# UCirKitBreadboardWithEverythingTop_2Laye.net
KiCad netlist of a schematic drawn in EAGLE
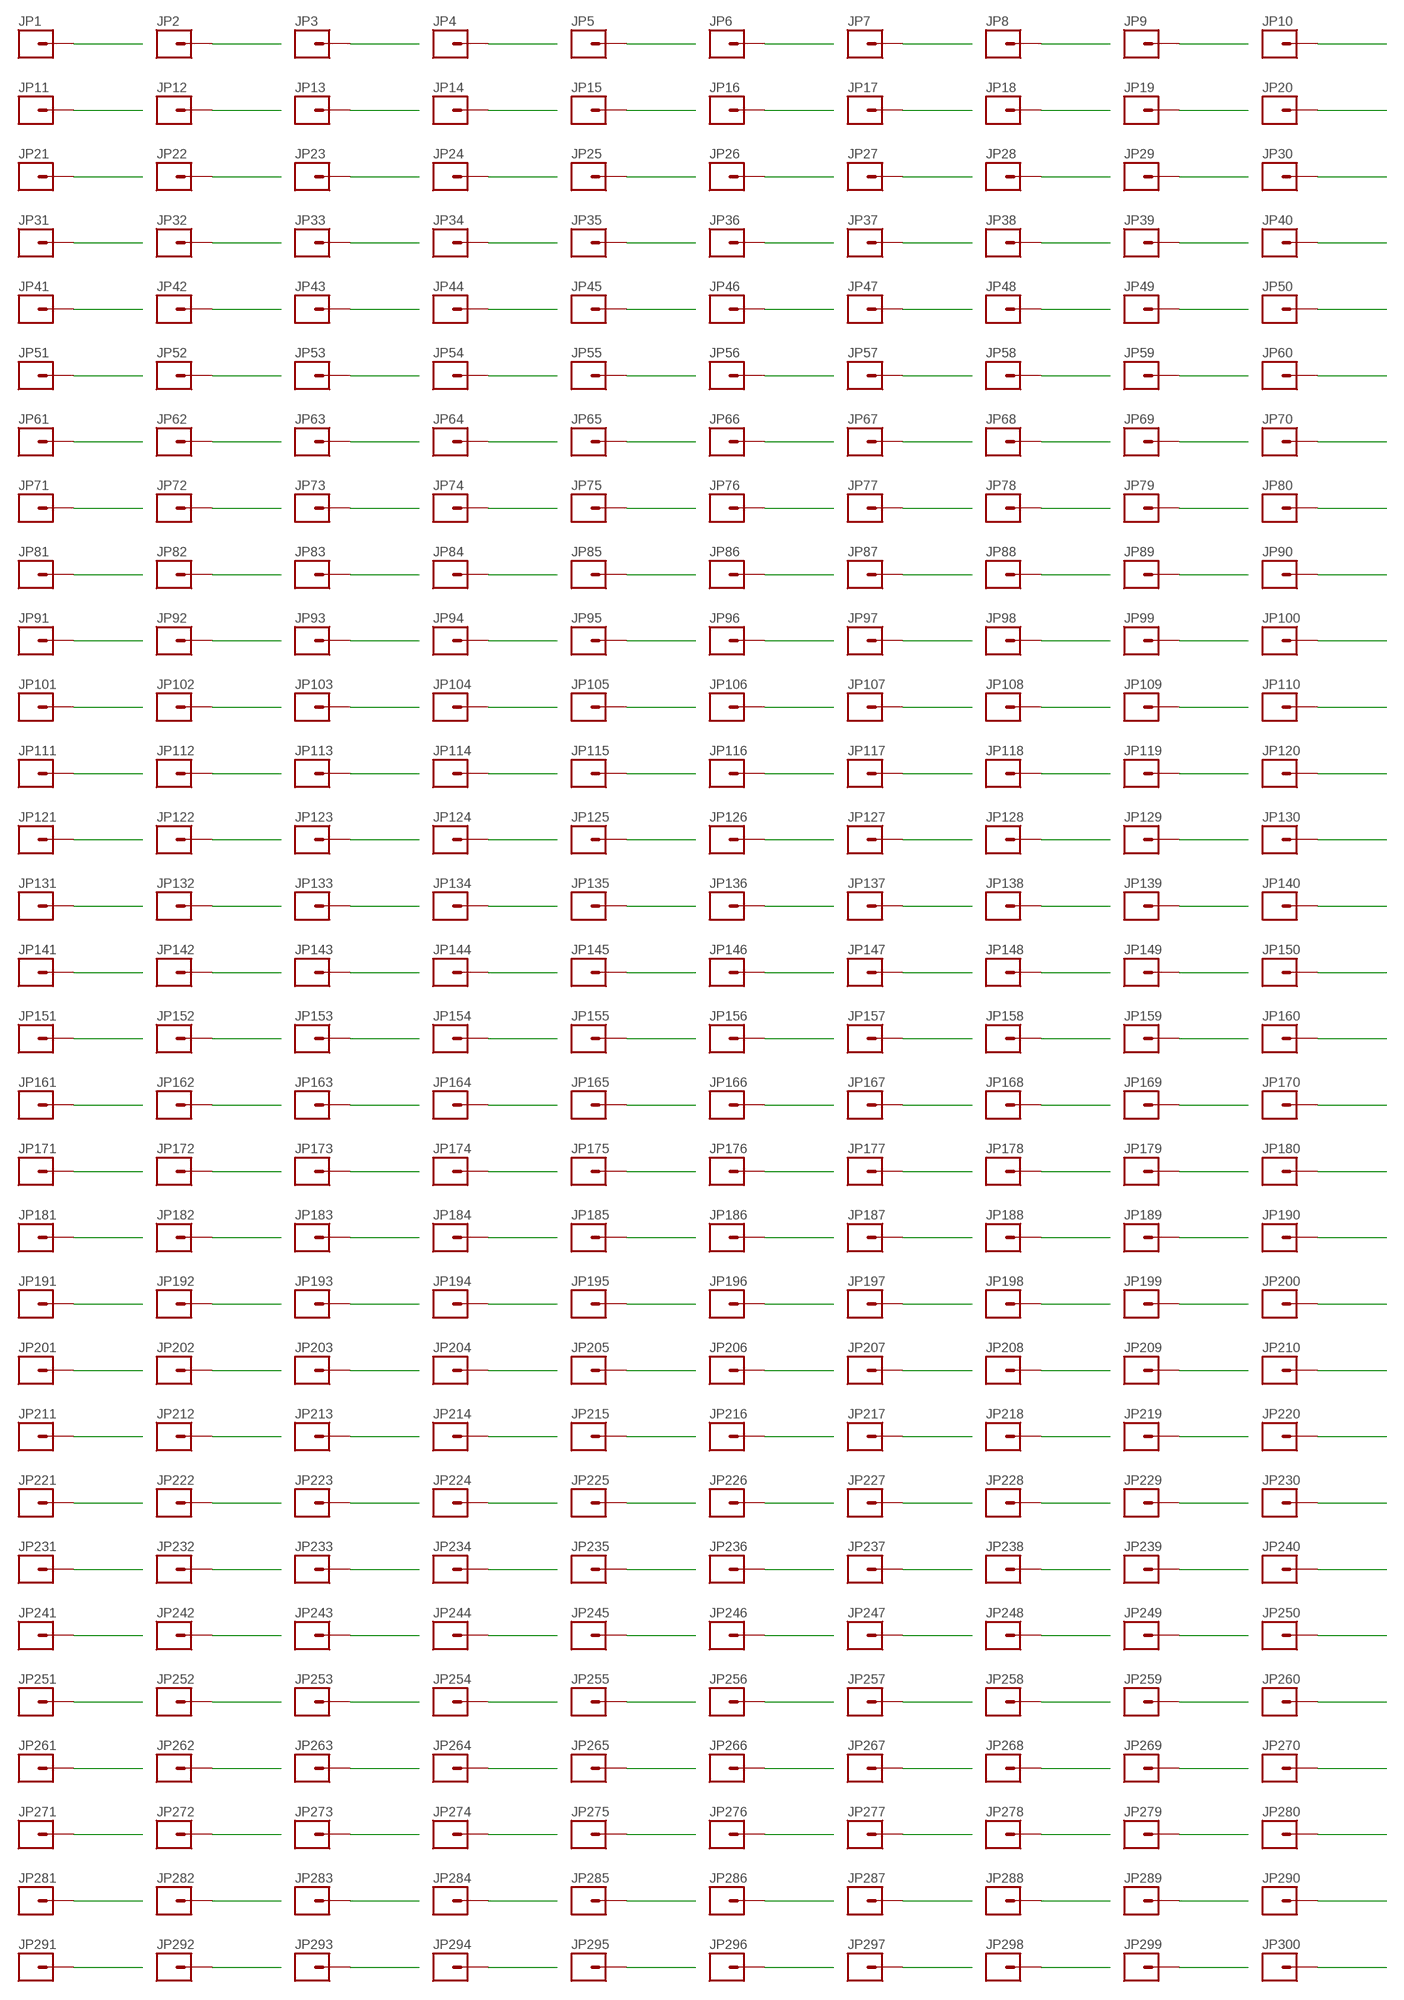
[diagram p0: schematic, sheet 1, part 1 of 2]
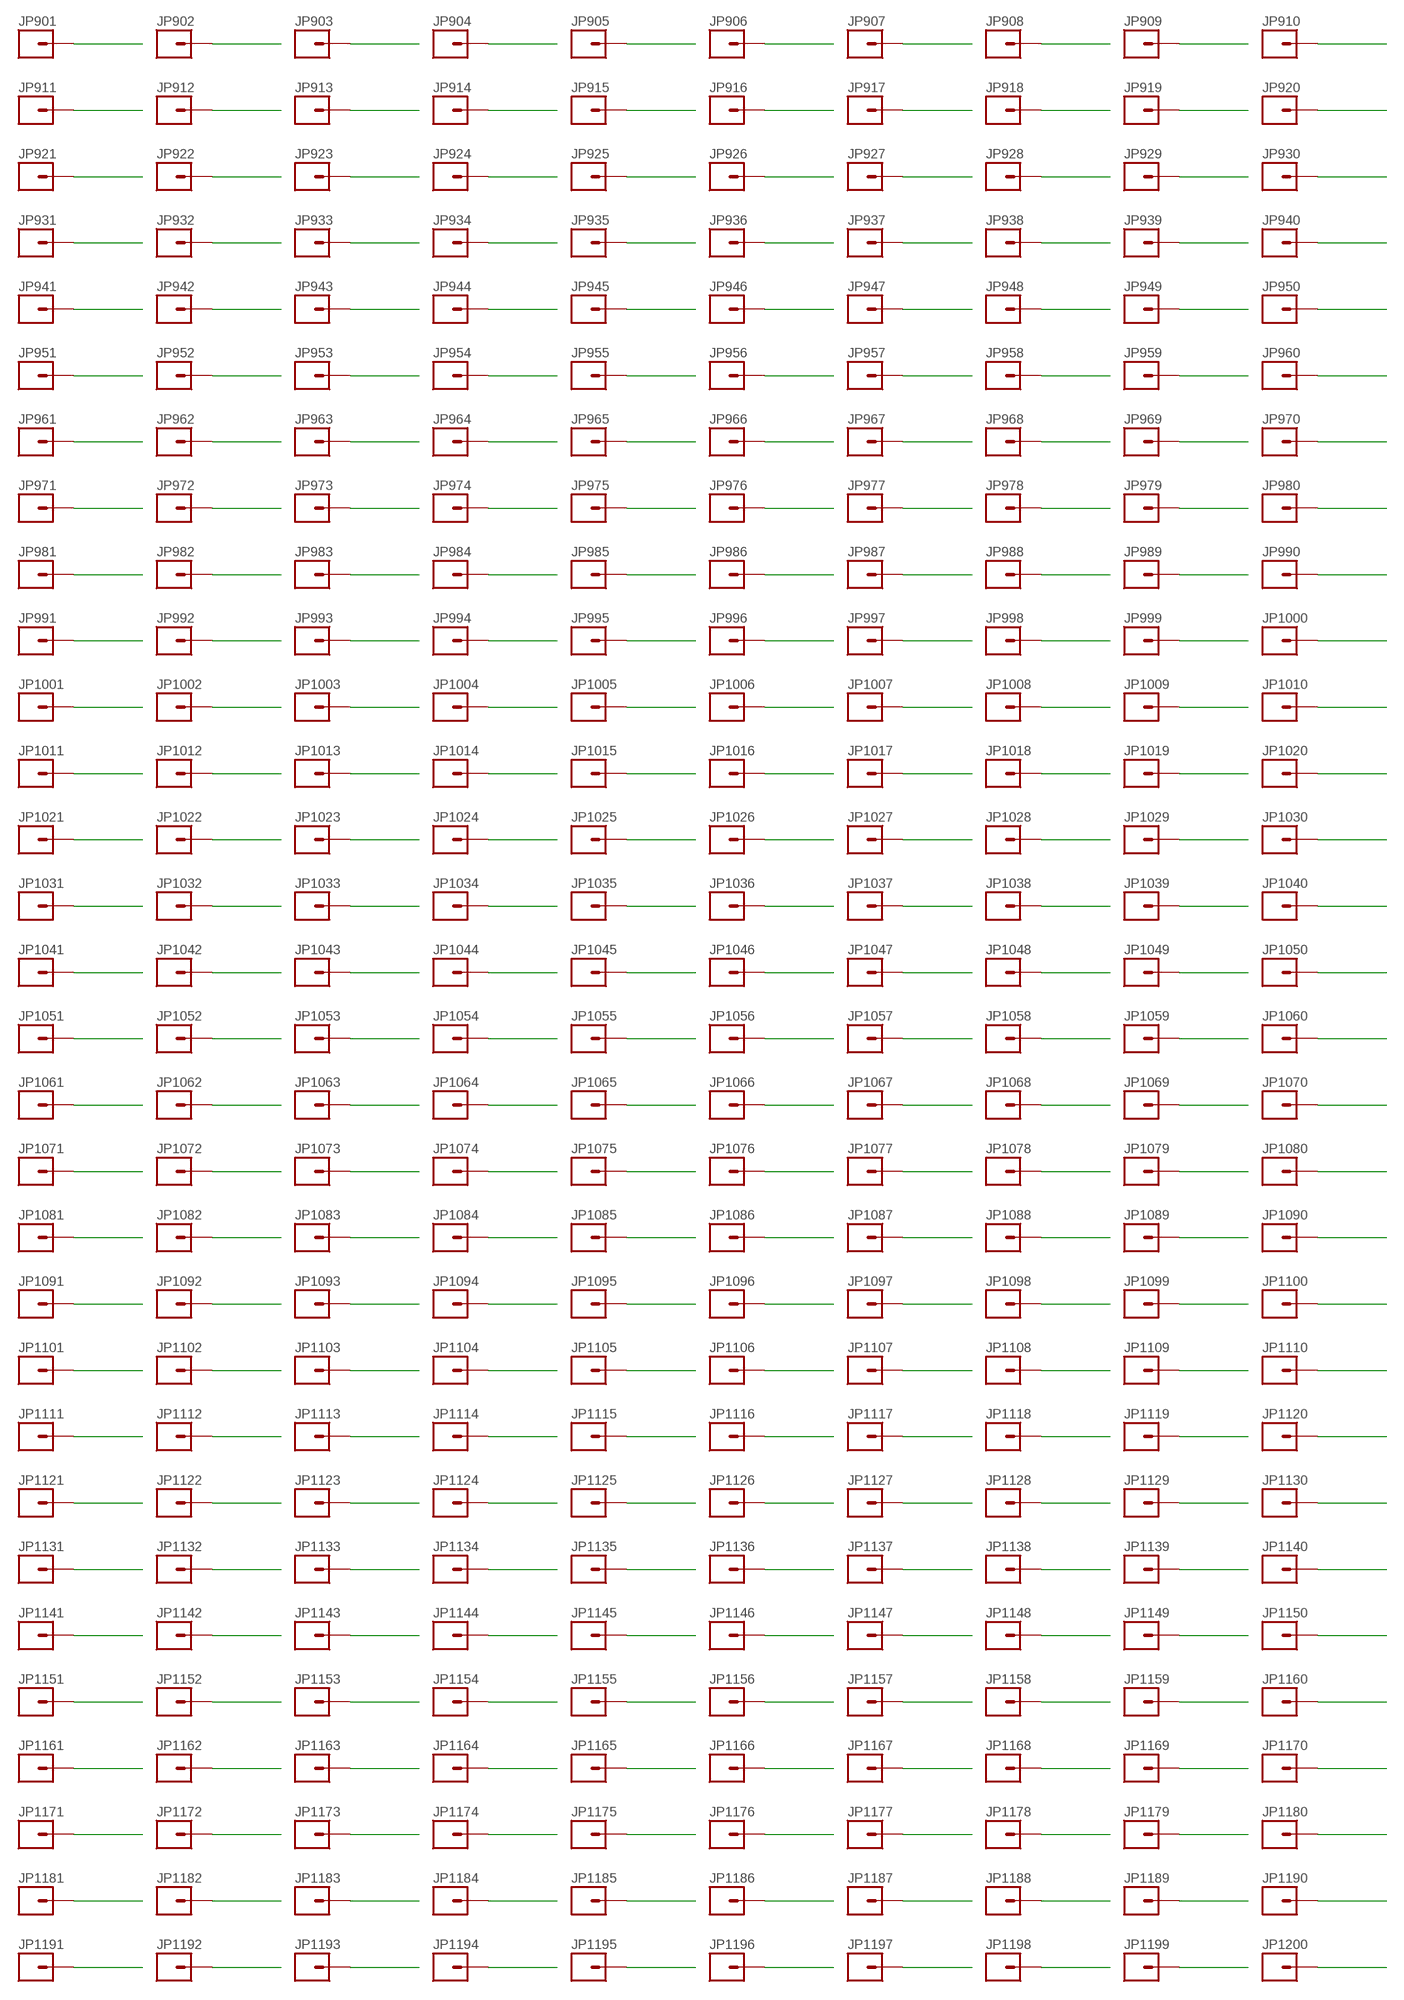
[diagram p1: schematic, sheet 1, part 2 of 2]

(export (version "E")
  (design (tool "Eeschema 10.0.6"))
  (components
    (comp (ref "JP1")
      (value "M01PTH_WITHOUT_TEXT")
      (footprint "eagle-import:1X01_WITHOUT_TEXT")
      (libsource (lib "eagle-import") (part "M01PTH_WITHOUT_TEXT"))
    )
    (comp (ref "JP2")
      (value "M01PTH_WITHOUT_TEXT")
      (footprint "eagle-import:1X01_WITHOUT_TEXT")
      (libsource (lib "eagle-import") (part "M01PTH_WITHOUT_TEXT"))
    )
    (comp (ref "JP3")
      (value "M01PTH_WITHOUT_TEXT")
      (footprint "eagle-import:1X01_WITHOUT_TEXT")
      (libsource (lib "eagle-import") (part "M01PTH_WITHOUT_TEXT"))
    )
    (comp (ref "JP4")
      (value "M01PTH_WITHOUT_TEXT")
      (footprint "eagle-import:1X01_WITHOUT_TEXT")
      (libsource (lib "eagle-import") (part "M01PTH_WITHOUT_TEXT"))
    )
    (comp (ref "JP5")
      (value "M01PTH_WITHOUT_TEXT")
      (footprint "eagle-import:1X01_WITHOUT_TEXT")
      (libsource (lib "eagle-import") (part "M01PTH_WITHOUT_TEXT"))
    )
    (comp (ref "JP6")
      (value "M01PTH_WITHOUT_TEXT")
      (footprint "eagle-import:1X01_WITHOUT_TEXT")
      (libsource (lib "eagle-import") (part "M01PTH_WITHOUT_TEXT"))
    )
    (comp (ref "JP7")
      (value "M01PTH_WITHOUT_TEXT")
      (footprint "eagle-import:1X01_WITHOUT_TEXT")
      (libsource (lib "eagle-import") (part "M01PTH_WITHOUT_TEXT"))
    )
    (comp (ref "JP8")
      (value "M01PTH_WITHOUT_TEXT")
      (footprint "eagle-import:1X01_WITHOUT_TEXT")
      (libsource (lib "eagle-import") (part "M01PTH_WITHOUT_TEXT"))
    )
    (comp (ref "JP9")
      (value "M01PTH_WITHOUT_TEXT")
      (footprint "eagle-import:1X01_WITHOUT_TEXT")
      (libsource (lib "eagle-import") (part "M01PTH_WITHOUT_TEXT"))
    )
    (comp (ref "JP10")
      (value "M01PTH_WITHOUT_TEXT")
      (footprint "eagle-import:1X01_WITHOUT_TEXT")
      (libsource (lib "eagle-import") (part "M01PTH_WITHOUT_TEXT"))
    )
    (comp (ref "JP11")
      (value "M01PTH_WITHOUT_TEXT")
      (footprint "eagle-import:1X01_WITHOUT_TEXT")
      (libsource (lib "eagle-import") (part "M01PTH_WITHOUT_TEXT"))
    )
    (comp (ref "JP12")
      (value "M01PTH_WITHOUT_TEXT")
      (footprint "eagle-import:1X01_WITHOUT_TEXT")
      (libsource (lib "eagle-import") (part "M01PTH_WITHOUT_TEXT"))
    )
    (comp (ref "JP13")
      (value "M01PTH_WITHOUT_TEXT")
      (footprint "eagle-import:1X01_WITHOUT_TEXT")
      (libsource (lib "eagle-import") (part "M01PTH_WITHOUT_TEXT"))
    )
    (comp (ref "JP14")
      (value "M01PTH_WITHOUT_TEXT")
      (footprint "eagle-import:1X01_WITHOUT_TEXT")
      (libsource (lib "eagle-import") (part "M01PTH_WITHOUT_TEXT"))
    )
    (comp (ref "JP15")
      (value "M01PTH_WITHOUT_TEXT")
      (footprint "eagle-import:1X01_WITHOUT_TEXT")
      (libsource (lib "eagle-import") (part "M01PTH_WITHOUT_TEXT"))
    )
    (comp (ref "JP16")
      (value "M01PTH_WITHOUT_TEXT")
      (footprint "eagle-import:1X01_WITHOUT_TEXT")
      (libsource (lib "eagle-import") (part "M01PTH_WITHOUT_TEXT"))
    )
    (comp (ref "JP17")
      (value "M01PTH_WITHOUT_TEXT")
      (footprint "eagle-import:1X01_WITHOUT_TEXT")
      (libsource (lib "eagle-import") (part "M01PTH_WITHOUT_TEXT"))
    )
    (comp (ref "JP18")
      (value "M01PTH_WITHOUT_TEXT")
      (footprint "eagle-import:1X01_WITHOUT_TEXT")
      (libsource (lib "eagle-import") (part "M01PTH_WITHOUT_TEXT"))
    )
    (comp (ref "JP19")
      (value "M01PTH_WITHOUT_TEXT")
      (footprint "eagle-import:1X01_WITHOUT_TEXT")
      (libsource (lib "eagle-import") (part "M01PTH_WITHOUT_TEXT"))
    )
    (comp (ref "JP20")
      (value "M01PTH_WITHOUT_TEXT")
      (footprint "eagle-import:1X01_WITHOUT_TEXT")
      (libsource (lib "eagle-import") (part "M01PTH_WITHOUT_TEXT"))
    )
    (comp (ref "JP21")
      (value "M01PTH_WITHOUT_TEXT")
      (footprint "eagle-import:1X01_WITHOUT_TEXT")
      (libsource (lib "eagle-import") (part "M01PTH_WITHOUT_TEXT"))
    )
    (comp (ref "JP22")
      (value "M01PTH_WITHOUT_TEXT")
      (footprint "eagle-import:1X01_WITHOUT_TEXT")
      (libsource (lib "eagle-import") (part "M01PTH_WITHOUT_TEXT"))
    )
    (comp (ref "JP23")
      (value "M01PTH_WITHOUT_TEXT")
      (footprint "eagle-import:1X01_WITHOUT_TEXT")
      (libsource (lib "eagle-import") (part "M01PTH_WITHOUT_TEXT"))
    )
    (comp (ref "JP24")
      (value "M01PTH_WITHOUT_TEXT")
      (footprint "eagle-import:1X01_WITHOUT_TEXT")
      (libsource (lib "eagle-import") (part "M01PTH_WITHOUT_TEXT"))
    )
    (comp (ref "JP25")
      (value "M01PTH_WITHOUT_TEXT")
      (footprint "eagle-import:1X01_WITHOUT_TEXT")
      (libsource (lib "eagle-import") (part "M01PTH_WITHOUT_TEXT"))
    )
    (comp (ref "JP26")
      (value "M01PTH_WITHOUT_TEXT")
      (footprint "eagle-import:1X01_WITHOUT_TEXT")
      (libsource (lib "eagle-import") (part "M01PTH_WITHOUT_TEXT"))
    )
    (comp (ref "JP27")
      (value "M01PTH_WITHOUT_TEXT")
      (footprint "eagle-import:1X01_WITHOUT_TEXT")
      (libsource (lib "eagle-import") (part "M01PTH_WITHOUT_TEXT"))
    )
    (comp (ref "JP28")
      (value "M01PTH_WITHOUT_TEXT")
      (footprint "eagle-import:1X01_WITHOUT_TEXT")
      (libsource (lib "eagle-import") (part "M01PTH_WITHOUT_TEXT"))
    )
    (comp (ref "JP29")
      (value "M01PTH_WITHOUT_TEXT")
      (footprint "eagle-import:1X01_WITHOUT_TEXT")
      (libsource (lib "eagle-import") (part "M01PTH_WITHOUT_TEXT"))
    )
    (comp (ref "JP30")
      (value "M01PTH_WITHOUT_TEXT")
      (footprint "eagle-import:1X01_WITHOUT_TEXT")
      (libsource (lib "eagle-import") (part "M01PTH_WITHOUT_TEXT"))
    )
    (comp (ref "JP31")
      (value "M01PTH_WITHOUT_TEXT")
      (footprint "eagle-import:1X01_WITHOUT_TEXT")
      (libsource (lib "eagle-import") (part "M01PTH_WITHOUT_TEXT"))
    )
    (comp (ref "JP32")
      (value "M01PTH_WITHOUT_TEXT")
      (footprint "eagle-import:1X01_WITHOUT_TEXT")
      (libsource (lib "eagle-import") (part "M01PTH_WITHOUT_TEXT"))
    )
    (comp (ref "JP33")
      (value "M01PTH_WITHOUT_TEXT")
      (footprint "eagle-import:1X01_WITHOUT_TEXT")
      (libsource (lib "eagle-import") (part "M01PTH_WITHOUT_TEXT"))
    )
    (comp (ref "JP34")
      (value "M01PTH_WITHOUT_TEXT")
      (footprint "eagle-import:1X01_WITHOUT_TEXT")
      (libsource (lib "eagle-import") (part "M01PTH_WITHOUT_TEXT"))
    )
    (comp (ref "JP35")
      (value "M01PTH_WITHOUT_TEXT")
      (footprint "eagle-import:1X01_WITHOUT_TEXT")
      (libsource (lib "eagle-import") (part "M01PTH_WITHOUT_TEXT"))
    )
    (comp (ref "JP36")
      (value "M01PTH_WITHOUT_TEXT")
      (footprint "eagle-import:1X01_WITHOUT_TEXT")
      (libsource (lib "eagle-import") (part "M01PTH_WITHOUT_TEXT"))
    )
    (comp (ref "JP37")
      (value "M01PTH_WITHOUT_TEXT")
      (footprint "eagle-import:1X01_WITHOUT_TEXT")
      (libsource (lib "eagle-import") (part "M01PTH_WITHOUT_TEXT"))
    )
    (comp (ref "JP38")
      (value "M01PTH_WITHOUT_TEXT")
      (footprint "eagle-import:1X01_WITHOUT_TEXT")
      (libsource (lib "eagle-import") (part "M01PTH_WITHOUT_TEXT"))
    )
    (comp (ref "JP39")
      (value "M01PTH_WITHOUT_TEXT")
      (footprint "eagle-import:1X01_WITHOUT_TEXT")
      (libsource (lib "eagle-import") (part "M01PTH_WITHOUT_TEXT"))
    )
    (comp (ref "JP40")
      (value "M01PTH_WITHOUT_TEXT")
      (footprint "eagle-import:1X01_WITHOUT_TEXT")
      (libsource (lib "eagle-import") (part "M01PTH_WITHOUT_TEXT"))
    )
    (comp (ref "JP41")
      (value "M01PTH_WITHOUT_TEXT")
      (footprint "eagle-import:1X01_WITHOUT_TEXT")
      (libsource (lib "eagle-import") (part "M01PTH_WITHOUT_TEXT"))
    )
    (comp (ref "JP42")
      (value "M01PTH_WITHOUT_TEXT")
      (footprint "eagle-import:1X01_WITHOUT_TEXT")
      (libsource (lib "eagle-import") (part "M01PTH_WITHOUT_TEXT"))
    )
    (comp (ref "JP43")
      (value "M01PTH_WITHOUT_TEXT")
      (footprint "eagle-import:1X01_WITHOUT_TEXT")
      (libsource (lib "eagle-import") (part "M01PTH_WITHOUT_TEXT"))
    )
    (comp (ref "JP44")
      (value "M01PTH_WITHOUT_TEXT")
      (footprint "eagle-import:1X01_WITHOUT_TEXT")
      (libsource (lib "eagle-import") (part "M01PTH_WITHOUT_TEXT"))
    )
    (comp (ref "JP45")
      (value "M01PTH_WITHOUT_TEXT")
      (footprint "eagle-import:1X01_WITHOUT_TEXT")
      (libsource (lib "eagle-import") (part "M01PTH_WITHOUT_TEXT"))
    )
    (comp (ref "JP46")
      (value "M01PTH_WITHOUT_TEXT")
      (footprint "eagle-import:1X01_WITHOUT_TEXT")
      (libsource (lib "eagle-import") (part "M01PTH_WITHOUT_TEXT"))
    )
    (comp (ref "JP47")
      (value "M01PTH_WITHOUT_TEXT")
      (footprint "eagle-import:1X01_WITHOUT_TEXT")
      (libsource (lib "eagle-import") (part "M01PTH_WITHOUT_TEXT"))
    )
    (comp (ref "JP48")
      (value "M01PTH_WITHOUT_TEXT")
      (footprint "eagle-import:1X01_WITHOUT_TEXT")
      (libsource (lib "eagle-import") (part "M01PTH_WITHOUT_TEXT"))
    )
    (comp (ref "JP49")
      (value "M01PTH_WITHOUT_TEXT")
      (footprint "eagle-import:1X01_WITHOUT_TEXT")
      (libsource (lib "eagle-import") (part "M01PTH_WITHOUT_TEXT"))
    )
    (comp (ref "JP50")
      (value "M01PTH_WITHOUT_TEXT")
      (footprint "eagle-import:1X01_WITHOUT_TEXT")
      (libsource (lib "eagle-import") (part "M01PTH_WITHOUT_TEXT"))
    )
    (comp (ref "JP51")
      (value "M01PTH_WITHOUT_TEXT")
      (footprint "eagle-import:1X01_WITHOUT_TEXT")
      (libsource (lib "eagle-import") (part "M01PTH_WITHOUT_TEXT"))
    )
    (comp (ref "JP52")
      (value "M01PTH_WITHOUT_TEXT")
      (footprint "eagle-import:1X01_WITHOUT_TEXT")
      (libsource (lib "eagle-import") (part "M01PTH_WITHOUT_TEXT"))
    )
    (comp (ref "JP53")
      (value "M01PTH_WITHOUT_TEXT")
      (footprint "eagle-import:1X01_WITHOUT_TEXT")
      (libsource (lib "eagle-import") (part "M01PTH_WITHOUT_TEXT"))
    )
    (comp (ref "JP54")
      (value "M01PTH_WITHOUT_TEXT")
      (footprint "eagle-import:1X01_WITHOUT_TEXT")
      (libsource (lib "eagle-import") (part "M01PTH_WITHOUT_TEXT"))
    )
    (comp (ref "JP55")
      (value "M01PTH_WITHOUT_TEXT")
      (footprint "eagle-import:1X01_WITHOUT_TEXT")
      (libsource (lib "eagle-import") (part "M01PTH_WITHOUT_TEXT"))
    )
    (comp (ref "JP56")
      (value "M01PTH_WITHOUT_TEXT")
      (footprint "eagle-import:1X01_WITHOUT_TEXT")
      (libsource (lib "eagle-import") (part "M01PTH_WITHOUT_TEXT"))
    )
    (comp (ref "JP57")
      (value "M01PTH_WITHOUT_TEXT")
      (footprint "eagle-import:1X01_WITHOUT_TEXT")
      (libsource (lib "eagle-import") (part "M01PTH_WITHOUT_TEXT"))
    )
    (comp (ref "JP58")
      (value "M01PTH_WITHOUT_TEXT")
      (footprint "eagle-import:1X01_WITHOUT_TEXT")
      (libsource (lib "eagle-import") (part "M01PTH_WITHOUT_TEXT"))
    )
    (comp (ref "JP59")
      (value "M01PTH_WITHOUT_TEXT")
      (footprint "eagle-import:1X01_WITHOUT_TEXT")
      (libsource (lib "eagle-import") (part "M01PTH_WITHOUT_TEXT"))
    )
    (comp (ref "JP60")
      (value "M01PTH_WITHOUT_TEXT")
      (footprint "eagle-import:1X01_WITHOUT_TEXT")
      (libsource (lib "eagle-import") (part "M01PTH_WITHOUT_TEXT"))
    )
    (comp (ref "JP61")
      (value "M01PTH_WITHOUT_TEXT")
      (footprint "eagle-import:1X01_WITHOUT_TEXT")
      (libsource (lib "eagle-import") (part "M01PTH_WITHOUT_TEXT"))
    )
    (comp (ref "JP62")
      (value "M01PTH_WITHOUT_TEXT")
      (footprint "eagle-import:1X01_WITHOUT_TEXT")
      (libsource (lib "eagle-import") (part "M01PTH_WITHOUT_TEXT"))
    )
    (comp (ref "JP63")
      (value "M01PTH_WITHOUT_TEXT")
      (footprint "eagle-import:1X01_WITHOUT_TEXT")
      (libsource (lib "eagle-import") (part "M01PTH_WITHOUT_TEXT"))
    )
    (comp (ref "JP64")
      (value "M01PTH_WITHOUT_TEXT")
      (footprint "eagle-import:1X01_WITHOUT_TEXT")
      (libsource (lib "eagle-import") (part "M01PTH_WITHOUT_TEXT"))
    )
    (comp (ref "JP65")
      (value "M01PTH_WITHOUT_TEXT")
      (footprint "eagle-import:1X01_WITHOUT_TEXT")
      (libsource (lib "eagle-import") (part "M01PTH_WITHOUT_TEXT"))
    )
    (comp (ref "JP66")
      (value "M01PTH_WITHOUT_TEXT")
      (footprint "eagle-import:1X01_WITHOUT_TEXT")
      (libsource (lib "eagle-import") (part "M01PTH_WITHOUT_TEXT"))
    )
    (comp (ref "JP67")
      (value "M01PTH_WITHOUT_TEXT")
      (footprint "eagle-import:1X01_WITHOUT_TEXT")
      (libsource (lib "eagle-import") (part "M01PTH_WITHOUT_TEXT"))
    )
    (comp (ref "JP68")
      (value "M01PTH_WITHOUT_TEXT")
      (footprint "eagle-import:1X01_WITHOUT_TEXT")
      (libsource (lib "eagle-import") (part "M01PTH_WITHOUT_TEXT"))
    )
    (comp (ref "JP69")
      (value "M01PTH_WITHOUT_TEXT")
      (footprint "eagle-import:1X01_WITHOUT_TEXT")
      (libsource (lib "eagle-import") (part "M01PTH_WITHOUT_TEXT"))
    )
    (comp (ref "JP70")
      (value "M01PTH_WITHOUT_TEXT")
      (footprint "eagle-import:1X01_WITHOUT_TEXT")
      (libsource (lib "eagle-import") (part "M01PTH_WITHOUT_TEXT"))
    )
    (comp (ref "JP71")
      (value "M01PTH_WITHOUT_TEXT")
      (footprint "eagle-import:1X01_WITHOUT_TEXT")
      (libsource (lib "eagle-import") (part "M01PTH_WITHOUT_TEXT"))
    )
    (comp (ref "JP72")
      (value "M01PTH_WITHOUT_TEXT")
      (footprint "eagle-import:1X01_WITHOUT_TEXT")
      (libsource (lib "eagle-import") (part "M01PTH_WITHOUT_TEXT"))
    )
    (comp (ref "JP73")
      (value "M01PTH_WITHOUT_TEXT")
      (footprint "eagle-import:1X01_WITHOUT_TEXT")
      (libsource (lib "eagle-import") (part "M01PTH_WITHOUT_TEXT"))
    )
    (comp (ref "JP74")
      (value "M01PTH_WITHOUT_TEXT")
      (footprint "eagle-import:1X01_WITHOUT_TEXT")
      (libsource (lib "eagle-import") (part "M01PTH_WITHOUT_TEXT"))
    )
    (comp (ref "JP75")
      (value "M01PTH_WITHOUT_TEXT")
      (footprint "eagle-import:1X01_WITHOUT_TEXT")
      (libsource (lib "eagle-import") (part "M01PTH_WITHOUT_TEXT"))
    )
    (comp (ref "JP76")
      (value "M01PTH_WITHOUT_TEXT")
      (footprint "eagle-import:1X01_WITHOUT_TEXT")
      (libsource (lib "eagle-import") (part "M01PTH_WITHOUT_TEXT"))
    )
    (comp (ref "JP77")
      (value "M01PTH_WITHOUT_TEXT")
      (footprint "eagle-import:1X01_WITHOUT_TEXT")
      (libsource (lib "eagle-import") (part "M01PTH_WITHOUT_TEXT"))
    )
    (comp (ref "JP78")
      (value "M01PTH_WITHOUT_TEXT")
      (footprint "eagle-import:1X01_WITHOUT_TEXT")
      (libsource (lib "eagle-import") (part "M01PTH_WITHOUT_TEXT"))
    )
    (comp (ref "JP79")
      (value "M01PTH_WITHOUT_TEXT")
      (footprint "eagle-import:1X01_WITHOUT_TEXT")
      (libsource (lib "eagle-import") (part "M01PTH_WITHOUT_TEXT"))
    )
    (comp (ref "JP80")
      (value "M01PTH_WITHOUT_TEXT")
      (footprint "eagle-import:1X01_WITHOUT_TEXT")
      (libsource (lib "eagle-import") (part "M01PTH_WITHOUT_TEXT"))
    )
    (comp (ref "JP81")
      (value "M01PTH_WITHOUT_TEXT")
      (footprint "eagle-import:1X01_WITHOUT_TEXT")
      (libsource (lib "eagle-import") (part "M01PTH_WITHOUT_TEXT"))
    )
    (comp (ref "JP82")
      (value "M01PTH_WITHOUT_TEXT")
      (footprint "eagle-import:1X01_WITHOUT_TEXT")
      (libsource (lib "eagle-import") (part "M01PTH_WITHOUT_TEXT"))
    )
    (comp (ref "JP83")
      (value "M01PTH_WITHOUT_TEXT")
      (footprint "eagle-import:1X01_WITHOUT_TEXT")
      (libsource (lib "eagle-import") (part "M01PTH_WITHOUT_TEXT"))
    )
    (comp (ref "JP84")
      (value "M01PTH_WITHOUT_TEXT")
      (footprint "eagle-import:1X01_WITHOUT_TEXT")
      (libsource (lib "eagle-import") (part "M01PTH_WITHOUT_TEXT"))
    )
    (comp (ref "JP85")
      (value "M01PTH_WITHOUT_TEXT")
      (footprint "eagle-import:1X01_WITHOUT_TEXT")
      (libsource (lib "eagle-import") (part "M01PTH_WITHOUT_TEXT"))
    )
    (comp (ref "JP86")
      (value "M01PTH_WITHOUT_TEXT")
      (footprint "eagle-import:1X01_WITHOUT_TEXT")
      (libsource (lib "eagle-import") (part "M01PTH_WITHOUT_TEXT"))
    )
    (comp (ref "JP87")
      (value "M01PTH_WITHOUT_TEXT")
      (footprint "eagle-import:1X01_WITHOUT_TEXT")
      (libsource (lib "eagle-import") (part "M01PTH_WITHOUT_TEXT"))
    )
    (comp (ref "JP88")
      (value "M01PTH_WITHOUT_TEXT")
      (footprint "eagle-import:1X01_WITHOUT_TEXT")
      (libsource (lib "eagle-import") (part "M01PTH_WITHOUT_TEXT"))
    )
    (comp (ref "JP89")
      (value "M01PTH_WITHOUT_TEXT")
      (footprint "eagle-import:1X01_WITHOUT_TEXT")
      (libsource (lib "eagle-import") (part "M01PTH_WITHOUT_TEXT"))
    )
    (comp (ref "JP90")
      (value "M01PTH_WITHOUT_TEXT")
      (footprint "eagle-import:1X01_WITHOUT_TEXT")
      (libsource (lib "eagle-import") (part "M01PTH_WITHOUT_TEXT"))
    )
    (comp (ref "JP91")
      (value "M01PTH_WITHOUT_TEXT")
      (footprint "eagle-import:1X01_WITHOUT_TEXT")
      (libsource (lib "eagle-import") (part "M01PTH_WITHOUT_TEXT"))
    )
    (comp (ref "JP92")
      (value "M01PTH_WITHOUT_TEXT")
      (footprint "eagle-import:1X01_WITHOUT_TEXT")
      (libsource (lib "eagle-import") (part "M01PTH_WITHOUT_TEXT"))
    )
    (comp (ref "JP93")
      (value "M01PTH_WITHOUT_TEXT")
      (footprint "eagle-import:1X01_WITHOUT_TEXT")
      (libsource (lib "eagle-import") (part "M01PTH_WITHOUT_TEXT"))
    )
    (comp (ref "JP94")
      (value "M01PTH_WITHOUT_TEXT")
      (footprint "eagle-import:1X01_WITHOUT_TEXT")
      (libsource (lib "eagle-import") (part "M01PTH_WITHOUT_TEXT"))
    )
    (comp (ref "JP95")
      (value "M01PTH_WITHOUT_TEXT")
      (footprint "eagle-import:1X01_WITHOUT_TEXT")
      (libsource (lib "eagle-import") (part "M01PTH_WITHOUT_TEXT"))
    )
    (comp (ref "JP96")
      (value "M01PTH_WITHOUT_TEXT")
      (footprint "eagle-import:1X01_WITHOUT_TEXT")
      (libsource (lib "eagle-import") (part "M01PTH_WITHOUT_TEXT"))
    )
    (comp (ref "JP97")
      (value "M01PTH_WITHOUT_TEXT")
      (footprint "eagle-import:1X01_WITHOUT_TEXT")
      (libsource (lib "eagle-import") (part "M01PTH_WITHOUT_TEXT"))
    )
    (comp (ref "JP98")
      (value "M01PTH_WITHOUT_TEXT")
      (footprint "eagle-import:1X01_WITHOUT_TEXT")
      (libsource (lib "eagle-import") (part "M01PTH_WITHOUT_TEXT"))
    )
    (comp (ref "JP99")
      (value "M01PTH_WITHOUT_TEXT")
      (footprint "eagle-import:1X01_WITHOUT_TEXT")
      (libsource (lib "eagle-import") (part "M01PTH_WITHOUT_TEXT"))
    )
    (comp (ref "JP100")
      (value "M01PTH_WITHOUT_TEXT")
      (footprint "eagle-import:1X01_WITHOUT_TEXT")
      (libsource (lib "eagle-import") (part "M01PTH_WITHOUT_TEXT"))
    )
    (comp (ref "JP101")
      (value "M01PTH_WITHOUT_TEXT")
      (footprint "eagle-import:1X01_WITHOUT_TEXT")
      (libsource (lib "eagle-import") (part "M01PTH_WITHOUT_TEXT"))
    )
    (comp (ref "JP102")
      (value "M01PTH_WITHOUT_TEXT")
      (footprint "eagle-import:1X01_WITHOUT_TEXT")
      (libsource (lib "eagle-import") (part "M01PTH_WITHOUT_TEXT"))
    )
    (comp (ref "JP103")
      (value "M01PTH_WITHOUT_TEXT")
      (footprint "eagle-import:1X01_WITHOUT_TEXT")
      (libsource (lib "eagle-import") (part "M01PTH_WITHOUT_TEXT"))
    )
    (comp (ref "JP104")
      (value "M01PTH_WITHOUT_TEXT")
      (footprint "eagle-import:1X01_WITHOUT_TEXT")
      (libsource (lib "eagle-import") (part "M01PTH_WITHOUT_TEXT"))
    )
    (comp (ref "JP105")
      (value "M01PTH_WITHOUT_TEXT")
      (footprint "eagle-import:1X01_WITHOUT_TEXT")
      (libsource (lib "eagle-import") (part "M01PTH_WITHOUT_TEXT"))
    )
    (comp (ref "JP106")
      (value "M01PTH_WITHOUT_TEXT")
      (footprint "eagle-import:1X01_WITHOUT_TEXT")
      (libsource (lib "eagle-import") (part "M01PTH_WITHOUT_TEXT"))
    )
    (comp (ref "JP107")
      (value "M01PTH_WITHOUT_TEXT")
      (footprint "eagle-import:1X01_WITHOUT_TEXT")
      (libsource (lib "eagle-import") (part "M01PTH_WITHOUT_TEXT"))
    )
    (comp (ref "JP108")
      (value "M01PTH_WITHOUT_TEXT")
      (footprint "eagle-import:1X01_WITHOUT_TEXT")
      (libsource (lib "eagle-import") (part "M01PTH_WITHOUT_TEXT"))
    )
    (comp (ref "JP109")
      (value "M01PTH_WITHOUT_TEXT")
      (footprint "eagle-import:1X01_WITHOUT_TEXT")
      (libsource (lib "eagle-import") (part "M01PTH_WITHOUT_TEXT"))
    )
    (comp (ref "JP110")
      (value "M01PTH_WITHOUT_TEXT")
      (footprint "eagle-import:1X01_WITHOUT_TEXT")
      (libsource (lib "eagle-import") (part "M01PTH_WITHOUT_TEXT"))
    )
    (comp (ref "JP111")
      (value "M01PTH_WITHOUT_TEXT")
      (footprint "eagle-import:1X01_WITHOUT_TEXT")
      (libsource (lib "eagle-import") (part "M01PTH_WITHOUT_TEXT"))
    )
    (comp (ref "JP112")
      (value "M01PTH_WITHOUT_TEXT")
      (footprint "eagle-import:1X01_WITHOUT_TEXT")
      (libsource (lib "eagle-import") (part "M01PTH_WITHOUT_TEXT"))
    )
    (comp (ref "JP113")
      (value "M01PTH_WITHOUT_TEXT")
      (footprint "eagle-import:1X01_WITHOUT_TEXT")
      (libsource (lib "eagle-import") (part "M01PTH_WITHOUT_TEXT"))
    )
    (comp (ref "JP114")
      (value "M01PTH_WITHOUT_TEXT")
      (footprint "eagle-import:1X01_WITHOUT_TEXT")
      (libsource (lib "eagle-import") (part "M01PTH_WITHOUT_TEXT"))
    )
    (comp (ref "JP115")
      (value "M01PTH_WITHOUT_TEXT")
      (footprint "eagle-import:1X01_WITHOUT_TEXT")
      (libsource (lib "eagle-import") (part "M01PTH_WITHOUT_TEXT"))
    )
    (comp (ref "JP116")
      (value "M01PTH_WITHOUT_TEXT")
      (footprint "eagle-import:1X01_WITHOUT_TEXT")
      (libsource (lib "eagle-import") (part "M01PTH_WITHOUT_TEXT"))
    )
    (comp (ref "JP117")
      (value "M01PTH_WITHOUT_TEXT")
      (footprint "eagle-import:1X01_WITHOUT_TEXT")
      (libsource (lib "eagle-import") (part "M01PTH_WITHOUT_TEXT"))
    )
    (comp (ref "JP118")
      (value "M01PTH_WITHOUT_TEXT")
      (footprint "eagle-import:1X01_WITHOUT_TEXT")
      (libsource (lib "eagle-import") (part "M01PTH_WITHOUT_TEXT"))
    )
    (comp (ref "JP119")
      (value "M01PTH_WITHOUT_TEXT")
      (footprint "eagle-import:1X01_WITHOUT_TEXT")
      (libsource (lib "eagle-import") (part "M01PTH_WITHOUT_TEXT"))
    )
    (comp (ref "JP120")
      (value "M01PTH_WITHOUT_TEXT")
      (footprint "eagle-import:1X01_WITHOUT_TEXT")
      (libsource (lib "eagle-import") (part "M01PTH_WITHOUT_TEXT"))
    )
    (comp (ref "JP121")
      (value "M01PTH_WITHOUT_TEXT")
      (footprint "eagle-import:1X01_WITHOUT_TEXT")
      (libsource (lib "eagle-import") (part "M01PTH_WITHOUT_TEXT"))
    )
    (comp (ref "JP122")
      (value "M01PTH_WITHOUT_TEXT")
      (footprint "eagle-import:1X01_WITHOUT_TEXT")
      (libsource (lib "eagle-import") (part "M01PTH_WITHOUT_TEXT"))
    )
    (comp (ref "JP123")
      (value "M01PTH_WITHOUT_TEXT")
      (footprint "eagle-import:1X01_WITHOUT_TEXT")
      (libsource (lib "eagle-import") (part "M01PTH_WITHOUT_TEXT"))
    )
    (comp (ref "JP124")
      (value "M01PTH_WITHOUT_TEXT")
      (footprint "eagle-import:1X01_WITHOUT_TEXT")
      (libsource (lib "eagle-import") (part "M01PTH_WITHOUT_TEXT"))
    )
    (comp (ref "JP125")
      (value "M01PTH_WITHOUT_TEXT")
      (footprint "eagle-import:1X01_WITHOUT_TEXT")
      (libsource (lib "eagle-import") (part "M01PTH_WITHOUT_TEXT"))
    )
    (comp (ref "JP126")
      (value "M01PTH_WITHOUT_TEXT")
      (footprint "eagle-import:1X01_WITHOUT_TEXT")
      (libsource (lib "eagle-import") (part "M01PTH_WITHOUT_TEXT"))
    )
    (comp (ref "JP127")
      (value "M01PTH_WITHOUT_TEXT")
      (footprint "eagle-import:1X01_WITHOUT_TEXT")
      (libsource (lib "eagle-import") (part "M01PTH_WITHOUT_TEXT"))
    )
    (comp (ref "JP128")
      (value "M01PTH_WITHOUT_TEXT")
      (footprint "eagle-import:1X01_WITHOUT_TEXT")
      (libsource (lib "eagle-import") (part "M01PTH_WITHOUT_TEXT"))
    )
    (comp (ref "JP129")
      (value "M01PTH_WITHOUT_TEXT")
      (footprint "eagle-import:1X01_WITHOUT_TEXT")
      (libsource (lib "eagle-import") (part "M01PTH_WITHOUT_TEXT"))
    )
    (comp (ref "JP130")
      (value "M01PTH_WITHOUT_TEXT")
      (footprint "eagle-import:1X01_WITHOUT_TEXT")
      (libsource (lib "eagle-import") (part "M01PTH_WITHOUT_TEXT"))
    )
    (comp (ref "JP131")
      (value "M01PTH_WITHOUT_TEXT")
      (footprint "eagle-import:1X01_WITHOUT_TEXT")
      (libsource (lib "eagle-import") (part "M01PTH_WITHOUT_TEXT"))
    )
    (comp (ref "JP132")
      (value "M01PTH_WITHOUT_TEXT")
      (footprint "eagle-import:1X01_WITHOUT_TEXT")
      (libsource (lib "eagle-import") (part "M01PTH_WITHOUT_TEXT"))
    )
    (comp (ref "JP133")
      (value "M01PTH_WITHOUT_TEXT")
      (footprint "eagle-import:1X01_WITHOUT_TEXT")
      (libsource (lib "eagle-import") (part "M01PTH_WITHOUT_TEXT"))
    )
    (comp (ref "JP134")
      (value "M01PTH_WITHOUT_TEXT")
      (footprint "eagle-import:1X01_WITHOUT_TEXT")
      (libsource (lib "eagle-import") (part "M01PTH_WITHOUT_TEXT"))
    )
    (comp (ref "JP135")
      (value "M01PTH_WITHOUT_TEXT")
      (footprint "eagle-import:1X01_WITHOUT_TEXT")
      (libsource (lib "eagle-import") (part "M01PTH_WITHOUT_TEXT"))
    )
    (comp (ref "JP136")
      (value "M01PTH_WITHOUT_TEXT")
      (footprint "eagle-import:1X01_WITHOUT_TEXT")
      (libsource (lib "eagle-import") (part "M01PTH_WITHOUT_TEXT"))
    )
    (comp (ref "JP137")
      (value "M01PTH_WITHOUT_TEXT")
      (footprint "eagle-import:1X01_WITHOUT_TEXT")
      (libsource (lib "eagle-import") (part "M01PTH_WITHOUT_TEXT"))
    )
    (comp (ref "JP138")
      (value "M01PTH_WITHOUT_TEXT")
      (footprint "eagle-import:1X01_WITHOUT_TEXT")
      (libsource (lib "eagle-import") (part "M01PTH_WITHOUT_TEXT"))
    )
    (comp (ref "JP139")
      (value "M01PTH_WITHOUT_TEXT")
      (footprint "eagle-import:1X01_WITHOUT_TEXT")
      (libsource (lib "eagle-import") (part "M01PTH_WITHOUT_TEXT"))
    )
    (comp (ref "JP140")
      (value "M01PTH_WITHOUT_TEXT")
      (footprint "eagle-import:1X01_WITHOUT_TEXT")
      (libsource (lib "eagle-import") (part "M01PTH_WITHOUT_TEXT"))
    )
    (comp (ref "JP141")
      (value "M01PTH_WITHOUT_TEXT")
      (footprint "eagle-import:1X01_WITHOUT_TEXT")
      (libsource (lib "eagle-import") (part "M01PTH_WITHOUT_TEXT"))
    )
    (comp (ref "JP142")
      (value "M01PTH_WITHOUT_TEXT")
      (footprint "eagle-import:1X01_WITHOUT_TEXT")
      (libsource (lib "eagle-import") (part "M01PTH_WITHOUT_TEXT"))
    )
    (comp (ref "JP143")
      (value "M01PTH_WITHOUT_TEXT")
      (footprint "eagle-import:1X01_WITHOUT_TEXT")
      (libsource (lib "eagle-import") (part "M01PTH_WITHOUT_TEXT"))
    )
    (comp (ref "JP144")
      (value "M01PTH_WITHOUT_TEXT")
      (footprint "eagle-import:1X01_WITHOUT_TEXT")
      (libsource (lib "eagle-import") (part "M01PTH_WITHOUT_TEXT"))
    )
    (comp (ref "JP145")
      (value "M01PTH_WITHOUT_TEXT")
      (footprint "eagle-import:1X01_WITHOUT_TEXT")
      (libsource (lib "eagle-import") (part "M01PTH_WITHOUT_TEXT"))
    )
    (comp (ref "JP146")
      (value "M01PTH_WITHOUT_TEXT")
      (footprint "eagle-import:1X01_WITHOUT_TEXT")
      (libsource (lib "eagle-import") (part "M01PTH_WITHOUT_TEXT"))
    )
    (comp (ref "JP147")
      (value "M01PTH_WITHOUT_TEXT")
      (footprint "eagle-import:1X01_WITHOUT_TEXT")
      (libsource (lib "eagle-import") (part "M01PTH_WITHOUT_TEXT"))
    )
    (comp (ref "JP148")
      (value "M01PTH_WITHOUT_TEXT")
      (footprint "eagle-import:1X01_WITHOUT_TEXT")
      (libsource (lib "eagle-import") (part "M01PTH_WITHOUT_TEXT"))
    )
    (comp (ref "JP149")
      (value "M01PTH_WITHOUT_TEXT")
      (footprint "eagle-import:1X01_WITHOUT_TEXT")
      (libsource (lib "eagle-import") (part "M01PTH_WITHOUT_TEXT"))
    )
    (comp (ref "JP150")
      (value "M01PTH_WITHOUT_TEXT")
      (footprint "eagle-import:1X01_WITHOUT_TEXT")
      (libsource (lib "eagle-import") (part "M01PTH_WITHOUT_TEXT"))
    )
    (comp (ref "JP151")
      (value "M01PTH_WITHOUT_TEXT")
      (footprint "eagle-import:1X01_WITHOUT_TEXT")
      (libsource (lib "eagle-import") (part "M01PTH_WITHOUT_TEXT"))
    )
    (comp (ref "JP152")
      (value "M01PTH_WITHOUT_TEXT")
      (footprint "eagle-import:1X01_WITHOUT_TEXT")
      (libsource (lib "eagle-import") (part "M01PTH_WITHOUT_TEXT"))
    )
    (comp (ref "JP153")
      (value "M01PTH_WITHOUT_TEXT")
      (footprint "eagle-import:1X01_WITHOUT_TEXT")
      (libsource (lib "eagle-import") (part "M01PTH_WITHOUT_TEXT"))
    )
    (comp (ref "JP154")
      (value "M01PTH_WITHOUT_TEXT")
      (footprint "eagle-import:1X01_WITHOUT_TEXT")
      (libsource (lib "eagle-import") (part "M01PTH_WITHOUT_TEXT"))
    )
    (comp (ref "JP155")
      (value "M01PTH_WITHOUT_TEXT")
      (footprint "eagle-import:1X01_WITHOUT_TEXT")
      (libsource (lib "eagle-import") (part "M01PTH_WITHOUT_TEXT"))
    )
    (comp (ref "JP156")
      (value "M01PTH_WITHOUT_TEXT")
      (footprint "eagle-import:1X01_WITHOUT_TEXT")
      (libsource (lib "eagle-import") (part "M01PTH_WITHOUT_TEXT"))
    )
    (comp (ref "JP157")
      (value "M01PTH_WITHOUT_TEXT")
      (footprint "eagle-import:1X01_WITHOUT_TEXT")
      (libsource (lib "eagle-import") (part "M01PTH_WITHOUT_TEXT"))
    )
    (comp (ref "JP158")
      (value "M01PTH_WITHOUT_TEXT")
      (footprint "eagle-import:1X01_WITHOUT_TEXT")
      (libsource (lib "eagle-import") (part "M01PTH_WITHOUT_TEXT"))
    )
    (comp (ref "JP159")
      (value "M01PTH_WITHOUT_TEXT")
      (footprint "eagle-import:1X01_WITHOUT_TEXT")
      (libsource (lib "eagle-import") (part "M01PTH_WITHOUT_TEXT"))
    )
    (comp (ref "JP160")
      (value "M01PTH_WITHOUT_TEXT")
      (footprint "eagle-import:1X01_WITHOUT_TEXT")
      (libsource (lib "eagle-import") (part "M01PTH_WITHOUT_TEXT"))
    )
    (comp (ref "JP161")
      (value "M01PTH_WITHOUT_TEXT")
      (footprint "eagle-import:1X01_WITHOUT_TEXT")
      (libsource (lib "eagle-import") (part "M01PTH_WITHOUT_TEXT"))
    )
    (comp (ref "JP162")
      (value "M01PTH_WITHOUT_TEXT")
      (footprint "eagle-import:1X01_WITHOUT_TEXT")
      (libsource (lib "eagle-import") (part "M01PTH_WITHOUT_TEXT"))
    )
    (comp (ref "JP163")
      (value "M01PTH_WITHOUT_TEXT")
      (footprint "eagle-import:1X01_WITHOUT_TEXT")
      (libsource (lib "eagle-import") (part "M01PTH_WITHOUT_TEXT"))
    )
    (comp (ref "JP164")
      (value "M01PTH_WITHOUT_TEXT")
      (footprint "eagle-import:1X01_WITHOUT_TEXT")
      (libsource (lib "eagle-import") (part "M01PTH_WITHOUT_TEXT"))
    )
    (comp (ref "JP165")
      (value "M01PTH_WITHOUT_TEXT")
      (footprint "eagle-import:1X01_WITHOUT_TEXT")
      (libsource (lib "eagle-import") (part "M01PTH_WITHOUT_TEXT"))
    )
    (comp (ref "JP166")
      (value "M01PTH_WITHOUT_TEXT")
      (footprint "eagle-import:1X01_WITHOUT_TEXT")
      (libsource (lib "eagle-import") (part "M01PTH_WITHOUT_TEXT"))
    )
    (comp (ref "JP167")
      (value "M01PTH_WITHOUT_TEXT")
      (footprint "eagle-import:1X01_WITHOUT_TEXT")
      (libsource (lib "eagle-import") (part "M01PTH_WITHOUT_TEXT"))
    )
    (comp (ref "JP168")
      (value "M01PTH_WITHOUT_TEXT")
      (footprint "eagle-import:1X01_WITHOUT_TEXT")
      (libsource (lib "eagle-import") (part "M01PTH_WITHOUT_TEXT"))
    )
    (comp (ref "JP169")
      (value "M01PTH_WITHOUT_TEXT")
      (footprint "eagle-import:1X01_WITHOUT_TEXT")
      (libsource (lib "eagle-import") (part "M01PTH_WITHOUT_TEXT"))
    )
    (comp (ref "JP170")
      (value "M01PTH_WITHOUT_TEXT")
      (footprint "eagle-import:1X01_WITHOUT_TEXT")
      (libsource (lib "eagle-import") (part "M01PTH_WITHOUT_TEXT"))
    )
    (comp (ref "JP171")
      (value "M01PTH_WITHOUT_TEXT")
      (footprint "eagle-import:1X01_WITHOUT_TEXT")
      (libsource (lib "eagle-import") (part "M01PTH_WITHOUT_TEXT"))
    )
    (comp (ref "JP172")
      (value "M01PTH_WITHOUT_TEXT")
      (footprint "eagle-import:1X01_WITHOUT_TEXT")
      (libsource (lib "eagle-import") (part "M01PTH_WITHOUT_TEXT"))
    )
    (comp (ref "JP173")
      (value "M01PTH_WITHOUT_TEXT")
      (footprint "eagle-import:1X01_WITHOUT_TEXT")
      (libsource (lib "eagle-import") (part "M01PTH_WITHOUT_TEXT"))
    )
    (comp (ref "JP174")
      (value "M01PTH_WITHOUT_TEXT")
      (footprint "eagle-import:1X01_WITHOUT_TEXT")
      (libsource (lib "eagle-import") (part "M01PTH_WITHOUT_TEXT"))
    )
    (comp (ref "JP175")
      (value "M01PTH_WITHOUT_TEXT")
      (footprint "eagle-import:1X01_WITHOUT_TEXT")
      (libsource (lib "eagle-import") (part "M01PTH_WITHOUT_TEXT"))
    )
    (comp (ref "JP176")
      (value "M01PTH_WITHOUT_TEXT")
      (footprint "eagle-import:1X01_WITHOUT_TEXT")
      (libsource (lib "eagle-import") (part "M01PTH_WITHOUT_TEXT"))
    )
    (comp (ref "JP177")
      (value "M01PTH_WITHOUT_TEXT")
      (footprint "eagle-import:1X01_WITHOUT_TEXT")
      (libsource (lib "eagle-import") (part "M01PTH_WITHOUT_TEXT"))
    )
    (comp (ref "JP178")
      (value "M01PTH_WITHOUT_TEXT")
      (footprint "eagle-import:1X01_WITHOUT_TEXT")
      (libsource (lib "eagle-import") (part "M01PTH_WITHOUT_TEXT"))
    )
    (comp (ref "JP179")
      (value "M01PTH_WITHOUT_TEXT")
      (footprint "eagle-import:1X01_WITHOUT_TEXT")
      (libsource (lib "eagle-import") (part "M01PTH_WITHOUT_TEXT"))
    )
    (comp (ref "JP180")
      (value "M01PTH_WITHOUT_TEXT")
      (footprint "eagle-import:1X01_WITHOUT_TEXT")
      (libsource (lib "eagle-import") (part "M01PTH_WITHOUT_TEXT"))
    )
    (comp (ref "JP181")
      (value "M01PTH_WITHOUT_TEXT")
      (footprint "eagle-import:1X01_WITHOUT_TEXT")
      (libsource (lib "eagle-import") (part "M01PTH_WITHOUT_TEXT"))
    )
    (comp (ref "JP182")
      (value "M01PTH_WITHOUT_TEXT")
      (footprint "eagle-import:1X01_WITHOUT_TEXT")
      (libsource (lib "eagle-import") (part "M01PTH_WITHOUT_TEXT"))
    )
    (comp (ref "JP183")
      (value "M01PTH_WITHOUT_TEXT")
      (footprint "eagle-import:1X01_WITHOUT_TEXT")
      (libsource (lib "eagle-import") (part "M01PTH_WITHOUT_TEXT"))
    )
    (comp (ref "JP184")
      (value "M01PTH_WITHOUT_TEXT")
      (footprint "eagle-import:1X01_WITHOUT_TEXT")
      (libsource (lib "eagle-import") (part "M01PTH_WITHOUT_TEXT"))
    )
    (comp (ref "JP185")
      (value "M01PTH_WITHOUT_TEXT")
      (footprint "eagle-import:1X01_WITHOUT_TEXT")
      (libsource (lib "eagle-import") (part "M01PTH_WITHOUT_TEXT"))
    )
    (comp (ref "JP186")
      (value "M01PTH_WITHOUT_TEXT")
      (footprint "eagle-import:1X01_WITHOUT_TEXT")
      (libsource (lib "eagle-import") (part "M01PTH_WITHOUT_TEXT"))
    )
    (comp (ref "JP187")
      (value "M01PTH_WITHOUT_TEXT")
      (footprint "eagle-import:1X01_WITHOUT_TEXT")
      (libsource (lib "eagle-import") (part "M01PTH_WITHOUT_TEXT"))
    )
    (comp (ref "JP188")
      (value "M01PTH_WITHOUT_TEXT")
      (footprint "eagle-import:1X01_WITHOUT_TEXT")
      (libsource (lib "eagle-import") (part "M01PTH_WITHOUT_TEXT"))
    )
    (comp (ref "JP189")
      (value "M01PTH_WITHOUT_TEXT")
      (footprint "eagle-import:1X01_WITHOUT_TEXT")
      (libsource (lib "eagle-import") (part "M01PTH_WITHOUT_TEXT"))
    )
    (comp (ref "JP190")
      (value "M01PTH_WITHOUT_TEXT")
      (footprint "eagle-import:1X01_WITHOUT_TEXT")
      (libsource (lib "eagle-import") (part "M01PTH_WITHOUT_TEXT"))
    )
    (comp (ref "JP191")
      (value "M01PTH_WITHOUT_TEXT")
      (footprint "eagle-import:1X01_WITHOUT_TEXT")
      (libsource (lib "eagle-import") (part "M01PTH_WITHOUT_TEXT"))
    )
    (comp (ref "JP192")
      (value "M01PTH_WITHOUT_TEXT")
      (footprint "eagle-import:1X01_WITHOUT_TEXT")
      (libsource (lib "eagle-import") (part "M01PTH_WITHOUT_TEXT"))
    )
    (comp (ref "JP193")
      (value "M01PTH_WITHOUT_TEXT")
      (footprint "eagle-import:1X01_WITHOUT_TEXT")
      (libsource (lib "eagle-import") (part "M01PTH_WITHOUT_TEXT"))
    )
    (comp (ref "JP194")
      (value "M01PTH_WITHOUT_TEXT")
      (footprint "eagle-import:1X01_WITHOUT_TEXT")
      (libsource (lib "eagle-import") (part "M01PTH_WITHOUT_TEXT"))
    )
    (comp (ref "JP195")
      (value "M01PTH_WITHOUT_TEXT")
      (footprint "eagle-import:1X01_WITHOUT_TEXT")
      (libsource (lib "eagle-import") (part "M01PTH_WITHOUT_TEXT"))
    )
    (comp (ref "JP196")
      (value "M01PTH_WITHOUT_TEXT")
      (footprint "eagle-import:1X01_WITHOUT_TEXT")
      (libsource (lib "eagle-import") (part "M01PTH_WITHOUT_TEXT"))
    )
    (comp (ref "JP197")
      (value "M01PTH_WITHOUT_TEXT")
      (footprint "eagle-import:1X01_WITHOUT_TEXT")
      (libsource (lib "eagle-import") (part "M01PTH_WITHOUT_TEXT"))
    )
    (comp (ref "JP198")
      (value "M01PTH_WITHOUT_TEXT")
      (footprint "eagle-import:1X01_WITHOUT_TEXT")
      (libsource (lib "eagle-import") (part "M01PTH_WITHOUT_TEXT"))
    )
    (comp (ref "JP199")
      (value "M01PTH_WITHOUT_TEXT")
      (footprint "eagle-import:1X01_WITHOUT_TEXT")
      (libsource (lib "eagle-import") (part "M01PTH_WITHOUT_TEXT"))
    )
    (comp (ref "JP200")
      (value "M01PTH_WITHOUT_TEXT")
      (footprint "eagle-import:1X01_WITHOUT_TEXT")
      (libsource (lib "eagle-import") (part "M01PTH_WITHOUT_TEXT"))
    )
    (comp (ref "JP201")
      (value "M01PTH_WITHOUT_TEXT")
      (footprint "eagle-import:1X01_WITHOUT_TEXT")
      (libsource (lib "eagle-import") (part "M01PTH_WITHOUT_TEXT"))
    )
    (comp (ref "JP202")
      (value "M01PTH_WITHOUT_TEXT")
      (footprint "eagle-import:1X01_WITHOUT_TEXT")
      (libsource (lib "eagle-import") (part "M01PTH_WITHOUT_TEXT"))
    )
    (comp (ref "JP203")
      (value "M01PTH_WITHOUT_TEXT")
      (footprint "eagle-import:1X01_WITHOUT_TEXT")
      (libsource (lib "eagle-import") (part "M01PTH_WITHOUT_TEXT"))
    )
    (comp (ref "JP204")
      (value "M01PTH_WITHOUT_TEXT")
      (footprint "eagle-import:1X01_WITHOUT_TEXT")
      (libsource (lib "eagle-import") (part "M01PTH_WITHOUT_TEXT"))
    )
    (comp (ref "JP205")
      (value "M01PTH_WITHOUT_TEXT")
      (footprint "eagle-import:1X01_WITHOUT_TEXT")
      (libsource (lib "eagle-import") (part "M01PTH_WITHOUT_TEXT"))
    )
    (comp (ref "JP206")
      (value "M01PTH_WITHOUT_TEXT")
      (footprint "eagle-import:1X01_WITHOUT_TEXT")
      (libsource (lib "eagle-import") (part "M01PTH_WITHOUT_TEXT"))
    )
    (comp (ref "JP207")
      (value "M01PTH_WITHOUT_TEXT")
      (footprint "eagle-import:1X01_WITHOUT_TEXT")
      (libsource (lib "eagle-import") (part "M01PTH_WITHOUT_TEXT"))
    )
    (comp (ref "JP208")
      (value "M01PTH_WITHOUT_TEXT")
      (footprint "eagle-import:1X01_WITHOUT_TEXT")
      (libsource (lib "eagle-import") (part "M01PTH_WITHOUT_TEXT"))
    )
    (comp (ref "JP209")
      (value "M01PTH_WITHOUT_TEXT")
      (footprint "eagle-import:1X01_WITHOUT_TEXT")
      (libsource (lib "eagle-import") (part "M01PTH_WITHOUT_TEXT"))
    )
    (comp (ref "JP210")
      (value "M01PTH_WITHOUT_TEXT")
      (footprint "eagle-import:1X01_WITHOUT_TEXT")
      (libsource (lib "eagle-import") (part "M01PTH_WITHOUT_TEXT"))
    )
    (comp (ref "JP211")
      (value "M01PTH_WITHOUT_TEXT")
      (footprint "eagle-import:1X01_WITHOUT_TEXT")
      (libsource (lib "eagle-import") (part "M01PTH_WITHOUT_TEXT"))
    )
    (comp (ref "JP212")
      (value "M01PTH_WITHOUT_TEXT")
      (footprint "eagle-import:1X01_WITHOUT_TEXT")
      (libsource (lib "eagle-import") (part "M01PTH_WITHOUT_TEXT"))
    )
    (comp (ref "JP213")
      (value "M01PTH_WITHOUT_TEXT")
      (footprint "eagle-import:1X01_WITHOUT_TEXT")
      (libsource (lib "eagle-import") (part "M01PTH_WITHOUT_TEXT"))
    )
    (comp (ref "JP214")
      (value "M01PTH_WITHOUT_TEXT")
      (footprint "eagle-import:1X01_WITHOUT_TEXT")
      (libsource (lib "eagle-import") (part "M01PTH_WITHOUT_TEXT"))
    )
    (comp (ref "JP215")
      (value "M01PTH_WITHOUT_TEXT")
      (footprint "eagle-import:1X01_WITHOUT_TEXT")
      (libsource (lib "eagle-import") (part "M01PTH_WITHOUT_TEXT"))
    )
    (comp (ref "JP216")
      (value "M01PTH_WITHOUT_TEXT")
      (footprint "eagle-import:1X01_WITHOUT_TEXT")
      (libsource (lib "eagle-import") (part "M01PTH_WITHOUT_TEXT"))
    )
    (comp (ref "JP217")
      (value "M01PTH_WITHOUT_TEXT")
      (footprint "eagle-import:1X01_WITHOUT_TEXT")
      (libsource (lib "eagle-import") (part "M01PTH_WITHOUT_TEXT"))
    )
    (comp (ref "JP218")
      (value "M01PTH_WITHOUT_TEXT")
      (footprint "eagle-import:1X01_WITHOUT_TEXT")
      (libsource (lib "eagle-import") (part "M01PTH_WITHOUT_TEXT"))
    )
    (comp (ref "JP219")
      (value "M01PTH_WITHOUT_TEXT")
      (footprint "eagle-import:1X01_WITHOUT_TEXT")
      (libsource (lib "eagle-import") (part "M01PTH_WITHOUT_TEXT"))
    )
    (comp (ref "JP220")
      (value "M01PTH_WITHOUT_TEXT")
      (footprint "eagle-import:1X01_WITHOUT_TEXT")
      (libsource (lib "eagle-import") (part "M01PTH_WITHOUT_TEXT"))
    )
    (comp (ref "JP221")
      (value "M01PTH_WITHOUT_TEXT")
      (footprint "eagle-import:1X01_WITHOUT_TEXT")
      (libsource (lib "eagle-import") (part "M01PTH_WITHOUT_TEXT"))
    )
    (comp (ref "JP222")
      (value "M01PTH_WITHOUT_TEXT")
      (footprint "eagle-import:1X01_WITHOUT_TEXT")
      (libsource (lib "eagle-import") (part "M01PTH_WITHOUT_TEXT"))
    )
    (comp (ref "JP223")
      (value "M01PTH_WITHOUT_TEXT")
      (footprint "eagle-import:1X01_WITHOUT_TEXT")
      (libsource (lib "eagle-import") (part "M01PTH_WITHOUT_TEXT"))
    )
    (comp (ref "JP224")
      (value "M01PTH_WITHOUT_TEXT")
      (footprint "eagle-import:1X01_WITHOUT_TEXT")
      (libsource (lib "eagle-import") (part "M01PTH_WITHOUT_TEXT"))
    )
    (comp (ref "JP225")
      (value "M01PTH_WITHOUT_TEXT")
      (footprint "eagle-import:1X01_WITHOUT_TEXT")
      (libsource (lib "eagle-import") (part "M01PTH_WITHOUT_TEXT"))
    )
    (comp (ref "JP226")
      (value "M01PTH_WITHOUT_TEXT")
      (footprint "eagle-import:1X01_WITHOUT_TEXT")
      (libsource (lib "eagle-import") (part "M01PTH_WITHOUT_TEXT"))
    )
    (comp (ref "JP227")
      (value "M01PTH_WITHOUT_TEXT")
      (footprint "eagle-import:1X01_WITHOUT_TEXT")
      (libsource (lib "eagle-import") (part "M01PTH_WITHOUT_TEXT"))
    )
    (comp (ref "JP228")
      (value "M01PTH_WITHOUT_TEXT")
      (footprint "eagle-import:1X01_WITHOUT_TEXT")
      (libsource (lib "eagle-import") (part "M01PTH_WITHOUT_TEXT"))
    )
    (comp (ref "JP229")
      (value "M01PTH_WITHOUT_TEXT")
      (footprint "eagle-import:1X01_WITHOUT_TEXT")
      (libsource (lib "eagle-import") (part "M01PTH_WITHOUT_TEXT"))
    )
    (comp (ref "JP230")
      (value "M01PTH_WITHOUT_TEXT")
      (footprint "eagle-import:1X01_WITHOUT_TEXT")
      (libsource (lib "eagle-import") (part "M01PTH_WITHOUT_TEXT"))
    )
    (comp (ref "JP231")
      (value "M01PTH_WITHOUT_TEXT")
      (footprint "eagle-import:1X01_WITHOUT_TEXT")
      (libsource (lib "eagle-import") (part "M01PTH_WITHOUT_TEXT"))
    )
    (comp (ref "JP232")
      (value "M01PTH_WITHOUT_TEXT")
      (footprint "eagle-import:1X01_WITHOUT_TEXT")
      (libsource (lib "eagle-import") (part "M01PTH_WITHOUT_TEXT"))
    )
    (comp (ref "JP233")
      (value "M01PTH_WITHOUT_TEXT")
      (footprint "eagle-import:1X01_WITHOUT_TEXT")
      (libsource (lib "eagle-import") (part "M01PTH_WITHOUT_TEXT"))
    )
    (comp (ref "JP234")
      (value "M01PTH_WITHOUT_TEXT")
      (footprint "eagle-import:1X01_WITHOUT_TEXT")
      (libsource (lib "eagle-import") (part "M01PTH_WITHOUT_TEXT"))
    )
    (comp (ref "JP235")
      (value "M01PTH_WITHOUT_TEXT")
      (footprint "eagle-import:1X01_WITHOUT_TEXT")
      (libsource (lib "eagle-import") (part "M01PTH_WITHOUT_TEXT"))
    )
    (comp (ref "JP236")
      (value "M01PTH_WITHOUT_TEXT")
      (footprint "eagle-import:1X01_WITHOUT_TEXT")
      (libsource (lib "eagle-import") (part "M01PTH_WITHOUT_TEXT"))
    )
    (comp (ref "JP237")
      (value "M01PTH_WITHOUT_TEXT")
      (footprint "eagle-import:1X01_WITHOUT_TEXT")
      (libsource (lib "eagle-import") (part "M01PTH_WITHOUT_TEXT"))
    )
    (comp (ref "JP238")
      (value "M01PTH_WITHOUT_TEXT")
      (footprint "eagle-import:1X01_WITHOUT_TEXT")
      (libsource (lib "eagle-import") (part "M01PTH_WITHOUT_TEXT"))
    )
    (comp (ref "JP239")
      (value "M01PTH_WITHOUT_TEXT")
      (footprint "eagle-import:1X01_WITHOUT_TEXT")
      (libsource (lib "eagle-import") (part "M01PTH_WITHOUT_TEXT"))
    )
    (comp (ref "JP240")
      (value "M01PTH_WITHOUT_TEXT")
      (footprint "eagle-import:1X01_WITHOUT_TEXT")
      (libsource (lib "eagle-import") (part "M01PTH_WITHOUT_TEXT"))
    )
    (comp (ref "JP241")
      (value "M01PTH_WITHOUT_TEXT")
      (footprint "eagle-import:1X01_WITHOUT_TEXT")
      (libsource (lib "eagle-import") (part "M01PTH_WITHOUT_TEXT"))
    )
    (comp (ref "JP242")
      (value "M01PTH_WITHOUT_TEXT")
      (footprint "eagle-import:1X01_WITHOUT_TEXT")
      (libsource (lib "eagle-import") (part "M01PTH_WITHOUT_TEXT"))
    )
    (comp (ref "JP243")
      (value "M01PTH_WITHOUT_TEXT")
      (footprint "eagle-import:1X01_WITHOUT_TEXT")
      (libsource (lib "eagle-import") (part "M01PTH_WITHOUT_TEXT"))
    )
    (comp (ref "JP244")
      (value "M01PTH_WITHOUT_TEXT")
      (footprint "eagle-import:1X01_WITHOUT_TEXT")
      (libsource (lib "eagle-import") (part "M01PTH_WITHOUT_TEXT"))
    )
    (comp (ref "JP245")
      (value "M01PTH_WITHOUT_TEXT")
      (footprint "eagle-import:1X01_WITHOUT_TEXT")
      (libsource (lib "eagle-import") (part "M01PTH_WITHOUT_TEXT"))
    )
    (comp (ref "JP246")
      (value "M01PTH_WITHOUT_TEXT")
      (footprint "eagle-import:1X01_WITHOUT_TEXT")
      (libsource (lib "eagle-import") (part "M01PTH_WITHOUT_TEXT"))
    )
    (comp (ref "JP247")
      (value "M01PTH_WITHOUT_TEXT")
      (footprint "eagle-import:1X01_WITHOUT_TEXT")
      (libsource (lib "eagle-import") (part "M01PTH_WITHOUT_TEXT"))
    )
    (comp (ref "JP248")
      (value "M01PTH_WITHOUT_TEXT")
      (footprint "eagle-import:1X01_WITHOUT_TEXT")
      (libsource (lib "eagle-import") (part "M01PTH_WITHOUT_TEXT"))
    )
    (comp (ref "JP249")
      (value "M01PTH_WITHOUT_TEXT")
      (footprint "eagle-import:1X01_WITHOUT_TEXT")
      (libsource (lib "eagle-import") (part "M01PTH_WITHOUT_TEXT"))
    )
    (comp (ref "JP250")
      (value "M01PTH_WITHOUT_TEXT")
      (footprint "eagle-import:1X01_WITHOUT_TEXT")
      (libsource (lib "eagle-import") (part "M01PTH_WITHOUT_TEXT"))
    )
    (comp (ref "JP251")
      (value "M01PTH_WITHOUT_TEXT")
      (footprint "eagle-import:1X01_WITHOUT_TEXT")
      (libsource (lib "eagle-import") (part "M01PTH_WITHOUT_TEXT"))
    )
    (comp (ref "JP252")
      (value "M01PTH_WITHOUT_TEXT")
      (footprint "eagle-import:1X01_WITHOUT_TEXT")
      (libsource (lib "eagle-import") (part "M01PTH_WITHOUT_TEXT"))
    )
    (comp (ref "JP253")
      (value "M01PTH_WITHOUT_TEXT")
      (footprint "eagle-import:1X01_WITHOUT_TEXT")
      (libsource (lib "eagle-import") (part "M01PTH_WITHOUT_TEXT"))
    )
    (comp (ref "JP254")
      (value "M01PTH_WITHOUT_TEXT")
      (footprint "eagle-import:1X01_WITHOUT_TEXT")
      (libsource (lib "eagle-import") (part "M01PTH_WITHOUT_TEXT"))
    )
    (comp (ref "JP255")
      (value "M01PTH_WITHOUT_TEXT")
      (footprint "eagle-import:1X01_WITHOUT_TEXT")
      (libsource (lib "eagle-import") (part "M01PTH_WITHOUT_TEXT"))
    )
    (comp (ref "JP256")
      (value "M01PTH_WITHOUT_TEXT")
      (footprint "eagle-import:1X01_WITHOUT_TEXT")
      (libsource (lib "eagle-import") (part "M01PTH_WITHOUT_TEXT"))
    )
    (comp (ref "JP257")
      (value "M01PTH_WITHOUT_TEXT")
      (footprint "eagle-import:1X01_WITHOUT_TEXT")
      (libsource (lib "eagle-import") (part "M01PTH_WITHOUT_TEXT"))
    )
    (comp (ref "JP258")
      (value "M01PTH_WITHOUT_TEXT")
      (footprint "eagle-import:1X01_WITHOUT_TEXT")
      (libsource (lib "eagle-import") (part "M01PTH_WITHOUT_TEXT"))
    )
    (comp (ref "JP259")
      (value "M01PTH_WITHOUT_TEXT")
      (footprint "eagle-import:1X01_WITHOUT_TEXT")
      (libsource (lib "eagle-import") (part "M01PTH_WITHOUT_TEXT"))
    )
    (comp (ref "JP260")
      (value "M01PTH_WITHOUT_TEXT")
      (footprint "eagle-import:1X01_WITHOUT_TEXT")
      (libsource (lib "eagle-import") (part "M01PTH_WITHOUT_TEXT"))
    )
    (comp (ref "JP261")
      (value "M01PTH_WITHOUT_TEXT")
      (footprint "eagle-import:1X01_WITHOUT_TEXT")
      (libsource (lib "eagle-import") (part "M01PTH_WITHOUT_TEXT"))
    )
    (comp (ref "JP262")
      (value "M01PTH_WITHOUT_TEXT")
      (footprint "eagle-import:1X01_WITHOUT_TEXT")
      (libsource (lib "eagle-import") (part "M01PTH_WITHOUT_TEXT"))
    )
    (comp (ref "JP263")
      (value "M01PTH_WITHOUT_TEXT")
      (footprint "eagle-import:1X01_WITHOUT_TEXT")
      (libsource (lib "eagle-import") (part "M01PTH_WITHOUT_TEXT"))
    )
    (comp (ref "JP264")
      (value "M01PTH_WITHOUT_TEXT")
      (footprint "eagle-import:1X01_WITHOUT_TEXT")
      (libsource (lib "eagle-import") (part "M01PTH_WITHOUT_TEXT"))
    )
    (comp (ref "JP265")
      (value "M01PTH_WITHOUT_TEXT")
      (footprint "eagle-import:1X01_WITHOUT_TEXT")
      (libsource (lib "eagle-import") (part "M01PTH_WITHOUT_TEXT"))
    )
    (comp (ref "JP266")
      (value "M01PTH_WITHOUT_TEXT")
      (footprint "eagle-import:1X01_WITHOUT_TEXT")
      (libsource (lib "eagle-import") (part "M01PTH_WITHOUT_TEXT"))
    )
    (comp (ref "JP267")
      (value "M01PTH_WITHOUT_TEXT")
      (footprint "eagle-import:1X01_WITHOUT_TEXT")
      (libsource (lib "eagle-import") (part "M01PTH_WITHOUT_TEXT"))
    )
    (comp (ref "JP268")
      (value "M01PTH_WITHOUT_TEXT")
      (footprint "eagle-import:1X01_WITHOUT_TEXT")
      (libsource (lib "eagle-import") (part "M01PTH_WITHOUT_TEXT"))
    )
    (comp (ref "JP269")
      (value "M01PTH_WITHOUT_TEXT")
      (footprint "eagle-import:1X01_WITHOUT_TEXT")
      (libsource (lib "eagle-import") (part "M01PTH_WITHOUT_TEXT"))
    )
    (comp (ref "JP270")
      (value "M01PTH_WITHOUT_TEXT")
      (footprint "eagle-import:1X01_WITHOUT_TEXT")
      (libsource (lib "eagle-import") (part "M01PTH_WITHOUT_TEXT"))
    )
    (comp (ref "JP271")
      (value "M01PTH_WITHOUT_TEXT")
      (footprint "eagle-import:1X01_WITHOUT_TEXT")
      (libsource (lib "eagle-import") (part "M01PTH_WITHOUT_TEXT"))
    )
    (comp (ref "JP272")
      (value "M01PTH_WITHOUT_TEXT")
      (footprint "eagle-import:1X01_WITHOUT_TEXT")
      (libsource (lib "eagle-import") (part "M01PTH_WITHOUT_TEXT"))
    )
    (comp (ref "JP273")
      (value "M01PTH_WITHOUT_TEXT")
      (footprint "eagle-import:1X01_WITHOUT_TEXT")
      (libsource (lib "eagle-import") (part "M01PTH_WITHOUT_TEXT"))
    )
    (comp (ref "JP274")
      (value "M01PTH_WITHOUT_TEXT")
      (footprint "eagle-import:1X01_WITHOUT_TEXT")
      (libsource (lib "eagle-import") (part "M01PTH_WITHOUT_TEXT"))
    )
    (comp (ref "JP275")
      (value "M01PTH_WITHOUT_TEXT")
      (footprint "eagle-import:1X01_WITHOUT_TEXT")
      (libsource (lib "eagle-import") (part "M01PTH_WITHOUT_TEXT"))
    )
    (comp (ref "JP276")
      (value "M01PTH_WITHOUT_TEXT")
      (footprint "eagle-import:1X01_WITHOUT_TEXT")
      (libsource (lib "eagle-import") (part "M01PTH_WITHOUT_TEXT"))
    )
    (comp (ref "JP277")
      (value "M01PTH_WITHOUT_TEXT")
      (footprint "eagle-import:1X01_WITHOUT_TEXT")
      (libsource (lib "eagle-import") (part "M01PTH_WITHOUT_TEXT"))
    )
    (comp (ref "JP278")
      (value "M01PTH_WITHOUT_TEXT")
      (footprint "eagle-import:1X01_WITHOUT_TEXT")
      (libsource (lib "eagle-import") (part "M01PTH_WITHOUT_TEXT"))
    )
    (comp (ref "JP279")
      (value "M01PTH_WITHOUT_TEXT")
      (footprint "eagle-import:1X01_WITHOUT_TEXT")
      (libsource (lib "eagle-import") (part "M01PTH_WITHOUT_TEXT"))
    )
    (comp (ref "JP280")
      (value "M01PTH_WITHOUT_TEXT")
      (footprint "eagle-import:1X01_WITHOUT_TEXT")
      (libsource (lib "eagle-import") (part "M01PTH_WITHOUT_TEXT"))
    )
    (comp (ref "JP281")
      (value "M01PTH_WITHOUT_TEXT")
      (footprint "eagle-import:1X01_WITHOUT_TEXT")
      (libsource (lib "eagle-import") (part "M01PTH_WITHOUT_TEXT"))
    )
    (comp (ref "JP282")
      (value "M01PTH_WITHOUT_TEXT")
      (footprint "eagle-import:1X01_WITHOUT_TEXT")
      (libsource (lib "eagle-import") (part "M01PTH_WITHOUT_TEXT"))
    )
    (comp (ref "JP283")
      (value "M01PTH_WITHOUT_TEXT")
      (footprint "eagle-import:1X01_WITHOUT_TEXT")
      (libsource (lib "eagle-import") (part "M01PTH_WITHOUT_TEXT"))
    )
    (comp (ref "JP284")
      (value "M01PTH_WITHOUT_TEXT")
      (footprint "eagle-import:1X01_WITHOUT_TEXT")
      (libsource (lib "eagle-import") (part "M01PTH_WITHOUT_TEXT"))
    )
    (comp (ref "JP285")
      (value "M01PTH_WITHOUT_TEXT")
      (footprint "eagle-import:1X01_WITHOUT_TEXT")
      (libsource (lib "eagle-import") (part "M01PTH_WITHOUT_TEXT"))
    )
    (comp (ref "JP286")
      (value "M01PTH_WITHOUT_TEXT")
      (footprint "eagle-import:1X01_WITHOUT_TEXT")
      (libsource (lib "eagle-import") (part "M01PTH_WITHOUT_TEXT"))
    )
    (comp (ref "JP287")
      (value "M01PTH_WITHOUT_TEXT")
      (footprint "eagle-import:1X01_WITHOUT_TEXT")
      (libsource (lib "eagle-import") (part "M01PTH_WITHOUT_TEXT"))
    )
    (comp (ref "JP288")
      (value "M01PTH_WITHOUT_TEXT")
      (footprint "eagle-import:1X01_WITHOUT_TEXT")
      (libsource (lib "eagle-import") (part "M01PTH_WITHOUT_TEXT"))
    )
    (comp (ref "JP289")
      (value "M01PTH_WITHOUT_TEXT")
      (footprint "eagle-import:1X01_WITHOUT_TEXT")
      (libsource (lib "eagle-import") (part "M01PTH_WITHOUT_TEXT"))
    )
    (comp (ref "JP290")
      (value "M01PTH_WITHOUT_TEXT")
      (footprint "eagle-import:1X01_WITHOUT_TEXT")
      (libsource (lib "eagle-import") (part "M01PTH_WITHOUT_TEXT"))
    )
    (comp (ref "JP291")
      (value "M01PTH_WITHOUT_TEXT")
      (footprint "eagle-import:1X01_WITHOUT_TEXT")
      (libsource (lib "eagle-import") (part "M01PTH_WITHOUT_TEXT"))
    )
    (comp (ref "JP292")
      (value "M01PTH_WITHOUT_TEXT")
      (footprint "eagle-import:1X01_WITHOUT_TEXT")
      (libsource (lib "eagle-import") (part "M01PTH_WITHOUT_TEXT"))
    )
    (comp (ref "JP293")
      (value "M01PTH_WITHOUT_TEXT")
      (footprint "eagle-import:1X01_WITHOUT_TEXT")
      (libsource (lib "eagle-import") (part "M01PTH_WITHOUT_TEXT"))
    )
    (comp (ref "JP294")
      (value "M01PTH_WITHOUT_TEXT")
      (footprint "eagle-import:1X01_WITHOUT_TEXT")
      (libsource (lib "eagle-import") (part "M01PTH_WITHOUT_TEXT"))
    )
    (comp (ref "JP295")
      (value "M01PTH_WITHOUT_TEXT")
      (footprint "eagle-import:1X01_WITHOUT_TEXT")
      (libsource (lib "eagle-import") (part "M01PTH_WITHOUT_TEXT"))
    )
    (comp (ref "JP296")
      (value "M01PTH_WITHOUT_TEXT")
      (footprint "eagle-import:1X01_WITHOUT_TEXT")
      (libsource (lib "eagle-import") (part "M01PTH_WITHOUT_TEXT"))
    )
    (comp (ref "JP297")
      (value "M01PTH_WITHOUT_TEXT")
      (footprint "eagle-import:1X01_WITHOUT_TEXT")
      (libsource (lib "eagle-import") (part "M01PTH_WITHOUT_TEXT"))
    )
    (comp (ref "JP298")
      (value "M01PTH_WITHOUT_TEXT")
      (footprint "eagle-import:1X01_WITHOUT_TEXT")
      (libsource (lib "eagle-import") (part "M01PTH_WITHOUT_TEXT"))
    )
    (comp (ref "JP299")
      (value "M01PTH_WITHOUT_TEXT")
      (footprint "eagle-import:1X01_WITHOUT_TEXT")
      (libsource (lib "eagle-import") (part "M01PTH_WITHOUT_TEXT"))
    )
    (comp (ref "JP300")
      (value "M01PTH_WITHOUT_TEXT")
      (footprint "eagle-import:1X01_WITHOUT_TEXT")
      (libsource (lib "eagle-import") (part "M01PTH_WITHOUT_TEXT"))
    )
    (comp (ref "JP901")
      (value "M01PTH_SMD_3.25X0.85MM_NO_SILK")
      (footprint "eagle-import:1X01_SMD_3.25X0.85MM_NO_SILK")
      (libsource (lib "eagle-import") (part "M01PTH_SMD_3.25X0.85MM_NO_SILK"))
    )
    (comp (ref "JP902")
      (value "M01PTH_SMD_3.25X0.85MM_NO_SILK")
      (footprint "eagle-import:1X01_SMD_3.25X0.85MM_NO_SILK")
      (libsource (lib "eagle-import") (part "M01PTH_SMD_3.25X0.85MM_NO_SILK"))
    )
    (comp (ref "JP903")
      (value "M01PTH_SMD_3.25X0.85MM_NO_SILK")
      (footprint "eagle-import:1X01_SMD_3.25X0.85MM_NO_SILK")
      (libsource (lib "eagle-import") (part "M01PTH_SMD_3.25X0.85MM_NO_SILK"))
    )
    (comp (ref "JP904")
      (value "M01PTH_SMD_3.25X0.85MM_NO_SILK")
      (footprint "eagle-import:1X01_SMD_3.25X0.85MM_NO_SILK")
      (libsource (lib "eagle-import") (part "M01PTH_SMD_3.25X0.85MM_NO_SILK"))
    )
    (comp (ref "JP905")
      (value "M01PTH_SMD_3.25X0.85MM_NO_SILK")
      (footprint "eagle-import:1X01_SMD_3.25X0.85MM_NO_SILK")
      (libsource (lib "eagle-import") (part "M01PTH_SMD_3.25X0.85MM_NO_SILK"))
    )
    (comp (ref "JP906")
      (value "M01PTH_SMD_3.25X0.85MM_NO_SILK")
      (footprint "eagle-import:1X01_SMD_3.25X0.85MM_NO_SILK")
      (libsource (lib "eagle-import") (part "M01PTH_SMD_3.25X0.85MM_NO_SILK"))
    )
    (comp (ref "JP907")
      (value "M01PTH_SMD_3.25X0.85MM_NO_SILK")
      (footprint "eagle-import:1X01_SMD_3.25X0.85MM_NO_SILK")
      (libsource (lib "eagle-import") (part "M01PTH_SMD_3.25X0.85MM_NO_SILK"))
    )
    (comp (ref "JP908")
      (value "M01PTH_SMD_3.25X0.85MM_NO_SILK")
      (footprint "eagle-import:1X01_SMD_3.25X0.85MM_NO_SILK")
      (libsource (lib "eagle-import") (part "M01PTH_SMD_3.25X0.85MM_NO_SILK"))
    )
    (comp (ref "JP909")
      (value "M01PTH_SMD_3.25X0.85MM_NO_SILK")
      (footprint "eagle-import:1X01_SMD_3.25X0.85MM_NO_SILK")
      (libsource (lib "eagle-import") (part "M01PTH_SMD_3.25X0.85MM_NO_SILK"))
    )
    (comp (ref "JP910")
      (value "M01PTH_SMD_3.25X0.85MM_NO_SILK")
      (footprint "eagle-import:1X01_SMD_3.25X0.85MM_NO_SILK")
      (libsource (lib "eagle-import") (part "M01PTH_SMD_3.25X0.85MM_NO_SILK"))
    )
    (comp (ref "JP911")
      (value "M01PTH_SMD_3.25X0.85MM_NO_SILK")
      (footprint "eagle-import:1X01_SMD_3.25X0.85MM_NO_SILK")
      (libsource (lib "eagle-import") (part "M01PTH_SMD_3.25X0.85MM_NO_SILK"))
    )
    (comp (ref "JP912")
      (value "M01PTH_SMD_3.25X0.85MM_NO_SILK")
      (footprint "eagle-import:1X01_SMD_3.25X0.85MM_NO_SILK")
      (libsource (lib "eagle-import") (part "M01PTH_SMD_3.25X0.85MM_NO_SILK"))
    )
    (comp (ref "JP913")
      (value "M01PTH_SMD_3.25X0.85MM_NO_SILK")
      (footprint "eagle-import:1X01_SMD_3.25X0.85MM_NO_SILK")
      (libsource (lib "eagle-import") (part "M01PTH_SMD_3.25X0.85MM_NO_SILK"))
    )
    (comp (ref "JP914")
      (value "M01PTH_SMD_3.25X0.85MM_NO_SILK")
      (footprint "eagle-import:1X01_SMD_3.25X0.85MM_NO_SILK")
      (libsource (lib "eagle-import") (part "M01PTH_SMD_3.25X0.85MM_NO_SILK"))
    )
    (comp (ref "JP915")
      (value "M01PTH_SMD_3.25X0.85MM_NO_SILK")
      (footprint "eagle-import:1X01_SMD_3.25X0.85MM_NO_SILK")
      (libsource (lib "eagle-import") (part "M01PTH_SMD_3.25X0.85MM_NO_SILK"))
    )
    (comp (ref "JP916")
      (value "M01PTH_SMD_3.25X0.85MM_NO_SILK")
      (footprint "eagle-import:1X01_SMD_3.25X0.85MM_NO_SILK")
      (libsource (lib "eagle-import") (part "M01PTH_SMD_3.25X0.85MM_NO_SILK"))
    )
    (comp (ref "JP917")
      (value "M01PTH_SMD_3.25X0.85MM_NO_SILK")
      (footprint "eagle-import:1X01_SMD_3.25X0.85MM_NO_SILK")
      (libsource (lib "eagle-import") (part "M01PTH_SMD_3.25X0.85MM_NO_SILK"))
    )
    (comp (ref "JP918")
      (value "M01PTH_SMD_3.25X0.85MM_NO_SILK")
      (footprint "eagle-import:1X01_SMD_3.25X0.85MM_NO_SILK")
      (libsource (lib "eagle-import") (part "M01PTH_SMD_3.25X0.85MM_NO_SILK"))
    )
    (comp (ref "JP919")
      (value "M01PTH_SMD_3.25X0.85MM_NO_SILK")
      (footprint "eagle-import:1X01_SMD_3.25X0.85MM_NO_SILK")
      (libsource (lib "eagle-import") (part "M01PTH_SMD_3.25X0.85MM_NO_SILK"))
    )
    (comp (ref "JP920")
      (value "M01PTH_SMD_3.25X0.85MM_NO_SILK")
      (footprint "eagle-import:1X01_SMD_3.25X0.85MM_NO_SILK")
      (libsource (lib "eagle-import") (part "M01PTH_SMD_3.25X0.85MM_NO_SILK"))
    )
    (comp (ref "JP921")
      (value "M01PTH_SMD_3.25X0.85MM_NO_SILK")
      (footprint "eagle-import:1X01_SMD_3.25X0.85MM_NO_SILK")
      (libsource (lib "eagle-import") (part "M01PTH_SMD_3.25X0.85MM_NO_SILK"))
    )
    (comp (ref "JP922")
      (value "M01PTH_SMD_3.25X0.85MM_NO_SILK")
      (footprint "eagle-import:1X01_SMD_3.25X0.85MM_NO_SILK")
      (libsource (lib "eagle-import") (part "M01PTH_SMD_3.25X0.85MM_NO_SILK"))
    )
    (comp (ref "JP923")
      (value "M01PTH_SMD_3.25X0.85MM_NO_SILK")
      (footprint "eagle-import:1X01_SMD_3.25X0.85MM_NO_SILK")
      (libsource (lib "eagle-import") (part "M01PTH_SMD_3.25X0.85MM_NO_SILK"))
    )
    (comp (ref "JP924")
      (value "M01PTH_SMD_3.25X0.85MM_NO_SILK")
      (footprint "eagle-import:1X01_SMD_3.25X0.85MM_NO_SILK")
      (libsource (lib "eagle-import") (part "M01PTH_SMD_3.25X0.85MM_NO_SILK"))
    )
    (comp (ref "JP925")
      (value "M01PTH_SMD_3.25X0.85MM_NO_SILK")
      (footprint "eagle-import:1X01_SMD_3.25X0.85MM_NO_SILK")
      (libsource (lib "eagle-import") (part "M01PTH_SMD_3.25X0.85MM_NO_SILK"))
    )
    (comp (ref "JP926")
      (value "M01PTH_SMD_3.25X0.85MM_NO_SILK")
      (footprint "eagle-import:1X01_SMD_3.25X0.85MM_NO_SILK")
      (libsource (lib "eagle-import") (part "M01PTH_SMD_3.25X0.85MM_NO_SILK"))
    )
    (comp (ref "JP927")
      (value "M01PTH_SMD_3.25X0.85MM_NO_SILK")
      (footprint "eagle-import:1X01_SMD_3.25X0.85MM_NO_SILK")
      (libsource (lib "eagle-import") (part "M01PTH_SMD_3.25X0.85MM_NO_SILK"))
    )
    (comp (ref "JP928")
      (value "M01PTH_SMD_3.25X0.85MM_NO_SILK")
      (footprint "eagle-import:1X01_SMD_3.25X0.85MM_NO_SILK")
      (libsource (lib "eagle-import") (part "M01PTH_SMD_3.25X0.85MM_NO_SILK"))
    )
    (comp (ref "JP929")
      (value "M01PTH_SMD_3.25X0.85MM_NO_SILK")
      (footprint "eagle-import:1X01_SMD_3.25X0.85MM_NO_SILK")
      (libsource (lib "eagle-import") (part "M01PTH_SMD_3.25X0.85MM_NO_SILK"))
    )
    (comp (ref "JP930")
      (value "M01PTH_SMD_3.25X0.85MM_NO_SILK")
      (footprint "eagle-import:1X01_SMD_3.25X0.85MM_NO_SILK")
      (libsource (lib "eagle-import") (part "M01PTH_SMD_3.25X0.85MM_NO_SILK"))
    )
    (comp (ref "JP931")
      (value "M01PTH_SMD_3.25X0.85MM_NO_SILK")
      (footprint "eagle-import:1X01_SMD_3.25X0.85MM_NO_SILK")
      (libsource (lib "eagle-import") (part "M01PTH_SMD_3.25X0.85MM_NO_SILK"))
    )
    (comp (ref "JP932")
      (value "M01PTH_SMD_3.25X0.85MM_NO_SILK")
      (footprint "eagle-import:1X01_SMD_3.25X0.85MM_NO_SILK")
      (libsource (lib "eagle-import") (part "M01PTH_SMD_3.25X0.85MM_NO_SILK"))
    )
    (comp (ref "JP933")
      (value "M01PTH_SMD_3.25X0.85MM_NO_SILK")
      (footprint "eagle-import:1X01_SMD_3.25X0.85MM_NO_SILK")
      (libsource (lib "eagle-import") (part "M01PTH_SMD_3.25X0.85MM_NO_SILK"))
    )
    (comp (ref "JP934")
      (value "M01PTH_SMD_3.25X0.85MM_NO_SILK")
      (footprint "eagle-import:1X01_SMD_3.25X0.85MM_NO_SILK")
      (libsource (lib "eagle-import") (part "M01PTH_SMD_3.25X0.85MM_NO_SILK"))
    )
    (comp (ref "JP935")
      (value "M01PTH_SMD_3.25X0.85MM_NO_SILK")
      (footprint "eagle-import:1X01_SMD_3.25X0.85MM_NO_SILK")
      (libsource (lib "eagle-import") (part "M01PTH_SMD_3.25X0.85MM_NO_SILK"))
    )
    (comp (ref "JP936")
      (value "M01PTH_SMD_3.25X0.85MM_NO_SILK")
      (footprint "eagle-import:1X01_SMD_3.25X0.85MM_NO_SILK")
      (libsource (lib "eagle-import") (part "M01PTH_SMD_3.25X0.85MM_NO_SILK"))
    )
    (comp (ref "JP937")
      (value "M01PTH_SMD_3.25X0.85MM_NO_SILK")
      (footprint "eagle-import:1X01_SMD_3.25X0.85MM_NO_SILK")
      (libsource (lib "eagle-import") (part "M01PTH_SMD_3.25X0.85MM_NO_SILK"))
    )
    (comp (ref "JP938")
      (value "M01PTH_SMD_3.25X0.85MM_NO_SILK")
      (footprint "eagle-import:1X01_SMD_3.25X0.85MM_NO_SILK")
      (libsource (lib "eagle-import") (part "M01PTH_SMD_3.25X0.85MM_NO_SILK"))
    )
    (comp (ref "JP939")
      (value "M01PTH_SMD_3.25X0.85MM_NO_SILK")
      (footprint "eagle-import:1X01_SMD_3.25X0.85MM_NO_SILK")
      (libsource (lib "eagle-import") (part "M01PTH_SMD_3.25X0.85MM_NO_SILK"))
    )
    (comp (ref "JP940")
      (value "M01PTH_SMD_3.25X0.85MM_NO_SILK")
      (footprint "eagle-import:1X01_SMD_3.25X0.85MM_NO_SILK")
      (libsource (lib "eagle-import") (part "M01PTH_SMD_3.25X0.85MM_NO_SILK"))
    )
    (comp (ref "JP941")
      (value "M01PTH_SMD_3.25X0.85MM_NO_SILK")
      (footprint "eagle-import:1X01_SMD_3.25X0.85MM_NO_SILK")
      (libsource (lib "eagle-import") (part "M01PTH_SMD_3.25X0.85MM_NO_SILK"))
    )
    (comp (ref "JP942")
      (value "M01PTH_SMD_3.25X0.85MM_NO_SILK")
      (footprint "eagle-import:1X01_SMD_3.25X0.85MM_NO_SILK")
      (libsource (lib "eagle-import") (part "M01PTH_SMD_3.25X0.85MM_NO_SILK"))
    )
    (comp (ref "JP943")
      (value "M01PTH_SMD_3.25X0.85MM_NO_SILK")
      (footprint "eagle-import:1X01_SMD_3.25X0.85MM_NO_SILK")
      (libsource (lib "eagle-import") (part "M01PTH_SMD_3.25X0.85MM_NO_SILK"))
    )
    (comp (ref "JP944")
      (value "M01PTH_SMD_3.25X0.85MM_NO_SILK")
      (footprint "eagle-import:1X01_SMD_3.25X0.85MM_NO_SILK")
      (libsource (lib "eagle-import") (part "M01PTH_SMD_3.25X0.85MM_NO_SILK"))
    )
    (comp (ref "JP945")
      (value "M01PTH_SMD_3.25X0.85MM_NO_SILK")
      (footprint "eagle-import:1X01_SMD_3.25X0.85MM_NO_SILK")
      (libsource (lib "eagle-import") (part "M01PTH_SMD_3.25X0.85MM_NO_SILK"))
    )
    (comp (ref "JP946")
      (value "M01PTH_SMD_3.25X0.85MM_NO_SILK")
      (footprint "eagle-import:1X01_SMD_3.25X0.85MM_NO_SILK")
      (libsource (lib "eagle-import") (part "M01PTH_SMD_3.25X0.85MM_NO_SILK"))
    )
    (comp (ref "JP947")
      (value "M01PTH_SMD_3.25X0.85MM_NO_SILK")
      (footprint "eagle-import:1X01_SMD_3.25X0.85MM_NO_SILK")
      (libsource (lib "eagle-import") (part "M01PTH_SMD_3.25X0.85MM_NO_SILK"))
    )
    (comp (ref "JP948")
      (value "M01PTH_SMD_3.25X0.85MM_NO_SILK")
      (footprint "eagle-import:1X01_SMD_3.25X0.85MM_NO_SILK")
      (libsource (lib "eagle-import") (part "M01PTH_SMD_3.25X0.85MM_NO_SILK"))
    )
    (comp (ref "JP949")
      (value "M01PTH_SMD_3.25X0.85MM_NO_SILK")
      (footprint "eagle-import:1X01_SMD_3.25X0.85MM_NO_SILK")
      (libsource (lib "eagle-import") (part "M01PTH_SMD_3.25X0.85MM_NO_SILK"))
    )
    (comp (ref "JP950")
      (value "M01PTH_SMD_3.25X0.85MM_NO_SILK")
      (footprint "eagle-import:1X01_SMD_3.25X0.85MM_NO_SILK")
      (libsource (lib "eagle-import") (part "M01PTH_SMD_3.25X0.85MM_NO_SILK"))
    )
    (comp (ref "JP951")
      (value "M01PTH_SMD_3.25X0.85MM_NO_SILK")
      (footprint "eagle-import:1X01_SMD_3.25X0.85MM_NO_SILK")
      (libsource (lib "eagle-import") (part "M01PTH_SMD_3.25X0.85MM_NO_SILK"))
    )
    (comp (ref "JP952")
      (value "M01PTH_SMD_3.25X0.85MM_NO_SILK")
      (footprint "eagle-import:1X01_SMD_3.25X0.85MM_NO_SILK")
      (libsource (lib "eagle-import") (part "M01PTH_SMD_3.25X0.85MM_NO_SILK"))
    )
    (comp (ref "JP953")
      (value "M01PTH_SMD_3.25X0.85MM_NO_SILK")
      (footprint "eagle-import:1X01_SMD_3.25X0.85MM_NO_SILK")
      (libsource (lib "eagle-import") (part "M01PTH_SMD_3.25X0.85MM_NO_SILK"))
    )
    (comp (ref "JP954")
      (value "M01PTH_SMD_3.25X0.85MM_NO_SILK")
      (footprint "eagle-import:1X01_SMD_3.25X0.85MM_NO_SILK")
      (libsource (lib "eagle-import") (part "M01PTH_SMD_3.25X0.85MM_NO_SILK"))
    )
    (comp (ref "JP955")
      (value "M01PTH_SMD_3.25X0.85MM_NO_SILK")
      (footprint "eagle-import:1X01_SMD_3.25X0.85MM_NO_SILK")
      (libsource (lib "eagle-import") (part "M01PTH_SMD_3.25X0.85MM_NO_SILK"))
    )
    (comp (ref "JP956")
      (value "M01PTH_SMD_3.25X0.85MM_NO_SILK")
      (footprint "eagle-import:1X01_SMD_3.25X0.85MM_NO_SILK")
      (libsource (lib "eagle-import") (part "M01PTH_SMD_3.25X0.85MM_NO_SILK"))
    )
    (comp (ref "JP957")
      (value "M01PTH_SMD_3.25X0.85MM_NO_SILK")
      (footprint "eagle-import:1X01_SMD_3.25X0.85MM_NO_SILK")
      (libsource (lib "eagle-import") (part "M01PTH_SMD_3.25X0.85MM_NO_SILK"))
    )
    (comp (ref "JP958")
      (value "M01PTH_SMD_3.25X0.85MM_NO_SILK")
      (footprint "eagle-import:1X01_SMD_3.25X0.85MM_NO_SILK")
      (libsource (lib "eagle-import") (part "M01PTH_SMD_3.25X0.85MM_NO_SILK"))
    )
    (comp (ref "JP959")
      (value "M01PTH_SMD_3.25X0.85MM_NO_SILK")
      (footprint "eagle-import:1X01_SMD_3.25X0.85MM_NO_SILK")
      (libsource (lib "eagle-import") (part "M01PTH_SMD_3.25X0.85MM_NO_SILK"))
    )
    (comp (ref "JP960")
      (value "M01PTH_SMD_3.25X0.85MM_NO_SILK")
      (footprint "eagle-import:1X01_SMD_3.25X0.85MM_NO_SILK")
      (libsource (lib "eagle-import") (part "M01PTH_SMD_3.25X0.85MM_NO_SILK"))
    )
    (comp (ref "JP961")
      (value "M01PTH_SMD_3.25X0.85MM_NO_SILK")
      (footprint "eagle-import:1X01_SMD_3.25X0.85MM_NO_SILK")
      (libsource (lib "eagle-import") (part "M01PTH_SMD_3.25X0.85MM_NO_SILK"))
    )
    (comp (ref "JP962")
      (value "M01PTH_SMD_3.25X0.85MM_NO_SILK")
      (footprint "eagle-import:1X01_SMD_3.25X0.85MM_NO_SILK")
      (libsource (lib "eagle-import") (part "M01PTH_SMD_3.25X0.85MM_NO_SILK"))
    )
    (comp (ref "JP963")
      (value "M01PTH_SMD_3.25X0.85MM_NO_SILK")
      (footprint "eagle-import:1X01_SMD_3.25X0.85MM_NO_SILK")
      (libsource (lib "eagle-import") (part "M01PTH_SMD_3.25X0.85MM_NO_SILK"))
    )
    (comp (ref "JP964")
      (value "M01PTH_SMD_3.25X0.85MM_NO_SILK")
      (footprint "eagle-import:1X01_SMD_3.25X0.85MM_NO_SILK")
      (libsource (lib "eagle-import") (part "M01PTH_SMD_3.25X0.85MM_NO_SILK"))
    )
    (comp (ref "JP965")
      (value "M01PTH_SMD_3.25X0.85MM_NO_SILK")
      (footprint "eagle-import:1X01_SMD_3.25X0.85MM_NO_SILK")
      (libsource (lib "eagle-import") (part "M01PTH_SMD_3.25X0.85MM_NO_SILK"))
    )
    (comp (ref "JP966")
      (value "M01PTH_SMD_3.25X0.85MM_NO_SILK")
      (footprint "eagle-import:1X01_SMD_3.25X0.85MM_NO_SILK")
      (libsource (lib "eagle-import") (part "M01PTH_SMD_3.25X0.85MM_NO_SILK"))
    )
    (comp (ref "JP967")
      (value "M01PTH_SMD_3.25X0.85MM_NO_SILK")
      (footprint "eagle-import:1X01_SMD_3.25X0.85MM_NO_SILK")
      (libsource (lib "eagle-import") (part "M01PTH_SMD_3.25X0.85MM_NO_SILK"))
    )
    (comp (ref "JP968")
      (value "M01PTH_SMD_3.25X0.85MM_NO_SILK")
      (footprint "eagle-import:1X01_SMD_3.25X0.85MM_NO_SILK")
      (libsource (lib "eagle-import") (part "M01PTH_SMD_3.25X0.85MM_NO_SILK"))
    )
    (comp (ref "JP969")
      (value "M01PTH_SMD_3.25X0.85MM_NO_SILK")
      (footprint "eagle-import:1X01_SMD_3.25X0.85MM_NO_SILK")
      (libsource (lib "eagle-import") (part "M01PTH_SMD_3.25X0.85MM_NO_SILK"))
    )
    (comp (ref "JP970")
      (value "M01PTH_SMD_3.25X0.85MM_NO_SILK")
      (footprint "eagle-import:1X01_SMD_3.25X0.85MM_NO_SILK")
      (libsource (lib "eagle-import") (part "M01PTH_SMD_3.25X0.85MM_NO_SILK"))
    )
    (comp (ref "JP971")
      (value "M01PTH_SMD_3.25X0.85MM_NO_SILK")
      (footprint "eagle-import:1X01_SMD_3.25X0.85MM_NO_SILK")
      (libsource (lib "eagle-import") (part "M01PTH_SMD_3.25X0.85MM_NO_SILK"))
    )
    (comp (ref "JP972")
      (value "M01PTH_SMD_3.25X0.85MM_NO_SILK")
      (footprint "eagle-import:1X01_SMD_3.25X0.85MM_NO_SILK")
      (libsource (lib "eagle-import") (part "M01PTH_SMD_3.25X0.85MM_NO_SILK"))
    )
    (comp (ref "JP973")
      (value "M01PTH_SMD_3.25X0.85MM_NO_SILK")
      (footprint "eagle-import:1X01_SMD_3.25X0.85MM_NO_SILK")
      (libsource (lib "eagle-import") (part "M01PTH_SMD_3.25X0.85MM_NO_SILK"))
    )
    (comp (ref "JP974")
      (value "M01PTH_SMD_3.25X0.85MM_NO_SILK")
      (footprint "eagle-import:1X01_SMD_3.25X0.85MM_NO_SILK")
      (libsource (lib "eagle-import") (part "M01PTH_SMD_3.25X0.85MM_NO_SILK"))
    )
    (comp (ref "JP975")
      (value "M01PTH_SMD_3.25X0.85MM_NO_SILK")
      (footprint "eagle-import:1X01_SMD_3.25X0.85MM_NO_SILK")
      (libsource (lib "eagle-import") (part "M01PTH_SMD_3.25X0.85MM_NO_SILK"))
    )
    (comp (ref "JP976")
      (value "M01PTH_SMD_3.25X0.85MM_NO_SILK")
      (footprint "eagle-import:1X01_SMD_3.25X0.85MM_NO_SILK")
      (libsource (lib "eagle-import") (part "M01PTH_SMD_3.25X0.85MM_NO_SILK"))
    )
    (comp (ref "JP977")
      (value "M01PTH_SMD_3.25X0.85MM_NO_SILK")
      (footprint "eagle-import:1X01_SMD_3.25X0.85MM_NO_SILK")
      (libsource (lib "eagle-import") (part "M01PTH_SMD_3.25X0.85MM_NO_SILK"))
    )
    (comp (ref "JP978")
      (value "M01PTH_SMD_3.25X0.85MM_NO_SILK")
      (footprint "eagle-import:1X01_SMD_3.25X0.85MM_NO_SILK")
      (libsource (lib "eagle-import") (part "M01PTH_SMD_3.25X0.85MM_NO_SILK"))
    )
    (comp (ref "JP979")
      (value "M01PTH_SMD_3.25X0.85MM_NO_SILK")
      (footprint "eagle-import:1X01_SMD_3.25X0.85MM_NO_SILK")
      (libsource (lib "eagle-import") (part "M01PTH_SMD_3.25X0.85MM_NO_SILK"))
    )
    (comp (ref "JP980")
      (value "M01PTH_SMD_3.25X0.85MM_NO_SILK")
      (footprint "eagle-import:1X01_SMD_3.25X0.85MM_NO_SILK")
      (libsource (lib "eagle-import") (part "M01PTH_SMD_3.25X0.85MM_NO_SILK"))
    )
    (comp (ref "JP981")
      (value "M01PTH_SMD_3.25X0.85MM_NO_SILK")
      (footprint "eagle-import:1X01_SMD_3.25X0.85MM_NO_SILK")
      (libsource (lib "eagle-import") (part "M01PTH_SMD_3.25X0.85MM_NO_SILK"))
    )
    (comp (ref "JP982")
      (value "M01PTH_SMD_3.25X0.85MM_NO_SILK")
      (footprint "eagle-import:1X01_SMD_3.25X0.85MM_NO_SILK")
      (libsource (lib "eagle-import") (part "M01PTH_SMD_3.25X0.85MM_NO_SILK"))
    )
    (comp (ref "JP983")
      (value "M01PTH_SMD_3.25X0.85MM_NO_SILK")
      (footprint "eagle-import:1X01_SMD_3.25X0.85MM_NO_SILK")
      (libsource (lib "eagle-import") (part "M01PTH_SMD_3.25X0.85MM_NO_SILK"))
    )
    (comp (ref "JP984")
      (value "M01PTH_SMD_3.25X0.85MM_NO_SILK")
      (footprint "eagle-import:1X01_SMD_3.25X0.85MM_NO_SILK")
      (libsource (lib "eagle-import") (part "M01PTH_SMD_3.25X0.85MM_NO_SILK"))
    )
    (comp (ref "JP985")
      (value "M01PTH_SMD_3.25X0.85MM_NO_SILK")
      (footprint "eagle-import:1X01_SMD_3.25X0.85MM_NO_SILK")
      (libsource (lib "eagle-import") (part "M01PTH_SMD_3.25X0.85MM_NO_SILK"))
    )
    (comp (ref "JP986")
      (value "M01PTH_SMD_3.25X0.85MM_NO_SILK")
      (footprint "eagle-import:1X01_SMD_3.25X0.85MM_NO_SILK")
      (libsource (lib "eagle-import") (part "M01PTH_SMD_3.25X0.85MM_NO_SILK"))
    )
    (comp (ref "JP987")
      (value "M01PTH_SMD_3.25X0.85MM_NO_SILK")
      (footprint "eagle-import:1X01_SMD_3.25X0.85MM_NO_SILK")
      (libsource (lib "eagle-import") (part "M01PTH_SMD_3.25X0.85MM_NO_SILK"))
    )
    (comp (ref "JP988")
      (value "M01PTH_SMD_3.25X0.85MM_NO_SILK")
      (footprint "eagle-import:1X01_SMD_3.25X0.85MM_NO_SILK")
      (libsource (lib "eagle-import") (part "M01PTH_SMD_3.25X0.85MM_NO_SILK"))
    )
    (comp (ref "JP989")
      (value "M01PTH_SMD_3.25X0.85MM_NO_SILK")
      (footprint "eagle-import:1X01_SMD_3.25X0.85MM_NO_SILK")
      (libsource (lib "eagle-import") (part "M01PTH_SMD_3.25X0.85MM_NO_SILK"))
    )
    (comp (ref "JP990")
      (value "M01PTH_SMD_3.25X0.85MM_NO_SILK")
      (footprint "eagle-import:1X01_SMD_3.25X0.85MM_NO_SILK")
      (libsource (lib "eagle-import") (part "M01PTH_SMD_3.25X0.85MM_NO_SILK"))
    )
    (comp (ref "JP991")
      (value "M01PTH_SMD_3.25X0.85MM_NO_SILK")
      (footprint "eagle-import:1X01_SMD_3.25X0.85MM_NO_SILK")
      (libsource (lib "eagle-import") (part "M01PTH_SMD_3.25X0.85MM_NO_SILK"))
    )
    (comp (ref "JP992")
      (value "M01PTH_SMD_3.25X0.85MM_NO_SILK")
      (footprint "eagle-import:1X01_SMD_3.25X0.85MM_NO_SILK")
      (libsource (lib "eagle-import") (part "M01PTH_SMD_3.25X0.85MM_NO_SILK"))
    )
    (comp (ref "JP993")
      (value "M01PTH_SMD_3.25X0.85MM_NO_SILK")
      (footprint "eagle-import:1X01_SMD_3.25X0.85MM_NO_SILK")
      (libsource (lib "eagle-import") (part "M01PTH_SMD_3.25X0.85MM_NO_SILK"))
    )
    (comp (ref "JP994")
      (value "M01PTH_SMD_3.25X0.85MM_NO_SILK")
      (footprint "eagle-import:1X01_SMD_3.25X0.85MM_NO_SILK")
      (libsource (lib "eagle-import") (part "M01PTH_SMD_3.25X0.85MM_NO_SILK"))
    )
    (comp (ref "JP995")
      (value "M01PTH_SMD_3.25X0.85MM_NO_SILK")
      (footprint "eagle-import:1X01_SMD_3.25X0.85MM_NO_SILK")
      (libsource (lib "eagle-import") (part "M01PTH_SMD_3.25X0.85MM_NO_SILK"))
    )
    (comp (ref "JP996")
      (value "M01PTH_SMD_3.25X0.85MM_NO_SILK")
      (footprint "eagle-import:1X01_SMD_3.25X0.85MM_NO_SILK")
      (libsource (lib "eagle-import") (part "M01PTH_SMD_3.25X0.85MM_NO_SILK"))
    )
    (comp (ref "JP997")
      (value "M01PTH_SMD_3.25X0.85MM_NO_SILK")
      (footprint "eagle-import:1X01_SMD_3.25X0.85MM_NO_SILK")
      (libsource (lib "eagle-import") (part "M01PTH_SMD_3.25X0.85MM_NO_SILK"))
    )
    (comp (ref "JP998")
      (value "M01PTH_SMD_3.25X0.85MM_NO_SILK")
      (footprint "eagle-import:1X01_SMD_3.25X0.85MM_NO_SILK")
      (libsource (lib "eagle-import") (part "M01PTH_SMD_3.25X0.85MM_NO_SILK"))
    )
    (comp (ref "JP999")
      (value "M01PTH_SMD_3.25X0.85MM_NO_SILK")
      (footprint "eagle-import:1X01_SMD_3.25X0.85MM_NO_SILK")
      (libsource (lib "eagle-import") (part "M01PTH_SMD_3.25X0.85MM_NO_SILK"))
    )
    (comp (ref "JP1000")
      (value "M01PTH_SMD_3.25X0.85MM_NO_SILK")
      (footprint "eagle-import:1X01_SMD_3.25X0.85MM_NO_SILK")
      (libsource (lib "eagle-import") (part "M01PTH_SMD_3.25X0.85MM_NO_SILK"))
    )
    (comp (ref "JP1001")
      (value "M01PTH_SMD_3.25X0.85MM_NO_SILK")
      (footprint "eagle-import:1X01_SMD_3.25X0.85MM_NO_SILK")
      (libsource (lib "eagle-import") (part "M01PTH_SMD_3.25X0.85MM_NO_SILK"))
    )
    (comp (ref "JP1002")
      (value "M01PTH_SMD_3.25X0.85MM_NO_SILK")
      (footprint "eagle-import:1X01_SMD_3.25X0.85MM_NO_SILK")
      (libsource (lib "eagle-import") (part "M01PTH_SMD_3.25X0.85MM_NO_SILK"))
    )
    (comp (ref "JP1003")
      (value "M01PTH_SMD_3.25X0.85MM_NO_SILK")
      (footprint "eagle-import:1X01_SMD_3.25X0.85MM_NO_SILK")
      (libsource (lib "eagle-import") (part "M01PTH_SMD_3.25X0.85MM_NO_SILK"))
    )
    (comp (ref "JP1004")
      (value "M01PTH_SMD_3.25X0.85MM_NO_SILK")
      (footprint "eagle-import:1X01_SMD_3.25X0.85MM_NO_SILK")
      (libsource (lib "eagle-import") (part "M01PTH_SMD_3.25X0.85MM_NO_SILK"))
    )
    (comp (ref "JP1005")
      (value "M01PTH_SMD_3.25X0.85MM_NO_SILK")
      (footprint "eagle-import:1X01_SMD_3.25X0.85MM_NO_SILK")
      (libsource (lib "eagle-import") (part "M01PTH_SMD_3.25X0.85MM_NO_SILK"))
    )
    (comp (ref "JP1006")
      (value "M01PTH_SMD_3.25X0.85MM_NO_SILK")
      (footprint "eagle-import:1X01_SMD_3.25X0.85MM_NO_SILK")
      (libsource (lib "eagle-import") (part "M01PTH_SMD_3.25X0.85MM_NO_SILK"))
    )
    (comp (ref "JP1007")
      (value "M01PTH_SMD_3.25X0.85MM_NO_SILK")
      (footprint "eagle-import:1X01_SMD_3.25X0.85MM_NO_SILK")
      (libsource (lib "eagle-import") (part "M01PTH_SMD_3.25X0.85MM_NO_SILK"))
    )
    (comp (ref "JP1008")
      (value "M01PTH_SMD_3.25X0.85MM_NO_SILK")
      (footprint "eagle-import:1X01_SMD_3.25X0.85MM_NO_SILK")
      (libsource (lib "eagle-import") (part "M01PTH_SMD_3.25X0.85MM_NO_SILK"))
    )
    (comp (ref "JP1009")
      (value "M01PTH_SMD_3.25X0.85MM_NO_SILK")
      (footprint "eagle-import:1X01_SMD_3.25X0.85MM_NO_SILK")
      (libsource (lib "eagle-import") (part "M01PTH_SMD_3.25X0.85MM_NO_SILK"))
    )
    (comp (ref "JP1010")
      (value "M01PTH_SMD_3.25X0.85MM_NO_SILK")
      (footprint "eagle-import:1X01_SMD_3.25X0.85MM_NO_SILK")
      (libsource (lib "eagle-import") (part "M01PTH_SMD_3.25X0.85MM_NO_SILK"))
    )
    (comp (ref "JP1011")
      (value "M01PTH_SMD_3.25X0.85MM_NO_SILK")
      (footprint "eagle-import:1X01_SMD_3.25X0.85MM_NO_SILK")
      (libsource (lib "eagle-import") (part "M01PTH_SMD_3.25X0.85MM_NO_SILK"))
    )
    (comp (ref "JP1012")
      (value "M01PTH_SMD_3.25X0.85MM_NO_SILK")
      (footprint "eagle-import:1X01_SMD_3.25X0.85MM_NO_SILK")
      (libsource (lib "eagle-import") (part "M01PTH_SMD_3.25X0.85MM_NO_SILK"))
    )
    (comp (ref "JP1013")
      (value "M01PTH_SMD_3.25X0.85MM_NO_SILK")
      (footprint "eagle-import:1X01_SMD_3.25X0.85MM_NO_SILK")
      (libsource (lib "eagle-import") (part "M01PTH_SMD_3.25X0.85MM_NO_SILK"))
    )
    (comp (ref "JP1014")
      (value "M01PTH_SMD_3.25X0.85MM_NO_SILK")
      (footprint "eagle-import:1X01_SMD_3.25X0.85MM_NO_SILK")
      (libsource (lib "eagle-import") (part "M01PTH_SMD_3.25X0.85MM_NO_SILK"))
    )
    (comp (ref "JP1015")
      (value "M01PTH_SMD_3.25X0.85MM_NO_SILK")
      (footprint "eagle-import:1X01_SMD_3.25X0.85MM_NO_SILK")
      (libsource (lib "eagle-import") (part "M01PTH_SMD_3.25X0.85MM_NO_SILK"))
    )
    (comp (ref "JP1016")
      (value "M01PTH_SMD_3.25X0.85MM_NO_SILK")
      (footprint "eagle-import:1X01_SMD_3.25X0.85MM_NO_SILK")
      (libsource (lib "eagle-import") (part "M01PTH_SMD_3.25X0.85MM_NO_SILK"))
    )
    (comp (ref "JP1017")
      (value "M01PTH_SMD_3.25X0.85MM_NO_SILK")
      (footprint "eagle-import:1X01_SMD_3.25X0.85MM_NO_SILK")
      (libsource (lib "eagle-import") (part "M01PTH_SMD_3.25X0.85MM_NO_SILK"))
    )
    (comp (ref "JP1018")
      (value "M01PTH_SMD_3.25X0.85MM_NO_SILK")
      (footprint "eagle-import:1X01_SMD_3.25X0.85MM_NO_SILK")
      (libsource (lib "eagle-import") (part "M01PTH_SMD_3.25X0.85MM_NO_SILK"))
    )
    (comp (ref "JP1019")
      (value "M01PTH_SMD_3.25X0.85MM_NO_SILK")
      (footprint "eagle-import:1X01_SMD_3.25X0.85MM_NO_SILK")
      (libsource (lib "eagle-import") (part "M01PTH_SMD_3.25X0.85MM_NO_SILK"))
    )
    (comp (ref "JP1020")
      (value "M01PTH_SMD_3.25X0.85MM_NO_SILK")
      (footprint "eagle-import:1X01_SMD_3.25X0.85MM_NO_SILK")
      (libsource (lib "eagle-import") (part "M01PTH_SMD_3.25X0.85MM_NO_SILK"))
    )
    (comp (ref "JP1021")
      (value "M01PTH_SMD_3.25X0.85MM_NO_SILK")
      (footprint "eagle-import:1X01_SMD_3.25X0.85MM_NO_SILK")
      (libsource (lib "eagle-import") (part "M01PTH_SMD_3.25X0.85MM_NO_SILK"))
    )
    (comp (ref "JP1022")
      (value "M01PTH_SMD_3.25X0.85MM_NO_SILK")
      (footprint "eagle-import:1X01_SMD_3.25X0.85MM_NO_SILK")
      (libsource (lib "eagle-import") (part "M01PTH_SMD_3.25X0.85MM_NO_SILK"))
    )
    (comp (ref "JP1023")
      (value "M01PTH_SMD_3.25X0.85MM_NO_SILK")
      (footprint "eagle-import:1X01_SMD_3.25X0.85MM_NO_SILK")
      (libsource (lib "eagle-import") (part "M01PTH_SMD_3.25X0.85MM_NO_SILK"))
    )
    (comp (ref "JP1024")
      (value "M01PTH_SMD_3.25X0.85MM_NO_SILK")
      (footprint "eagle-import:1X01_SMD_3.25X0.85MM_NO_SILK")
      (libsource (lib "eagle-import") (part "M01PTH_SMD_3.25X0.85MM_NO_SILK"))
    )
    (comp (ref "JP1025")
      (value "M01PTH_SMD_3.25X0.85MM_NO_SILK")
      (footprint "eagle-import:1X01_SMD_3.25X0.85MM_NO_SILK")
      (libsource (lib "eagle-import") (part "M01PTH_SMD_3.25X0.85MM_NO_SILK"))
    )
    (comp (ref "JP1026")
      (value "M01PTH_SMD_3.25X0.85MM_NO_SILK")
      (footprint "eagle-import:1X01_SMD_3.25X0.85MM_NO_SILK")
      (libsource (lib "eagle-import") (part "M01PTH_SMD_3.25X0.85MM_NO_SILK"))
    )
    (comp (ref "JP1027")
      (value "M01PTH_SMD_3.25X0.85MM_NO_SILK")
      (footprint "eagle-import:1X01_SMD_3.25X0.85MM_NO_SILK")
      (libsource (lib "eagle-import") (part "M01PTH_SMD_3.25X0.85MM_NO_SILK"))
    )
    (comp (ref "JP1028")
      (value "M01PTH_SMD_3.25X0.85MM_NO_SILK")
      (footprint "eagle-import:1X01_SMD_3.25X0.85MM_NO_SILK")
      (libsource (lib "eagle-import") (part "M01PTH_SMD_3.25X0.85MM_NO_SILK"))
    )
    (comp (ref "JP1029")
      (value "M01PTH_SMD_3.25X0.85MM_NO_SILK")
      (footprint "eagle-import:1X01_SMD_3.25X0.85MM_NO_SILK")
      (libsource (lib "eagle-import") (part "M01PTH_SMD_3.25X0.85MM_NO_SILK"))
    )
    (comp (ref "JP1030")
      (value "M01PTH_SMD_3.25X0.85MM_NO_SILK")
      (footprint "eagle-import:1X01_SMD_3.25X0.85MM_NO_SILK")
      (libsource (lib "eagle-import") (part "M01PTH_SMD_3.25X0.85MM_NO_SILK"))
    )
    (comp (ref "JP1031")
      (value "M01PTH_SMD_3.25X0.85MM_NO_SILK")
      (footprint "eagle-import:1X01_SMD_3.25X0.85MM_NO_SILK")
      (libsource (lib "eagle-import") (part "M01PTH_SMD_3.25X0.85MM_NO_SILK"))
    )
    (comp (ref "JP1032")
      (value "M01PTH_SMD_3.25X0.85MM_NO_SILK")
      (footprint "eagle-import:1X01_SMD_3.25X0.85MM_NO_SILK")
      (libsource (lib "eagle-import") (part "M01PTH_SMD_3.25X0.85MM_NO_SILK"))
    )
    (comp (ref "JP1033")
      (value "M01PTH_SMD_3.25X0.85MM_NO_SILK")
      (footprint "eagle-import:1X01_SMD_3.25X0.85MM_NO_SILK")
      (libsource (lib "eagle-import") (part "M01PTH_SMD_3.25X0.85MM_NO_SILK"))
    )
    (comp (ref "JP1034")
      (value "M01PTH_SMD_3.25X0.85MM_NO_SILK")
      (footprint "eagle-import:1X01_SMD_3.25X0.85MM_NO_SILK")
      (libsource (lib "eagle-import") (part "M01PTH_SMD_3.25X0.85MM_NO_SILK"))
    )
    (comp (ref "JP1035")
      (value "M01PTH_SMD_3.25X0.85MM_NO_SILK")
      (footprint "eagle-import:1X01_SMD_3.25X0.85MM_NO_SILK")
      (libsource (lib "eagle-import") (part "M01PTH_SMD_3.25X0.85MM_NO_SILK"))
    )
    (comp (ref "JP1036")
      (value "M01PTH_SMD_3.25X0.85MM_NO_SILK")
      (footprint "eagle-import:1X01_SMD_3.25X0.85MM_NO_SILK")
      (libsource (lib "eagle-import") (part "M01PTH_SMD_3.25X0.85MM_NO_SILK"))
    )
    (comp (ref "JP1037")
      (value "M01PTH_SMD_3.25X0.85MM_NO_SILK")
      (footprint "eagle-import:1X01_SMD_3.25X0.85MM_NO_SILK")
      (libsource (lib "eagle-import") (part "M01PTH_SMD_3.25X0.85MM_NO_SILK"))
    )
    (comp (ref "JP1038")
      (value "M01PTH_SMD_3.25X0.85MM_NO_SILK")
      (footprint "eagle-import:1X01_SMD_3.25X0.85MM_NO_SILK")
      (libsource (lib "eagle-import") (part "M01PTH_SMD_3.25X0.85MM_NO_SILK"))
    )
    (comp (ref "JP1039")
      (value "M01PTH_SMD_3.25X0.85MM_NO_SILK")
      (footprint "eagle-import:1X01_SMD_3.25X0.85MM_NO_SILK")
      (libsource (lib "eagle-import") (part "M01PTH_SMD_3.25X0.85MM_NO_SILK"))
    )
    (comp (ref "JP1040")
      (value "M01PTH_SMD_3.25X0.85MM_NO_SILK")
      (footprint "eagle-import:1X01_SMD_3.25X0.85MM_NO_SILK")
      (libsource (lib "eagle-import") (part "M01PTH_SMD_3.25X0.85MM_NO_SILK"))
    )
    (comp (ref "JP1041")
      (value "M01PTH_SMD_3.25X0.85MM_NO_SILK")
      (footprint "eagle-import:1X01_SMD_3.25X0.85MM_NO_SILK")
      (libsource (lib "eagle-import") (part "M01PTH_SMD_3.25X0.85MM_NO_SILK"))
    )
    (comp (ref "JP1042")
      (value "M01PTH_SMD_3.25X0.85MM_NO_SILK")
      (footprint "eagle-import:1X01_SMD_3.25X0.85MM_NO_SILK")
      (libsource (lib "eagle-import") (part "M01PTH_SMD_3.25X0.85MM_NO_SILK"))
    )
    (comp (ref "JP1043")
      (value "M01PTH_SMD_3.25X0.85MM_NO_SILK")
      (footprint "eagle-import:1X01_SMD_3.25X0.85MM_NO_SILK")
      (libsource (lib "eagle-import") (part "M01PTH_SMD_3.25X0.85MM_NO_SILK"))
    )
    (comp (ref "JP1044")
      (value "M01PTH_SMD_3.25X0.85MM_NO_SILK")
      (footprint "eagle-import:1X01_SMD_3.25X0.85MM_NO_SILK")
      (libsource (lib "eagle-import") (part "M01PTH_SMD_3.25X0.85MM_NO_SILK"))
    )
    (comp (ref "JP1045")
      (value "M01PTH_SMD_3.25X0.85MM_NO_SILK")
      (footprint "eagle-import:1X01_SMD_3.25X0.85MM_NO_SILK")
      (libsource (lib "eagle-import") (part "M01PTH_SMD_3.25X0.85MM_NO_SILK"))
    )
    (comp (ref "JP1046")
      (value "M01PTH_SMD_3.25X0.85MM_NO_SILK")
      (footprint "eagle-import:1X01_SMD_3.25X0.85MM_NO_SILK")
      (libsource (lib "eagle-import") (part "M01PTH_SMD_3.25X0.85MM_NO_SILK"))
    )
    (comp (ref "JP1047")
      (value "M01PTH_SMD_3.25X0.85MM_NO_SILK")
      (footprint "eagle-import:1X01_SMD_3.25X0.85MM_NO_SILK")
      (libsource (lib "eagle-import") (part "M01PTH_SMD_3.25X0.85MM_NO_SILK"))
    )
    (comp (ref "JP1048")
      (value "M01PTH_SMD_3.25X0.85MM_NO_SILK")
      (footprint "eagle-import:1X01_SMD_3.25X0.85MM_NO_SILK")
      (libsource (lib "eagle-import") (part "M01PTH_SMD_3.25X0.85MM_NO_SILK"))
    )
    (comp (ref "JP1049")
      (value "M01PTH_SMD_3.25X0.85MM_NO_SILK")
      (footprint "eagle-import:1X01_SMD_3.25X0.85MM_NO_SILK")
      (libsource (lib "eagle-import") (part "M01PTH_SMD_3.25X0.85MM_NO_SILK"))
    )
    (comp (ref "JP1050")
      (value "M01PTH_SMD_3.25X0.85MM_NO_SILK")
      (footprint "eagle-import:1X01_SMD_3.25X0.85MM_NO_SILK")
      (libsource (lib "eagle-import") (part "M01PTH_SMD_3.25X0.85MM_NO_SILK"))
    )
    (comp (ref "JP1051")
      (value "M01PTH_SMD_3.25X0.85MM_NO_SILK")
      (footprint "eagle-import:1X01_SMD_3.25X0.85MM_NO_SILK")
      (libsource (lib "eagle-import") (part "M01PTH_SMD_3.25X0.85MM_NO_SILK"))
    )
    (comp (ref "JP1052")
      (value "M01PTH_SMD_3.25X0.85MM_NO_SILK")
      (footprint "eagle-import:1X01_SMD_3.25X0.85MM_NO_SILK")
      (libsource (lib "eagle-import") (part "M01PTH_SMD_3.25X0.85MM_NO_SILK"))
    )
    (comp (ref "JP1053")
      (value "M01PTH_SMD_3.25X0.85MM_NO_SILK")
      (footprint "eagle-import:1X01_SMD_3.25X0.85MM_NO_SILK")
      (libsource (lib "eagle-import") (part "M01PTH_SMD_3.25X0.85MM_NO_SILK"))
    )
    (comp (ref "JP1054")
      (value "M01PTH_SMD_3.25X0.85MM_NO_SILK")
      (footprint "eagle-import:1X01_SMD_3.25X0.85MM_NO_SILK")
      (libsource (lib "eagle-import") (part "M01PTH_SMD_3.25X0.85MM_NO_SILK"))
    )
    (comp (ref "JP1055")
      (value "M01PTH_SMD_3.25X0.85MM_NO_SILK")
      (footprint "eagle-import:1X01_SMD_3.25X0.85MM_NO_SILK")
      (libsource (lib "eagle-import") (part "M01PTH_SMD_3.25X0.85MM_NO_SILK"))
    )
    (comp (ref "JP1056")
      (value "M01PTH_SMD_3.25X0.85MM_NO_SILK")
      (footprint "eagle-import:1X01_SMD_3.25X0.85MM_NO_SILK")
      (libsource (lib "eagle-import") (part "M01PTH_SMD_3.25X0.85MM_NO_SILK"))
    )
    (comp (ref "JP1057")
      (value "M01PTH_SMD_3.25X0.85MM_NO_SILK")
      (footprint "eagle-import:1X01_SMD_3.25X0.85MM_NO_SILK")
      (libsource (lib "eagle-import") (part "M01PTH_SMD_3.25X0.85MM_NO_SILK"))
    )
    (comp (ref "JP1058")
      (value "M01PTH_SMD_3.25X0.85MM_NO_SILK")
      (footprint "eagle-import:1X01_SMD_3.25X0.85MM_NO_SILK")
      (libsource (lib "eagle-import") (part "M01PTH_SMD_3.25X0.85MM_NO_SILK"))
    )
    (comp (ref "JP1059")
      (value "M01PTH_SMD_3.25X0.85MM_NO_SILK")
      (footprint "eagle-import:1X01_SMD_3.25X0.85MM_NO_SILK")
      (libsource (lib "eagle-import") (part "M01PTH_SMD_3.25X0.85MM_NO_SILK"))
    )
    (comp (ref "JP1060")
      (value "M01PTH_SMD_3.25X0.85MM_NO_SILK")
      (footprint "eagle-import:1X01_SMD_3.25X0.85MM_NO_SILK")
      (libsource (lib "eagle-import") (part "M01PTH_SMD_3.25X0.85MM_NO_SILK"))
    )
    (comp (ref "JP1061")
      (value "M01PTH_SMD_3.25X0.85MM_NO_SILK")
      (footprint "eagle-import:1X01_SMD_3.25X0.85MM_NO_SILK")
      (libsource (lib "eagle-import") (part "M01PTH_SMD_3.25X0.85MM_NO_SILK"))
    )
    (comp (ref "JP1062")
      (value "M01PTH_SMD_3.25X0.85MM_NO_SILK")
      (footprint "eagle-import:1X01_SMD_3.25X0.85MM_NO_SILK")
      (libsource (lib "eagle-import") (part "M01PTH_SMD_3.25X0.85MM_NO_SILK"))
    )
    (comp (ref "JP1063")
      (value "M01PTH_SMD_3.25X0.85MM_NO_SILK")
      (footprint "eagle-import:1X01_SMD_3.25X0.85MM_NO_SILK")
      (libsource (lib "eagle-import") (part "M01PTH_SMD_3.25X0.85MM_NO_SILK"))
    )
    (comp (ref "JP1064")
      (value "M01PTH_SMD_3.25X0.85MM_NO_SILK")
      (footprint "eagle-import:1X01_SMD_3.25X0.85MM_NO_SILK")
      (libsource (lib "eagle-import") (part "M01PTH_SMD_3.25X0.85MM_NO_SILK"))
    )
    (comp (ref "JP1065")
      (value "M01PTH_SMD_3.25X0.85MM_NO_SILK")
      (footprint "eagle-import:1X01_SMD_3.25X0.85MM_NO_SILK")
      (libsource (lib "eagle-import") (part "M01PTH_SMD_3.25X0.85MM_NO_SILK"))
    )
    (comp (ref "JP1066")
      (value "M01PTH_SMD_3.25X0.85MM_NO_SILK")
      (footprint "eagle-import:1X01_SMD_3.25X0.85MM_NO_SILK")
      (libsource (lib "eagle-import") (part "M01PTH_SMD_3.25X0.85MM_NO_SILK"))
    )
    (comp (ref "JP1067")
      (value "M01PTH_SMD_3.25X0.85MM_NO_SILK")
      (footprint "eagle-import:1X01_SMD_3.25X0.85MM_NO_SILK")
      (libsource (lib "eagle-import") (part "M01PTH_SMD_3.25X0.85MM_NO_SILK"))
    )
    (comp (ref "JP1068")
      (value "M01PTH_SMD_3.25X0.85MM_NO_SILK")
      (footprint "eagle-import:1X01_SMD_3.25X0.85MM_NO_SILK")
      (libsource (lib "eagle-import") (part "M01PTH_SMD_3.25X0.85MM_NO_SILK"))
    )
    (comp (ref "JP1069")
      (value "M01PTH_SMD_3.25X0.85MM_NO_SILK")
      (footprint "eagle-import:1X01_SMD_3.25X0.85MM_NO_SILK")
      (libsource (lib "eagle-import") (part "M01PTH_SMD_3.25X0.85MM_NO_SILK"))
    )
    (comp (ref "JP1070")
      (value "M01PTH_SMD_3.25X0.85MM_NO_SILK")
      (footprint "eagle-import:1X01_SMD_3.25X0.85MM_NO_SILK")
      (libsource (lib "eagle-import") (part "M01PTH_SMD_3.25X0.85MM_NO_SILK"))
    )
    (comp (ref "JP1071")
      (value "M01PTH_SMD_3.25X0.85MM_NO_SILK")
      (footprint "eagle-import:1X01_SMD_3.25X0.85MM_NO_SILK")
      (libsource (lib "eagle-import") (part "M01PTH_SMD_3.25X0.85MM_NO_SILK"))
    )
    (comp (ref "JP1072")
      (value "M01PTH_SMD_3.25X0.85MM_NO_SILK")
      (footprint "eagle-import:1X01_SMD_3.25X0.85MM_NO_SILK")
      (libsource (lib "eagle-import") (part "M01PTH_SMD_3.25X0.85MM_NO_SILK"))
    )
    (comp (ref "JP1073")
      (value "M01PTH_SMD_3.25X0.85MM_NO_SILK")
      (footprint "eagle-import:1X01_SMD_3.25X0.85MM_NO_SILK")
      (libsource (lib "eagle-import") (part "M01PTH_SMD_3.25X0.85MM_NO_SILK"))
    )
    (comp (ref "JP1074")
      (value "M01PTH_SMD_3.25X0.85MM_NO_SILK")
      (footprint "eagle-import:1X01_SMD_3.25X0.85MM_NO_SILK")
      (libsource (lib "eagle-import") (part "M01PTH_SMD_3.25X0.85MM_NO_SILK"))
    )
    (comp (ref "JP1075")
      (value "M01PTH_SMD_3.25X0.85MM_NO_SILK")
      (footprint "eagle-import:1X01_SMD_3.25X0.85MM_NO_SILK")
      (libsource (lib "eagle-import") (part "M01PTH_SMD_3.25X0.85MM_NO_SILK"))
    )
    (comp (ref "JP1076")
      (value "M01PTH_SMD_3.25X0.85MM_NO_SILK")
      (footprint "eagle-import:1X01_SMD_3.25X0.85MM_NO_SILK")
      (libsource (lib "eagle-import") (part "M01PTH_SMD_3.25X0.85MM_NO_SILK"))
    )
    (comp (ref "JP1077")
      (value "M01PTH_SMD_3.25X0.85MM_NO_SILK")
      (footprint "eagle-import:1X01_SMD_3.25X0.85MM_NO_SILK")
      (libsource (lib "eagle-import") (part "M01PTH_SMD_3.25X0.85MM_NO_SILK"))
    )
    (comp (ref "JP1078")
      (value "M01PTH_SMD_3.25X0.85MM_NO_SILK")
      (footprint "eagle-import:1X01_SMD_3.25X0.85MM_NO_SILK")
      (libsource (lib "eagle-import") (part "M01PTH_SMD_3.25X0.85MM_NO_SILK"))
    )
    (comp (ref "JP1079")
      (value "M01PTH_SMD_3.25X0.85MM_NO_SILK")
      (footprint "eagle-import:1X01_SMD_3.25X0.85MM_NO_SILK")
      (libsource (lib "eagle-import") (part "M01PTH_SMD_3.25X0.85MM_NO_SILK"))
    )
    (comp (ref "JP1080")
      (value "M01PTH_SMD_3.25X0.85MM_NO_SILK")
      (footprint "eagle-import:1X01_SMD_3.25X0.85MM_NO_SILK")
      (libsource (lib "eagle-import") (part "M01PTH_SMD_3.25X0.85MM_NO_SILK"))
    )
    (comp (ref "JP1081")
      (value "M01PTH_SMD_3.25X0.85MM_NO_SILK")
      (footprint "eagle-import:1X01_SMD_3.25X0.85MM_NO_SILK")
      (libsource (lib "eagle-import") (part "M01PTH_SMD_3.25X0.85MM_NO_SILK"))
    )
    (comp (ref "JP1082")
      (value "M01PTH_SMD_3.25X0.85MM_NO_SILK")
      (footprint "eagle-import:1X01_SMD_3.25X0.85MM_NO_SILK")
      (libsource (lib "eagle-import") (part "M01PTH_SMD_3.25X0.85MM_NO_SILK"))
    )
    (comp (ref "JP1083")
      (value "M01PTH_SMD_3.25X0.85MM_NO_SILK")
      (footprint "eagle-import:1X01_SMD_3.25X0.85MM_NO_SILK")
      (libsource (lib "eagle-import") (part "M01PTH_SMD_3.25X0.85MM_NO_SILK"))
    )
    (comp (ref "JP1084")
      (value "M01PTH_SMD_3.25X0.85MM_NO_SILK")
      (footprint "eagle-import:1X01_SMD_3.25X0.85MM_NO_SILK")
      (libsource (lib "eagle-import") (part "M01PTH_SMD_3.25X0.85MM_NO_SILK"))
    )
    (comp (ref "JP1085")
      (value "M01PTH_SMD_3.25X0.85MM_NO_SILK")
      (footprint "eagle-import:1X01_SMD_3.25X0.85MM_NO_SILK")
      (libsource (lib "eagle-import") (part "M01PTH_SMD_3.25X0.85MM_NO_SILK"))
    )
    (comp (ref "JP1086")
      (value "M01PTH_SMD_3.25X0.85MM_NO_SILK")
      (footprint "eagle-import:1X01_SMD_3.25X0.85MM_NO_SILK")
      (libsource (lib "eagle-import") (part "M01PTH_SMD_3.25X0.85MM_NO_SILK"))
    )
    (comp (ref "JP1087")
      (value "M01PTH_SMD_3.25X0.85MM_NO_SILK")
      (footprint "eagle-import:1X01_SMD_3.25X0.85MM_NO_SILK")
      (libsource (lib "eagle-import") (part "M01PTH_SMD_3.25X0.85MM_NO_SILK"))
    )
    (comp (ref "JP1088")
      (value "M01PTH_SMD_3.25X0.85MM_NO_SILK")
      (footprint "eagle-import:1X01_SMD_3.25X0.85MM_NO_SILK")
      (libsource (lib "eagle-import") (part "M01PTH_SMD_3.25X0.85MM_NO_SILK"))
    )
    (comp (ref "JP1089")
      (value "M01PTH_SMD_3.25X0.85MM_NO_SILK")
      (footprint "eagle-import:1X01_SMD_3.25X0.85MM_NO_SILK")
      (libsource (lib "eagle-import") (part "M01PTH_SMD_3.25X0.85MM_NO_SILK"))
    )
    (comp (ref "JP1090")
      (value "M01PTH_SMD_3.25X0.85MM_NO_SILK")
      (footprint "eagle-import:1X01_SMD_3.25X0.85MM_NO_SILK")
      (libsource (lib "eagle-import") (part "M01PTH_SMD_3.25X0.85MM_NO_SILK"))
    )
    (comp (ref "JP1091")
      (value "M01PTH_SMD_3.25X0.85MM_NO_SILK")
      (footprint "eagle-import:1X01_SMD_3.25X0.85MM_NO_SILK")
      (libsource (lib "eagle-import") (part "M01PTH_SMD_3.25X0.85MM_NO_SILK"))
    )
    (comp (ref "JP1092")
      (value "M01PTH_SMD_3.25X0.85MM_NO_SILK")
      (footprint "eagle-import:1X01_SMD_3.25X0.85MM_NO_SILK")
      (libsource (lib "eagle-import") (part "M01PTH_SMD_3.25X0.85MM_NO_SILK"))
    )
    (comp (ref "JP1093")
      (value "M01PTH_SMD_3.25X0.85MM_NO_SILK")
      (footprint "eagle-import:1X01_SMD_3.25X0.85MM_NO_SILK")
      (libsource (lib "eagle-import") (part "M01PTH_SMD_3.25X0.85MM_NO_SILK"))
    )
    (comp (ref "JP1094")
      (value "M01PTH_SMD_3.25X0.85MM_NO_SILK")
      (footprint "eagle-import:1X01_SMD_3.25X0.85MM_NO_SILK")
      (libsource (lib "eagle-import") (part "M01PTH_SMD_3.25X0.85MM_NO_SILK"))
    )
    (comp (ref "JP1095")
      (value "M01PTH_SMD_3.25X0.85MM_NO_SILK")
      (footprint "eagle-import:1X01_SMD_3.25X0.85MM_NO_SILK")
      (libsource (lib "eagle-import") (part "M01PTH_SMD_3.25X0.85MM_NO_SILK"))
    )
    (comp (ref "JP1096")
      (value "M01PTH_SMD_3.25X0.85MM_NO_SILK")
      (footprint "eagle-import:1X01_SMD_3.25X0.85MM_NO_SILK")
      (libsource (lib "eagle-import") (part "M01PTH_SMD_3.25X0.85MM_NO_SILK"))
    )
    (comp (ref "JP1097")
      (value "M01PTH_SMD_3.25X0.85MM_NO_SILK")
      (footprint "eagle-import:1X01_SMD_3.25X0.85MM_NO_SILK")
      (libsource (lib "eagle-import") (part "M01PTH_SMD_3.25X0.85MM_NO_SILK"))
    )
    (comp (ref "JP1098")
      (value "M01PTH_SMD_3.25X0.85MM_NO_SILK")
      (footprint "eagle-import:1X01_SMD_3.25X0.85MM_NO_SILK")
      (libsource (lib "eagle-import") (part "M01PTH_SMD_3.25X0.85MM_NO_SILK"))
    )
    (comp (ref "JP1099")
      (value "M01PTH_SMD_3.25X0.85MM_NO_SILK")
      (footprint "eagle-import:1X01_SMD_3.25X0.85MM_NO_SILK")
      (libsource (lib "eagle-import") (part "M01PTH_SMD_3.25X0.85MM_NO_SILK"))
    )
    (comp (ref "JP1100")
      (value "M01PTH_SMD_3.25X0.85MM_NO_SILK")
      (footprint "eagle-import:1X01_SMD_3.25X0.85MM_NO_SILK")
      (libsource (lib "eagle-import") (part "M01PTH_SMD_3.25X0.85MM_NO_SILK"))
    )
    (comp (ref "JP1101")
      (value "M01PTH_SMD_3.25X0.85MM_NO_SILK")
      (footprint "eagle-import:1X01_SMD_3.25X0.85MM_NO_SILK")
      (libsource (lib "eagle-import") (part "M01PTH_SMD_3.25X0.85MM_NO_SILK"))
    )
    (comp (ref "JP1102")
      (value "M01PTH_SMD_3.25X0.85MM_NO_SILK")
      (footprint "eagle-import:1X01_SMD_3.25X0.85MM_NO_SILK")
      (libsource (lib "eagle-import") (part "M01PTH_SMD_3.25X0.85MM_NO_SILK"))
    )
    (comp (ref "JP1103")
      (value "M01PTH_SMD_3.25X0.85MM_NO_SILK")
      (footprint "eagle-import:1X01_SMD_3.25X0.85MM_NO_SILK")
      (libsource (lib "eagle-import") (part "M01PTH_SMD_3.25X0.85MM_NO_SILK"))
    )
    (comp (ref "JP1104")
      (value "M01PTH_SMD_3.25X0.85MM_NO_SILK")
      (footprint "eagle-import:1X01_SMD_3.25X0.85MM_NO_SILK")
      (libsource (lib "eagle-import") (part "M01PTH_SMD_3.25X0.85MM_NO_SILK"))
    )
    (comp (ref "JP1105")
      (value "M01PTH_SMD_3.25X0.85MM_NO_SILK")
      (footprint "eagle-import:1X01_SMD_3.25X0.85MM_NO_SILK")
      (libsource (lib "eagle-import") (part "M01PTH_SMD_3.25X0.85MM_NO_SILK"))
    )
    (comp (ref "JP1106")
      (value "M01PTH_SMD_3.25X0.85MM_NO_SILK")
      (footprint "eagle-import:1X01_SMD_3.25X0.85MM_NO_SILK")
      (libsource (lib "eagle-import") (part "M01PTH_SMD_3.25X0.85MM_NO_SILK"))
    )
    (comp (ref "JP1107")
      (value "M01PTH_SMD_3.25X0.85MM_NO_SILK")
      (footprint "eagle-import:1X01_SMD_3.25X0.85MM_NO_SILK")
      (libsource (lib "eagle-import") (part "M01PTH_SMD_3.25X0.85MM_NO_SILK"))
    )
    (comp (ref "JP1108")
      (value "M01PTH_SMD_3.25X0.85MM_NO_SILK")
      (footprint "eagle-import:1X01_SMD_3.25X0.85MM_NO_SILK")
      (libsource (lib "eagle-import") (part "M01PTH_SMD_3.25X0.85MM_NO_SILK"))
    )
    (comp (ref "JP1109")
      (value "M01PTH_SMD_3.25X0.85MM_NO_SILK")
      (footprint "eagle-import:1X01_SMD_3.25X0.85MM_NO_SILK")
      (libsource (lib "eagle-import") (part "M01PTH_SMD_3.25X0.85MM_NO_SILK"))
    )
    (comp (ref "JP1110")
      (value "M01PTH_SMD_3.25X0.85MM_NO_SILK")
      (footprint "eagle-import:1X01_SMD_3.25X0.85MM_NO_SILK")
      (libsource (lib "eagle-import") (part "M01PTH_SMD_3.25X0.85MM_NO_SILK"))
    )
    (comp (ref "JP1111")
      (value "M01PTH_SMD_3.25X0.85MM_NO_SILK")
      (footprint "eagle-import:1X01_SMD_3.25X0.85MM_NO_SILK")
      (libsource (lib "eagle-import") (part "M01PTH_SMD_3.25X0.85MM_NO_SILK"))
    )
    (comp (ref "JP1112")
      (value "M01PTH_SMD_3.25X0.85MM_NO_SILK")
      (footprint "eagle-import:1X01_SMD_3.25X0.85MM_NO_SILK")
      (libsource (lib "eagle-import") (part "M01PTH_SMD_3.25X0.85MM_NO_SILK"))
    )
    (comp (ref "JP1113")
      (value "M01PTH_SMD_3.25X0.85MM_NO_SILK")
      (footprint "eagle-import:1X01_SMD_3.25X0.85MM_NO_SILK")
      (libsource (lib "eagle-import") (part "M01PTH_SMD_3.25X0.85MM_NO_SILK"))
    )
    (comp (ref "JP1114")
      (value "M01PTH_SMD_3.25X0.85MM_NO_SILK")
      (footprint "eagle-import:1X01_SMD_3.25X0.85MM_NO_SILK")
      (libsource (lib "eagle-import") (part "M01PTH_SMD_3.25X0.85MM_NO_SILK"))
    )
    (comp (ref "JP1115")
      (value "M01PTH_SMD_3.25X0.85MM_NO_SILK")
      (footprint "eagle-import:1X01_SMD_3.25X0.85MM_NO_SILK")
      (libsource (lib "eagle-import") (part "M01PTH_SMD_3.25X0.85MM_NO_SILK"))
    )
    (comp (ref "JP1116")
      (value "M01PTH_SMD_3.25X0.85MM_NO_SILK")
      (footprint "eagle-import:1X01_SMD_3.25X0.85MM_NO_SILK")
      (libsource (lib "eagle-import") (part "M01PTH_SMD_3.25X0.85MM_NO_SILK"))
    )
    (comp (ref "JP1117")
      (value "M01PTH_SMD_3.25X0.85MM_NO_SILK")
      (footprint "eagle-import:1X01_SMD_3.25X0.85MM_NO_SILK")
      (libsource (lib "eagle-import") (part "M01PTH_SMD_3.25X0.85MM_NO_SILK"))
    )
    (comp (ref "JP1118")
      (value "M01PTH_SMD_3.25X0.85MM_NO_SILK")
      (footprint "eagle-import:1X01_SMD_3.25X0.85MM_NO_SILK")
      (libsource (lib "eagle-import") (part "M01PTH_SMD_3.25X0.85MM_NO_SILK"))
    )
    (comp (ref "JP1119")
      (value "M01PTH_SMD_3.25X0.85MM_NO_SILK")
      (footprint "eagle-import:1X01_SMD_3.25X0.85MM_NO_SILK")
      (libsource (lib "eagle-import") (part "M01PTH_SMD_3.25X0.85MM_NO_SILK"))
    )
    (comp (ref "JP1120")
      (value "M01PTH_SMD_3.25X0.85MM_NO_SILK")
      (footprint "eagle-import:1X01_SMD_3.25X0.85MM_NO_SILK")
      (libsource (lib "eagle-import") (part "M01PTH_SMD_3.25X0.85MM_NO_SILK"))
    )
    (comp (ref "JP1121")
      (value "M01PTH_SMD_3.25X0.85MM_NO_SILK")
      (footprint "eagle-import:1X01_SMD_3.25X0.85MM_NO_SILK")
      (libsource (lib "eagle-import") (part "M01PTH_SMD_3.25X0.85MM_NO_SILK"))
    )
    (comp (ref "JP1122")
      (value "M01PTH_SMD_3.25X0.85MM_NO_SILK")
      (footprint "eagle-import:1X01_SMD_3.25X0.85MM_NO_SILK")
      (libsource (lib "eagle-import") (part "M01PTH_SMD_3.25X0.85MM_NO_SILK"))
    )
    (comp (ref "JP1123")
      (value "M01PTH_SMD_3.25X0.85MM_NO_SILK")
      (footprint "eagle-import:1X01_SMD_3.25X0.85MM_NO_SILK")
      (libsource (lib "eagle-import") (part "M01PTH_SMD_3.25X0.85MM_NO_SILK"))
    )
    (comp (ref "JP1124")
      (value "M01PTH_SMD_3.25X0.85MM_NO_SILK")
      (footprint "eagle-import:1X01_SMD_3.25X0.85MM_NO_SILK")
      (libsource (lib "eagle-import") (part "M01PTH_SMD_3.25X0.85MM_NO_SILK"))
    )
    (comp (ref "JP1125")
      (value "M01PTH_SMD_3.25X0.85MM_NO_SILK")
      (footprint "eagle-import:1X01_SMD_3.25X0.85MM_NO_SILK")
      (libsource (lib "eagle-import") (part "M01PTH_SMD_3.25X0.85MM_NO_SILK"))
    )
    (comp (ref "JP1126")
      (value "M01PTH_SMD_3.25X0.85MM_NO_SILK")
      (footprint "eagle-import:1X01_SMD_3.25X0.85MM_NO_SILK")
      (libsource (lib "eagle-import") (part "M01PTH_SMD_3.25X0.85MM_NO_SILK"))
    )
    (comp (ref "JP1127")
      (value "M01PTH_SMD_3.25X0.85MM_NO_SILK")
      (footprint "eagle-import:1X01_SMD_3.25X0.85MM_NO_SILK")
      (libsource (lib "eagle-import") (part "M01PTH_SMD_3.25X0.85MM_NO_SILK"))
    )
    (comp (ref "JP1128")
      (value "M01PTH_SMD_3.25X0.85MM_NO_SILK")
      (footprint "eagle-import:1X01_SMD_3.25X0.85MM_NO_SILK")
      (libsource (lib "eagle-import") (part "M01PTH_SMD_3.25X0.85MM_NO_SILK"))
    )
    (comp (ref "JP1129")
      (value "M01PTH_SMD_3.25X0.85MM_NO_SILK")
      (footprint "eagle-import:1X01_SMD_3.25X0.85MM_NO_SILK")
      (libsource (lib "eagle-import") (part "M01PTH_SMD_3.25X0.85MM_NO_SILK"))
    )
    (comp (ref "JP1130")
      (value "M01PTH_SMD_3.25X0.85MM_NO_SILK")
      (footprint "eagle-import:1X01_SMD_3.25X0.85MM_NO_SILK")
      (libsource (lib "eagle-import") (part "M01PTH_SMD_3.25X0.85MM_NO_SILK"))
    )
    (comp (ref "JP1131")
      (value "M01PTH_SMD_3.25X0.85MM_NO_SILK")
      (footprint "eagle-import:1X01_SMD_3.25X0.85MM_NO_SILK")
      (libsource (lib "eagle-import") (part "M01PTH_SMD_3.25X0.85MM_NO_SILK"))
    )
    (comp (ref "JP1132")
      (value "M01PTH_SMD_3.25X0.85MM_NO_SILK")
      (footprint "eagle-import:1X01_SMD_3.25X0.85MM_NO_SILK")
      (libsource (lib "eagle-import") (part "M01PTH_SMD_3.25X0.85MM_NO_SILK"))
    )
    (comp (ref "JP1133")
      (value "M01PTH_SMD_3.25X0.85MM_NO_SILK")
      (footprint "eagle-import:1X01_SMD_3.25X0.85MM_NO_SILK")
      (libsource (lib "eagle-import") (part "M01PTH_SMD_3.25X0.85MM_NO_SILK"))
    )
    (comp (ref "JP1134")
      (value "M01PTH_SMD_3.25X0.85MM_NO_SILK")
      (footprint "eagle-import:1X01_SMD_3.25X0.85MM_NO_SILK")
      (libsource (lib "eagle-import") (part "M01PTH_SMD_3.25X0.85MM_NO_SILK"))
    )
    (comp (ref "JP1135")
      (value "M01PTH_SMD_3.25X0.85MM_NO_SILK")
      (footprint "eagle-import:1X01_SMD_3.25X0.85MM_NO_SILK")
      (libsource (lib "eagle-import") (part "M01PTH_SMD_3.25X0.85MM_NO_SILK"))
    )
    (comp (ref "JP1136")
      (value "M01PTH_SMD_3.25X0.85MM_NO_SILK")
      (footprint "eagle-import:1X01_SMD_3.25X0.85MM_NO_SILK")
      (libsource (lib "eagle-import") (part "M01PTH_SMD_3.25X0.85MM_NO_SILK"))
    )
    (comp (ref "JP1137")
      (value "M01PTH_SMD_3.25X0.85MM_NO_SILK")
      (footprint "eagle-import:1X01_SMD_3.25X0.85MM_NO_SILK")
      (libsource (lib "eagle-import") (part "M01PTH_SMD_3.25X0.85MM_NO_SILK"))
    )
    (comp (ref "JP1138")
      (value "M01PTH_SMD_3.25X0.85MM_NO_SILK")
      (footprint "eagle-import:1X01_SMD_3.25X0.85MM_NO_SILK")
      (libsource (lib "eagle-import") (part "M01PTH_SMD_3.25X0.85MM_NO_SILK"))
    )
    (comp (ref "JP1139")
      (value "M01PTH_SMD_3.25X0.85MM_NO_SILK")
      (footprint "eagle-import:1X01_SMD_3.25X0.85MM_NO_SILK")
      (libsource (lib "eagle-import") (part "M01PTH_SMD_3.25X0.85MM_NO_SILK"))
    )
    (comp (ref "JP1140")
      (value "M01PTH_SMD_3.25X0.85MM_NO_SILK")
      (footprint "eagle-import:1X01_SMD_3.25X0.85MM_NO_SILK")
      (libsource (lib "eagle-import") (part "M01PTH_SMD_3.25X0.85MM_NO_SILK"))
    )
    (comp (ref "JP1141")
      (value "M01PTH_SMD_3.25X0.85MM_NO_SILK")
      (footprint "eagle-import:1X01_SMD_3.25X0.85MM_NO_SILK")
      (libsource (lib "eagle-import") (part "M01PTH_SMD_3.25X0.85MM_NO_SILK"))
    )
    (comp (ref "JP1142")
      (value "M01PTH_SMD_3.25X0.85MM_NO_SILK")
      (footprint "eagle-import:1X01_SMD_3.25X0.85MM_NO_SILK")
      (libsource (lib "eagle-import") (part "M01PTH_SMD_3.25X0.85MM_NO_SILK"))
    )
    (comp (ref "JP1143")
      (value "M01PTH_SMD_3.25X0.85MM_NO_SILK")
      (footprint "eagle-import:1X01_SMD_3.25X0.85MM_NO_SILK")
      (libsource (lib "eagle-import") (part "M01PTH_SMD_3.25X0.85MM_NO_SILK"))
    )
    (comp (ref "JP1144")
      (value "M01PTH_SMD_3.25X0.85MM_NO_SILK")
      (footprint "eagle-import:1X01_SMD_3.25X0.85MM_NO_SILK")
      (libsource (lib "eagle-import") (part "M01PTH_SMD_3.25X0.85MM_NO_SILK"))
    )
    (comp (ref "JP1145")
      (value "M01PTH_SMD_3.25X0.85MM_NO_SILK")
      (footprint "eagle-import:1X01_SMD_3.25X0.85MM_NO_SILK")
      (libsource (lib "eagle-import") (part "M01PTH_SMD_3.25X0.85MM_NO_SILK"))
    )
    (comp (ref "JP1146")
      (value "M01PTH_SMD_3.25X0.85MM_NO_SILK")
      (footprint "eagle-import:1X01_SMD_3.25X0.85MM_NO_SILK")
      (libsource (lib "eagle-import") (part "M01PTH_SMD_3.25X0.85MM_NO_SILK"))
    )
    (comp (ref "JP1147")
      (value "M01PTH_SMD_3.25X0.85MM_NO_SILK")
      (footprint "eagle-import:1X01_SMD_3.25X0.85MM_NO_SILK")
      (libsource (lib "eagle-import") (part "M01PTH_SMD_3.25X0.85MM_NO_SILK"))
    )
    (comp (ref "JP1148")
      (value "M01PTH_SMD_3.25X0.85MM_NO_SILK")
      (footprint "eagle-import:1X01_SMD_3.25X0.85MM_NO_SILK")
      (libsource (lib "eagle-import") (part "M01PTH_SMD_3.25X0.85MM_NO_SILK"))
    )
    (comp (ref "JP1149")
      (value "M01PTH_SMD_3.25X0.85MM_NO_SILK")
      (footprint "eagle-import:1X01_SMD_3.25X0.85MM_NO_SILK")
      (libsource (lib "eagle-import") (part "M01PTH_SMD_3.25X0.85MM_NO_SILK"))
    )
    (comp (ref "JP1150")
      (value "M01PTH_SMD_3.25X0.85MM_NO_SILK")
      (footprint "eagle-import:1X01_SMD_3.25X0.85MM_NO_SILK")
      (libsource (lib "eagle-import") (part "M01PTH_SMD_3.25X0.85MM_NO_SILK"))
    )
    (comp (ref "JP1151")
      (value "M01PTH_SMD_3.25X0.85MM_NO_SILK")
      (footprint "eagle-import:1X01_SMD_3.25X0.85MM_NO_SILK")
      (libsource (lib "eagle-import") (part "M01PTH_SMD_3.25X0.85MM_NO_SILK"))
    )
    (comp (ref "JP1152")
      (value "M01PTH_SMD_3.25X0.85MM_NO_SILK")
      (footprint "eagle-import:1X01_SMD_3.25X0.85MM_NO_SILK")
      (libsource (lib "eagle-import") (part "M01PTH_SMD_3.25X0.85MM_NO_SILK"))
    )
    (comp (ref "JP1153")
      (value "M01PTH_SMD_3.25X0.85MM_NO_SILK")
      (footprint "eagle-import:1X01_SMD_3.25X0.85MM_NO_SILK")
      (libsource (lib "eagle-import") (part "M01PTH_SMD_3.25X0.85MM_NO_SILK"))
    )
    (comp (ref "JP1154")
      (value "M01PTH_SMD_3.25X0.85MM_NO_SILK")
      (footprint "eagle-import:1X01_SMD_3.25X0.85MM_NO_SILK")
      (libsource (lib "eagle-import") (part "M01PTH_SMD_3.25X0.85MM_NO_SILK"))
    )
    (comp (ref "JP1155")
      (value "M01PTH_SMD_3.25X0.85MM_NO_SILK")
      (footprint "eagle-import:1X01_SMD_3.25X0.85MM_NO_SILK")
      (libsource (lib "eagle-import") (part "M01PTH_SMD_3.25X0.85MM_NO_SILK"))
    )
    (comp (ref "JP1156")
      (value "M01PTH_SMD_3.25X0.85MM_NO_SILK")
      (footprint "eagle-import:1X01_SMD_3.25X0.85MM_NO_SILK")
      (libsource (lib "eagle-import") (part "M01PTH_SMD_3.25X0.85MM_NO_SILK"))
    )
    (comp (ref "JP1157")
      (value "M01PTH_SMD_3.25X0.85MM_NO_SILK")
      (footprint "eagle-import:1X01_SMD_3.25X0.85MM_NO_SILK")
      (libsource (lib "eagle-import") (part "M01PTH_SMD_3.25X0.85MM_NO_SILK"))
    )
    (comp (ref "JP1158")
      (value "M01PTH_SMD_3.25X0.85MM_NO_SILK")
      (footprint "eagle-import:1X01_SMD_3.25X0.85MM_NO_SILK")
      (libsource (lib "eagle-import") (part "M01PTH_SMD_3.25X0.85MM_NO_SILK"))
    )
    (comp (ref "JP1159")
      (value "M01PTH_SMD_3.25X0.85MM_NO_SILK")
      (footprint "eagle-import:1X01_SMD_3.25X0.85MM_NO_SILK")
      (libsource (lib "eagle-import") (part "M01PTH_SMD_3.25X0.85MM_NO_SILK"))
    )
    (comp (ref "JP1160")
      (value "M01PTH_SMD_3.25X0.85MM_NO_SILK")
      (footprint "eagle-import:1X01_SMD_3.25X0.85MM_NO_SILK")
      (libsource (lib "eagle-import") (part "M01PTH_SMD_3.25X0.85MM_NO_SILK"))
    )
    (comp (ref "JP1161")
      (value "M01PTH_SMD_3.25X0.85MM_NO_SILK")
      (footprint "eagle-import:1X01_SMD_3.25X0.85MM_NO_SILK")
      (libsource (lib "eagle-import") (part "M01PTH_SMD_3.25X0.85MM_NO_SILK"))
    )
    (comp (ref "JP1162")
      (value "M01PTH_SMD_3.25X0.85MM_NO_SILK")
      (footprint "eagle-import:1X01_SMD_3.25X0.85MM_NO_SILK")
      (libsource (lib "eagle-import") (part "M01PTH_SMD_3.25X0.85MM_NO_SILK"))
    )
    (comp (ref "JP1163")
      (value "M01PTH_SMD_3.25X0.85MM_NO_SILK")
      (footprint "eagle-import:1X01_SMD_3.25X0.85MM_NO_SILK")
      (libsource (lib "eagle-import") (part "M01PTH_SMD_3.25X0.85MM_NO_SILK"))
    )
    (comp (ref "JP1164")
      (value "M01PTH_SMD_3.25X0.85MM_NO_SILK")
      (footprint "eagle-import:1X01_SMD_3.25X0.85MM_NO_SILK")
      (libsource (lib "eagle-import") (part "M01PTH_SMD_3.25X0.85MM_NO_SILK"))
    )
    (comp (ref "JP1165")
      (value "M01PTH_SMD_3.25X0.85MM_NO_SILK")
      (footprint "eagle-import:1X01_SMD_3.25X0.85MM_NO_SILK")
      (libsource (lib "eagle-import") (part "M01PTH_SMD_3.25X0.85MM_NO_SILK"))
    )
    (comp (ref "JP1166")
      (value "M01PTH_SMD_3.25X0.85MM_NO_SILK")
      (footprint "eagle-import:1X01_SMD_3.25X0.85MM_NO_SILK")
      (libsource (lib "eagle-import") (part "M01PTH_SMD_3.25X0.85MM_NO_SILK"))
    )
    (comp (ref "JP1167")
      (value "M01PTH_SMD_3.25X0.85MM_NO_SILK")
      (footprint "eagle-import:1X01_SMD_3.25X0.85MM_NO_SILK")
      (libsource (lib "eagle-import") (part "M01PTH_SMD_3.25X0.85MM_NO_SILK"))
    )
    (comp (ref "JP1168")
      (value "M01PTH_SMD_3.25X0.85MM_NO_SILK")
      (footprint "eagle-import:1X01_SMD_3.25X0.85MM_NO_SILK")
      (libsource (lib "eagle-import") (part "M01PTH_SMD_3.25X0.85MM_NO_SILK"))
    )
    (comp (ref "JP1169")
      (value "M01PTH_SMD_3.25X0.85MM_NO_SILK")
      (footprint "eagle-import:1X01_SMD_3.25X0.85MM_NO_SILK")
      (libsource (lib "eagle-import") (part "M01PTH_SMD_3.25X0.85MM_NO_SILK"))
    )
    (comp (ref "JP1170")
      (value "M01PTH_SMD_3.25X0.85MM_NO_SILK")
      (footprint "eagle-import:1X01_SMD_3.25X0.85MM_NO_SILK")
      (libsource (lib "eagle-import") (part "M01PTH_SMD_3.25X0.85MM_NO_SILK"))
    )
    (comp (ref "JP1171")
      (value "M01PTH_SMD_3.25X0.85MM_NO_SILK")
      (footprint "eagle-import:1X01_SMD_3.25X0.85MM_NO_SILK")
      (libsource (lib "eagle-import") (part "M01PTH_SMD_3.25X0.85MM_NO_SILK"))
    )
    (comp (ref "JP1172")
      (value "M01PTH_SMD_3.25X0.85MM_NO_SILK")
      (footprint "eagle-import:1X01_SMD_3.25X0.85MM_NO_SILK")
      (libsource (lib "eagle-import") (part "M01PTH_SMD_3.25X0.85MM_NO_SILK"))
    )
    (comp (ref "JP1173")
      (value "M01PTH_SMD_3.25X0.85MM_NO_SILK")
      (footprint "eagle-import:1X01_SMD_3.25X0.85MM_NO_SILK")
      (libsource (lib "eagle-import") (part "M01PTH_SMD_3.25X0.85MM_NO_SILK"))
    )
    (comp (ref "JP1174")
      (value "M01PTH_SMD_3.25X0.85MM_NO_SILK")
      (footprint "eagle-import:1X01_SMD_3.25X0.85MM_NO_SILK")
      (libsource (lib "eagle-import") (part "M01PTH_SMD_3.25X0.85MM_NO_SILK"))
    )
    (comp (ref "JP1175")
      (value "M01PTH_SMD_3.25X0.85MM_NO_SILK")
      (footprint "eagle-import:1X01_SMD_3.25X0.85MM_NO_SILK")
      (libsource (lib "eagle-import") (part "M01PTH_SMD_3.25X0.85MM_NO_SILK"))
    )
    (comp (ref "JP1176")
      (value "M01PTH_SMD_3.25X0.85MM_NO_SILK")
      (footprint "eagle-import:1X01_SMD_3.25X0.85MM_NO_SILK")
      (libsource (lib "eagle-import") (part "M01PTH_SMD_3.25X0.85MM_NO_SILK"))
    )
    (comp (ref "JP1177")
      (value "M01PTH_SMD_3.25X0.85MM_NO_SILK")
      (footprint "eagle-import:1X01_SMD_3.25X0.85MM_NO_SILK")
      (libsource (lib "eagle-import") (part "M01PTH_SMD_3.25X0.85MM_NO_SILK"))
    )
    (comp (ref "JP1178")
      (value "M01PTH_SMD_3.25X0.85MM_NO_SILK")
      (footprint "eagle-import:1X01_SMD_3.25X0.85MM_NO_SILK")
      (libsource (lib "eagle-import") (part "M01PTH_SMD_3.25X0.85MM_NO_SILK"))
    )
    (comp (ref "JP1179")
      (value "M01PTH_SMD_3.25X0.85MM_NO_SILK")
      (footprint "eagle-import:1X01_SMD_3.25X0.85MM_NO_SILK")
      (libsource (lib "eagle-import") (part "M01PTH_SMD_3.25X0.85MM_NO_SILK"))
    )
    (comp (ref "JP1180")
      (value "M01PTH_SMD_3.25X0.85MM_NO_SILK")
      (footprint "eagle-import:1X01_SMD_3.25X0.85MM_NO_SILK")
      (libsource (lib "eagle-import") (part "M01PTH_SMD_3.25X0.85MM_NO_SILK"))
    )
    (comp (ref "JP1181")
      (value "M01PTH_SMD_3.25X0.85MM_NO_SILK")
      (footprint "eagle-import:1X01_SMD_3.25X0.85MM_NO_SILK")
      (libsource (lib "eagle-import") (part "M01PTH_SMD_3.25X0.85MM_NO_SILK"))
    )
    (comp (ref "JP1182")
      (value "M01PTH_SMD_3.25X0.85MM_NO_SILK")
      (footprint "eagle-import:1X01_SMD_3.25X0.85MM_NO_SILK")
      (libsource (lib "eagle-import") (part "M01PTH_SMD_3.25X0.85MM_NO_SILK"))
    )
    (comp (ref "JP1183")
      (value "M01PTH_SMD_3.25X0.85MM_NO_SILK")
      (footprint "eagle-import:1X01_SMD_3.25X0.85MM_NO_SILK")
      (libsource (lib "eagle-import") (part "M01PTH_SMD_3.25X0.85MM_NO_SILK"))
    )
    (comp (ref "JP1184")
      (value "M01PTH_SMD_3.25X0.85MM_NO_SILK")
      (footprint "eagle-import:1X01_SMD_3.25X0.85MM_NO_SILK")
      (libsource (lib "eagle-import") (part "M01PTH_SMD_3.25X0.85MM_NO_SILK"))
    )
    (comp (ref "JP1185")
      (value "M01PTH_SMD_3.25X0.85MM_NO_SILK")
      (footprint "eagle-import:1X01_SMD_3.25X0.85MM_NO_SILK")
      (libsource (lib "eagle-import") (part "M01PTH_SMD_3.25X0.85MM_NO_SILK"))
    )
    (comp (ref "JP1186")
      (value "M01PTH_SMD_3.25X0.85MM_NO_SILK")
      (footprint "eagle-import:1X01_SMD_3.25X0.85MM_NO_SILK")
      (libsource (lib "eagle-import") (part "M01PTH_SMD_3.25X0.85MM_NO_SILK"))
    )
    (comp (ref "JP1187")
      (value "M01PTH_SMD_3.25X0.85MM_NO_SILK")
      (footprint "eagle-import:1X01_SMD_3.25X0.85MM_NO_SILK")
      (libsource (lib "eagle-import") (part "M01PTH_SMD_3.25X0.85MM_NO_SILK"))
    )
    (comp (ref "JP1188")
      (value "M01PTH_SMD_3.25X0.85MM_NO_SILK")
      (footprint "eagle-import:1X01_SMD_3.25X0.85MM_NO_SILK")
      (libsource (lib "eagle-import") (part "M01PTH_SMD_3.25X0.85MM_NO_SILK"))
    )
    (comp (ref "JP1189")
      (value "M01PTH_SMD_3.25X0.85MM_NO_SILK")
      (footprint "eagle-import:1X01_SMD_3.25X0.85MM_NO_SILK")
      (libsource (lib "eagle-import") (part "M01PTH_SMD_3.25X0.85MM_NO_SILK"))
    )
    (comp (ref "JP1190")
      (value "M01PTH_SMD_3.25X0.85MM_NO_SILK")
      (footprint "eagle-import:1X01_SMD_3.25X0.85MM_NO_SILK")
      (libsource (lib "eagle-import") (part "M01PTH_SMD_3.25X0.85MM_NO_SILK"))
    )
    (comp (ref "JP1191")
      (value "M01PTH_SMD_3.25X0.85MM_NO_SILK")
      (footprint "eagle-import:1X01_SMD_3.25X0.85MM_NO_SILK")
      (libsource (lib "eagle-import") (part "M01PTH_SMD_3.25X0.85MM_NO_SILK"))
    )
    (comp (ref "JP1192")
      (value "M01PTH_SMD_3.25X0.85MM_NO_SILK")
      (footprint "eagle-import:1X01_SMD_3.25X0.85MM_NO_SILK")
      (libsource (lib "eagle-import") (part "M01PTH_SMD_3.25X0.85MM_NO_SILK"))
    )
    (comp (ref "JP1193")
      (value "M01PTH_SMD_3.25X0.85MM_NO_SILK")
      (footprint "eagle-import:1X01_SMD_3.25X0.85MM_NO_SILK")
      (libsource (lib "eagle-import") (part "M01PTH_SMD_3.25X0.85MM_NO_SILK"))
    )
    (comp (ref "JP1194")
      (value "M01PTH_SMD_3.25X0.85MM_NO_SILK")
      (footprint "eagle-import:1X01_SMD_3.25X0.85MM_NO_SILK")
      (libsource (lib "eagle-import") (part "M01PTH_SMD_3.25X0.85MM_NO_SILK"))
    )
    (comp (ref "JP1195")
      (value "M01PTH_SMD_3.25X0.85MM_NO_SILK")
      (footprint "eagle-import:1X01_SMD_3.25X0.85MM_NO_SILK")
      (libsource (lib "eagle-import") (part "M01PTH_SMD_3.25X0.85MM_NO_SILK"))
    )
    (comp (ref "JP1196")
      (value "M01PTH_SMD_3.25X0.85MM_NO_SILK")
      (footprint "eagle-import:1X01_SMD_3.25X0.85MM_NO_SILK")
      (libsource (lib "eagle-import") (part "M01PTH_SMD_3.25X0.85MM_NO_SILK"))
    )
    (comp (ref "JP1197")
      (value "M01PTH_SMD_3.25X0.85MM_NO_SILK")
      (footprint "eagle-import:1X01_SMD_3.25X0.85MM_NO_SILK")
      (libsource (lib "eagle-import") (part "M01PTH_SMD_3.25X0.85MM_NO_SILK"))
    )
    (comp (ref "JP1198")
      (value "M01PTH_SMD_3.25X0.85MM_NO_SILK")
      (footprint "eagle-import:1X01_SMD_3.25X0.85MM_NO_SILK")
      (libsource (lib "eagle-import") (part "M01PTH_SMD_3.25X0.85MM_NO_SILK"))
    )
    (comp (ref "JP1199")
      (value "M01PTH_SMD_3.25X0.85MM_NO_SILK")
      (footprint "eagle-import:1X01_SMD_3.25X0.85MM_NO_SILK")
      (libsource (lib "eagle-import") (part "M01PTH_SMD_3.25X0.85MM_NO_SILK"))
    )
    (comp (ref "JP1200")
      (value "M01PTH_SMD_3.25X0.85MM_NO_SILK")
      (footprint "eagle-import:1X01_SMD_3.25X0.85MM_NO_SILK")
      (libsource (lib "eagle-import") (part "M01PTH_SMD_3.25X0.85MM_NO_SILK"))
    )
  )
  (nets
    (net (code "1") (name "/0_1440127218") (class "Default")
      (node (ref "JP1") (pin "1") (pinfunction "1_1") (pintype "passive"))
      (node (ref "JP961") (pin "P$1") (pinfunction "1_P$1") (pintype "passive"))
    )
    (net (code "2") (name "/0_1440127248") (class "Default")
      (node (ref "JP10") (pin "1") (pinfunction "1_1") (pintype "passive"))
      (node (ref "JP1021") (pin "P$1") (pinfunction "1_P$1") (pintype "passive"))
    )
    (net (code "3") (name "/0_1440127317") (class "Default")
      (node (ref "JP1141") (pin "P$1") (pinfunction "1_P$1") (pintype "passive"))
      (node (ref "JP5") (pin "1") (pinfunction "1_1") (pintype "passive"))
    )
    (net (code "4") (name "/0_1440127347") (class "Default")
      (node (ref "JP1142") (pin "P$1") (pinfunction "1_P$1") (pintype "passive"))
      (node (ref "JP15") (pin "1") (pinfunction "1_1") (pintype "passive"))
    )
    (net (code "5") (name "/0_1440127366") (class "Default")
      (node (ref "JP1143") (pin "P$1") (pinfunction "1_P$1") (pintype "passive"))
      (node (ref "JP25") (pin "1") (pinfunction "1_1") (pintype "passive"))
    )
    (net (code "6") (name "/0_1440127382") (class "Default")
      (node (ref "JP1144") (pin "P$1") (pinfunction "1_P$1") (pintype "passive"))
      (node (ref "JP35") (pin "1") (pinfunction "1_1") (pintype "passive"))
    )
    (net (code "7") (name "/0_1440127392") (class "Default")
      (node (ref "JP1145") (pin "P$1") (pinfunction "1_P$1") (pintype "passive"))
      (node (ref "JP45") (pin "1") (pinfunction "1_1") (pintype "passive"))
    )
    (net (code "8") (name "/0_1440127421") (class "Default")
      (node (ref "JP1146") (pin "P$1") (pinfunction "1_P$1") (pintype "passive"))
      (node (ref "JP55") (pin "1") (pinfunction "1_1") (pintype "passive"))
    )
    (net (code "9") (name "/0_1440127430") (class "Default")
      (node (ref "JP1147") (pin "P$1") (pinfunction "1_P$1") (pintype "passive"))
      (node (ref "JP65") (pin "1") (pinfunction "1_1") (pintype "passive"))
    )
    (net (code "10") (name "/0_1440127608") (class "Default")
      (node (ref "JP1148") (pin "P$1") (pinfunction "1_P$1") (pintype "passive"))
      (node (ref "JP75") (pin "1") (pinfunction "1_1") (pintype "passive"))
    )
    (net (code "11") (name "/0_1440127617") (class "Default")
      (node (ref "JP1149") (pin "P$1") (pinfunction "1_P$1") (pintype "passive"))
      (node (ref "JP85") (pin "1") (pinfunction "1_1") (pintype "passive"))
    )
    (net (code "12") (name "/0_1440127627") (class "Default")
      (node (ref "JP1150") (pin "P$1") (pinfunction "1_P$1") (pintype "passive"))
      (node (ref "JP95") (pin "1") (pinfunction "1_1") (pintype "passive"))
    )
    (net (code "13") (name "/0_1440127700") (class "Default")
      (node (ref "JP105") (pin "1") (pinfunction "1_1") (pintype "passive"))
      (node (ref "JP1151") (pin "P$1") (pinfunction "1_P$1") (pintype "passive"))
    )
    (net (code "14") (name "/0_1440127712") (class "Default")
      (node (ref "JP115") (pin "1") (pinfunction "1_1") (pintype "passive"))
      (node (ref "JP1152") (pin "P$1") (pinfunction "1_P$1") (pintype "passive"))
    )
    (net (code "15") (name "/0_1440127720") (class "Default")
      (node (ref "JP1153") (pin "P$1") (pinfunction "1_P$1") (pintype "passive"))
      (node (ref "JP125") (pin "1") (pinfunction "1_1") (pintype "passive"))
    )
    (net (code "16") (name "/0_1440127729") (class "Default")
      (node (ref "JP1154") (pin "P$1") (pinfunction "1_P$1") (pintype "passive"))
      (node (ref "JP135") (pin "1") (pinfunction "1_1") (pintype "passive"))
    )
    (net (code "17") (name "/0_1440127744") (class "Default")
      (node (ref "JP1155") (pin "P$1") (pinfunction "1_P$1") (pintype "passive"))
      (node (ref "JP145") (pin "1") (pinfunction "1_1") (pintype "passive"))
    )
    (net (code "18") (name "/0_1440127816") (class "Default")
      (node (ref "JP1156") (pin "P$1") (pinfunction "1_P$1") (pintype "passive"))
      (node (ref "JP155") (pin "1") (pinfunction "1_1") (pintype "passive"))
    )
    (net (code "19") (name "/0_1440127828") (class "Default")
      (node (ref "JP1157") (pin "P$1") (pinfunction "1_P$1") (pintype "passive"))
      (node (ref "JP165") (pin "1") (pinfunction "1_1") (pintype "passive"))
    )
    (net (code "20") (name "/0_1440127838") (class "Default")
      (node (ref "JP1158") (pin "P$1") (pinfunction "1_P$1") (pintype "passive"))
      (node (ref "JP175") (pin "1") (pinfunction "1_1") (pintype "passive"))
    )
    (net (code "21") (name "/0_1440127850") (class "Default")
      (node (ref "JP1159") (pin "P$1") (pinfunction "1_P$1") (pintype "passive"))
      (node (ref "JP185") (pin "1") (pinfunction "1_1") (pintype "passive"))
    )
    (net (code "22") (name "/0_1440127870") (class "Default")
      (node (ref "JP1160") (pin "P$1") (pinfunction "1_P$1") (pintype "passive"))
      (node (ref "JP195") (pin "1") (pinfunction "1_1") (pintype "passive"))
    )
    (net (code "23") (name "/0_1440127904") (class "Default")
      (node (ref "JP1181") (pin "P$1") (pinfunction "1_P$1") (pintype "passive"))
      (node (ref "JP295") (pin "1") (pinfunction "1_1") (pintype "passive"))
    )
    (net (code "24") (name "/0_1440127914") (class "Default")
      (node (ref "JP1182") (pin "P$1") (pinfunction "1_P$1") (pintype "passive"))
      (node (ref "JP285") (pin "1") (pinfunction "1_1") (pintype "passive"))
    )
    (net (code "25") (name "/0_1440127944") (class "Default")
      (node (ref "JP1183") (pin "P$1") (pinfunction "1_P$1") (pintype "passive"))
      (node (ref "JP275") (pin "1") (pinfunction "1_1") (pintype "passive"))
    )
    (net (code "26") (name "/0_1440127955") (class "Default")
      (node (ref "JP1184") (pin "P$1") (pinfunction "1_P$1") (pintype "passive"))
      (node (ref "JP265") (pin "1") (pinfunction "1_1") (pintype "passive"))
    )
    (net (code "27") (name "/0_1440128006") (class "Default")
      (node (ref "JP1185") (pin "P$1") (pinfunction "1_P$1") (pintype "passive"))
      (node (ref "JP255") (pin "1") (pinfunction "1_1") (pintype "passive"))
    )
    (net (code "28") (name "/0_1440128015") (class "Default")
      (node (ref "JP1186") (pin "P$1") (pinfunction "1_P$1") (pintype "passive"))
      (node (ref "JP245") (pin "1") (pinfunction "1_1") (pintype "passive"))
    )
    (net (code "29") (name "/0_1440128025") (class "Default")
      (node (ref "JP1187") (pin "P$1") (pinfunction "1_P$1") (pintype "passive"))
      (node (ref "JP235") (pin "1") (pinfunction "1_1") (pintype "passive"))
    )
    (net (code "30") (name "/0_1440128039") (class "Default")
      (node (ref "JP1188") (pin "P$1") (pinfunction "1_P$1") (pintype "passive"))
      (node (ref "JP225") (pin "1") (pinfunction "1_1") (pintype "passive"))
    )
    (net (code "31") (name "/0_1440128052") (class "Default")
      (node (ref "JP1189") (pin "P$1") (pinfunction "1_P$1") (pintype "passive"))
      (node (ref "JP215") (pin "1") (pinfunction "1_1") (pintype "passive"))
    )
    (net (code "32") (name "/0_1440128062") (class "Default")
      (node (ref "JP1190") (pin "P$1") (pinfunction "1_P$1") (pintype "passive"))
      (node (ref "JP205") (pin "1") (pinfunction "1_1") (pintype "passive"))
    )
    (net (code "33") (name "/0_1440128088") (class "Default")
      (node (ref "JP1170") (pin "P$1") (pinfunction "1_P$1") (pintype "passive"))
      (node (ref "JP6") (pin "1") (pinfunction "1_1") (pintype "passive"))
    )
    (net (code "34") (name "/0_1440128098") (class "Default")
      (node (ref "JP1169") (pin "P$1") (pinfunction "1_P$1") (pintype "passive"))
      (node (ref "JP16") (pin "1") (pinfunction "1_1") (pintype "passive"))
    )
    (net (code "35") (name "/0_1440128106") (class "Default")
      (node (ref "JP1168") (pin "P$1") (pinfunction "1_P$1") (pintype "passive"))
      (node (ref "JP26") (pin "1") (pinfunction "1_1") (pintype "passive"))
    )
    (net (code "36") (name "/0_1440128116") (class "Default")
      (node (ref "JP1167") (pin "P$1") (pinfunction "1_P$1") (pintype "passive"))
      (node (ref "JP36") (pin "1") (pinfunction "1_1") (pintype "passive"))
    )
    (net (code "37") (name "/0_1440128126") (class "Default")
      (node (ref "JP1166") (pin "P$1") (pinfunction "1_P$1") (pintype "passive"))
      (node (ref "JP46") (pin "1") (pinfunction "1_1") (pintype "passive"))
    )
    (net (code "38") (name "/0_1440128135") (class "Default")
      (node (ref "JP1165") (pin "P$1") (pinfunction "1_P$1") (pintype "passive"))
      (node (ref "JP56") (pin "1") (pinfunction "1_1") (pintype "passive"))
    )
    (net (code "39") (name "/0_1440128149") (class "Default")
      (node (ref "JP1164") (pin "P$1") (pinfunction "1_P$1") (pintype "passive"))
      (node (ref "JP66") (pin "1") (pinfunction "1_1") (pintype "passive"))
    )
    (net (code "40") (name "/0_1440128159") (class "Default")
      (node (ref "JP1163") (pin "P$1") (pinfunction "1_P$1") (pintype "passive"))
      (node (ref "JP76") (pin "1") (pinfunction "1_1") (pintype "passive"))
    )
    (net (code "41") (name "/0_1440128167") (class "Default")
      (node (ref "JP1162") (pin "P$1") (pinfunction "1_P$1") (pintype "passive"))
      (node (ref "JP86") (pin "1") (pinfunction "1_1") (pintype "passive"))
    )
    (net (code "42") (name "/0_1440128175") (class "Default")
      (node (ref "JP1161") (pin "P$1") (pinfunction "1_P$1") (pintype "passive"))
      (node (ref "JP96") (pin "1") (pinfunction "1_1") (pintype "passive"))
    )
    (net (code "43") (name "/0_1440128223") (class "Default")
      (node (ref "JP106") (pin "1") (pinfunction "1_1") (pintype "passive"))
      (node (ref "JP1180") (pin "P$1") (pinfunction "1_P$1") (pintype "passive"))
    )
    (net (code "44") (name "/0_1440128233") (class "Default")
      (node (ref "JP116") (pin "1") (pinfunction "1_1") (pintype "passive"))
      (node (ref "JP1179") (pin "P$1") (pinfunction "1_P$1") (pintype "passive"))
    )
    (net (code "45") (name "/0_1440128243") (class "Default")
      (node (ref "JP1178") (pin "P$1") (pinfunction "1_P$1") (pintype "passive"))
      (node (ref "JP126") (pin "1") (pinfunction "1_1") (pintype "passive"))
    )
    (net (code "46") (name "/0_1440128252") (class "Default")
      (node (ref "JP1177") (pin "P$1") (pinfunction "1_P$1") (pintype "passive"))
      (node (ref "JP136") (pin "1") (pinfunction "1_1") (pintype "passive"))
    )
    (net (code "47") (name "/0_1440128264") (class "Default")
      (node (ref "JP1176") (pin "P$1") (pinfunction "1_P$1") (pintype "passive"))
      (node (ref "JP146") (pin "1") (pinfunction "1_1") (pintype "passive"))
    )
    (net (code "48") (name "/0_1440128275") (class "Default")
      (node (ref "JP1175") (pin "P$1") (pinfunction "1_P$1") (pintype "passive"))
      (node (ref "JP156") (pin "1") (pinfunction "1_1") (pintype "passive"))
    )
    (net (code "49") (name "/0_1440128290") (class "Default")
      (node (ref "JP1174") (pin "P$1") (pinfunction "1_P$1") (pintype "passive"))
      (node (ref "JP166") (pin "1") (pinfunction "1_1") (pintype "passive"))
    )
    (net (code "50") (name "/0_1440128302") (class "Default")
      (node (ref "JP1173") (pin "P$1") (pinfunction "1_P$1") (pintype "passive"))
      (node (ref "JP176") (pin "1") (pinfunction "1_1") (pintype "passive"))
    )
    (net (code "51") (name "/0_1440128314") (class "Default")
      (node (ref "JP1172") (pin "P$1") (pinfunction "1_P$1") (pintype "passive"))
      (node (ref "JP186") (pin "1") (pinfunction "1_1") (pintype "passive"))
    )
    (net (code "52") (name "/0_1440128326") (class "Default")
      (node (ref "JP1171") (pin "P$1") (pinfunction "1_P$1") (pintype "passive"))
      (node (ref "JP196") (pin "1") (pinfunction "1_1") (pintype "passive"))
    )
    (net (code "53") (name "/0_1440128344") (class "Default")
      (node (ref "JP1200") (pin "P$1") (pinfunction "1_P$1") (pintype "passive"))
      (node (ref "JP296") (pin "1") (pinfunction "1_1") (pintype "passive"))
    )
    (net (code "54") (name "/0_1440128353") (class "Default")
      (node (ref "JP1199") (pin "P$1") (pinfunction "1_P$1") (pintype "passive"))
      (node (ref "JP286") (pin "1") (pinfunction "1_1") (pintype "passive"))
    )
    (net (code "55") (name "/0_1440128363") (class "Default")
      (node (ref "JP1198") (pin "P$1") (pinfunction "1_P$1") (pintype "passive"))
      (node (ref "JP276") (pin "1") (pinfunction "1_1") (pintype "passive"))
    )
    (net (code "56") (name "/0_1440128375") (class "Default")
      (node (ref "JP1197") (pin "P$1") (pinfunction "1_P$1") (pintype "passive"))
      (node (ref "JP266") (pin "1") (pinfunction "1_1") (pintype "passive"))
    )
    (net (code "57") (name "/0_1440128386") (class "Default")
      (node (ref "JP1196") (pin "P$1") (pinfunction "1_P$1") (pintype "passive"))
      (node (ref "JP256") (pin "1") (pinfunction "1_1") (pintype "passive"))
    )
    (net (code "58") (name "/0_1440128396") (class "Default")
      (node (ref "JP1195") (pin "P$1") (pinfunction "1_P$1") (pintype "passive"))
      (node (ref "JP246") (pin "1") (pinfunction "1_1") (pintype "passive"))
    )
    (net (code "59") (name "/0_1440128405") (class "Default")
      (node (ref "JP1194") (pin "P$1") (pinfunction "1_P$1") (pintype "passive"))
      (node (ref "JP236") (pin "1") (pinfunction "1_1") (pintype "passive"))
    )
    (net (code "60") (name "/0_1440128414") (class "Default")
      (node (ref "JP1193") (pin "P$1") (pinfunction "1_P$1") (pintype "passive"))
      (node (ref "JP226") (pin "1") (pinfunction "1_1") (pintype "passive"))
    )
    (net (code "61") (name "/0_1440128424") (class "Default")
      (node (ref "JP1192") (pin "P$1") (pinfunction "1_P$1") (pintype "passive"))
      (node (ref "JP216") (pin "1") (pinfunction "1_1") (pintype "passive"))
    )
    (net (code "62") (name "/0_1440128432") (class "Default")
      (node (ref "JP1191") (pin "P$1") (pinfunction "1_P$1") (pintype "passive"))
      (node (ref "JP206") (pin "1") (pinfunction "1_1") (pintype "passive"))
    )
    (net (code "63") (name "/1_1440127218") (class "Default")
      (node (ref "JP11") (pin "1") (pinfunction "1_1") (pintype "passive"))
      (node (ref "JP963") (pin "P$1") (pinfunction "1_P$1") (pintype "passive"))
    )
    (net (code "64") (name "/1_1440127248") (class "Default")
      (node (ref "JP1023") (pin "P$1") (pinfunction "1_P$1") (pintype "passive"))
      (node (ref "JP20") (pin "1") (pinfunction "1_1") (pintype "passive"))
    )
    (net (code "65") (name "/2_1440127218") (class "Default")
      (node (ref "JP21") (pin "1") (pinfunction "1_1") (pintype "passive"))
      (node (ref "JP965") (pin "P$1") (pinfunction "1_P$1") (pintype "passive"))
    )
    (net (code "66") (name "/2_1440127248") (class "Default")
      (node (ref "JP1025") (pin "P$1") (pinfunction "1_P$1") (pintype "passive"))
      (node (ref "JP30") (pin "1") (pinfunction "1_1") (pintype "passive"))
    )
    (net (code "67") (name "/3_1440127218") (class "Default")
      (node (ref "JP31") (pin "1") (pinfunction "1_1") (pintype "passive"))
      (node (ref "JP967") (pin "P$1") (pinfunction "1_P$1") (pintype "passive"))
    )
    (net (code "68") (name "/3_1440127248") (class "Default")
      (node (ref "JP1027") (pin "P$1") (pinfunction "1_P$1") (pintype "passive"))
      (node (ref "JP40") (pin "1") (pinfunction "1_1") (pintype "passive"))
    )
    (net (code "69") (name "/4_1440127218") (class "Default")
      (node (ref "JP41") (pin "1") (pinfunction "1_1") (pintype "passive"))
      (node (ref "JP969") (pin "P$1") (pinfunction "1_P$1") (pintype "passive"))
    )
    (net (code "70") (name "/4_1440127248") (class "Default")
      (node (ref "JP1029") (pin "P$1") (pinfunction "1_P$1") (pintype "passive"))
      (node (ref "JP50") (pin "1") (pinfunction "1_1") (pintype "passive"))
    )
    (net (code "71") (name "/5_1440127218") (class "Default")
      (node (ref "JP51") (pin "1") (pinfunction "1_1") (pintype "passive"))
      (node (ref "JP971") (pin "P$1") (pinfunction "1_P$1") (pintype "passive"))
    )
    (net (code "72") (name "/5_1440127248") (class "Default")
      (node (ref "JP1031") (pin "P$1") (pinfunction "1_P$1") (pintype "passive"))
      (node (ref "JP60") (pin "1") (pinfunction "1_1") (pintype "passive"))
    )
    (net (code "73") (name "/6_1440127218") (class "Default")
      (node (ref "JP61") (pin "1") (pinfunction "1_1") (pintype "passive"))
      (node (ref "JP973") (pin "P$1") (pinfunction "1_P$1") (pintype "passive"))
    )
    (net (code "74") (name "/6_1440127248") (class "Default")
      (node (ref "JP1033") (pin "P$1") (pinfunction "1_P$1") (pintype "passive"))
      (node (ref "JP70") (pin "1") (pinfunction "1_1") (pintype "passive"))
    )
    (net (code "75") (name "/7_1440127218") (class "Default")
      (node (ref "JP71") (pin "1") (pinfunction "1_1") (pintype "passive"))
      (node (ref "JP975") (pin "P$1") (pinfunction "1_P$1") (pintype "passive"))
    )
    (net (code "76") (name "/7_1440127248") (class "Default")
      (node (ref "JP1035") (pin "P$1") (pinfunction "1_P$1") (pintype "passive"))
      (node (ref "JP80") (pin "1") (pinfunction "1_1") (pintype "passive"))
    )
    (net (code "77") (name "/8_1440127218") (class "Default")
      (node (ref "JP81") (pin "1") (pinfunction "1_1") (pintype "passive"))
      (node (ref "JP977") (pin "P$1") (pinfunction "1_P$1") (pintype "passive"))
    )
    (net (code "78") (name "/8_1440127248") (class "Default")
      (node (ref "JP1037") (pin "P$1") (pinfunction "1_P$1") (pintype "passive"))
      (node (ref "JP90") (pin "1") (pinfunction "1_1") (pintype "passive"))
    )
    (net (code "79") (name "/9_1440127218") (class "Default")
      (node (ref "JP91") (pin "1") (pinfunction "1_1") (pintype "passive"))
      (node (ref "JP979") (pin "P$1") (pinfunction "1_P$1") (pintype "passive"))
    )
    (net (code "80") (name "/9_1440127248") (class "Default")
      (node (ref "JP100") (pin "1") (pinfunction "1_1") (pintype "passive"))
      (node (ref "JP1039") (pin "P$1") (pinfunction "1_P$1") (pintype "passive"))
    )
    (net (code "81") (name "/10_1440127218") (class "Default")
      (node (ref "JP101") (pin "1") (pinfunction "1_1") (pintype "passive"))
      (node (ref "JP981") (pin "P$1") (pinfunction "1_P$1") (pintype "passive"))
    )
    (net (code "82") (name "/10_1440127248") (class "Default")
      (node (ref "JP1041") (pin "P$1") (pinfunction "1_P$1") (pintype "passive"))
      (node (ref "JP110") (pin "1") (pinfunction "1_1") (pintype "passive"))
    )
    (net (code "83") (name "/11_1440127218") (class "Default")
      (node (ref "JP111") (pin "1") (pinfunction "1_1") (pintype "passive"))
      (node (ref "JP983") (pin "P$1") (pinfunction "1_P$1") (pintype "passive"))
    )
    (net (code "84") (name "/11_1440127248") (class "Default")
      (node (ref "JP1043") (pin "P$1") (pinfunction "1_P$1") (pintype "passive"))
      (node (ref "JP120") (pin "1") (pinfunction "1_1") (pintype "passive"))
    )
    (net (code "85") (name "/12_1440127218") (class "Default")
      (node (ref "JP121") (pin "1") (pinfunction "1_1") (pintype "passive"))
      (node (ref "JP985") (pin "P$1") (pinfunction "1_P$1") (pintype "passive"))
    )
    (net (code "86") (name "/12_1440127248") (class "Default")
      (node (ref "JP1045") (pin "P$1") (pinfunction "1_P$1") (pintype "passive"))
      (node (ref "JP130") (pin "1") (pinfunction "1_1") (pintype "passive"))
    )
    (net (code "87") (name "/13_1440127218") (class "Default")
      (node (ref "JP131") (pin "1") (pinfunction "1_1") (pintype "passive"))
      (node (ref "JP987") (pin "P$1") (pinfunction "1_P$1") (pintype "passive"))
    )
    (net (code "88") (name "/13_1440127248") (class "Default")
      (node (ref "JP1047") (pin "P$1") (pinfunction "1_P$1") (pintype "passive"))
      (node (ref "JP140") (pin "1") (pinfunction "1_1") (pintype "passive"))
    )
    (net (code "89") (name "/14_1440127218") (class "Default")
      (node (ref "JP141") (pin "1") (pinfunction "1_1") (pintype "passive"))
      (node (ref "JP989") (pin "P$1") (pinfunction "1_P$1") (pintype "passive"))
    )
    (net (code "90") (name "/14_1440127248") (class "Default")
      (node (ref "JP1049") (pin "P$1") (pinfunction "1_P$1") (pintype "passive"))
      (node (ref "JP150") (pin "1") (pinfunction "1_1") (pintype "passive"))
    )
    (net (code "91") (name "/15_1440127218") (class "Default")
      (node (ref "JP151") (pin "1") (pinfunction "1_1") (pintype "passive"))
      (node (ref "JP991") (pin "P$1") (pinfunction "1_P$1") (pintype "passive"))
    )
    (net (code "92") (name "/15_1440127248") (class "Default")
      (node (ref "JP1051") (pin "P$1") (pinfunction "1_P$1") (pintype "passive"))
      (node (ref "JP160") (pin "1") (pinfunction "1_1") (pintype "passive"))
    )
    (net (code "93") (name "/16_1440127218") (class "Default")
      (node (ref "JP161") (pin "1") (pinfunction "1_1") (pintype "passive"))
      (node (ref "JP993") (pin "P$1") (pinfunction "1_P$1") (pintype "passive"))
    )
    (net (code "94") (name "/16_1440127248") (class "Default")
      (node (ref "JP1053") (pin "P$1") (pinfunction "1_P$1") (pintype "passive"))
      (node (ref "JP170") (pin "1") (pinfunction "1_1") (pintype "passive"))
    )
    (net (code "95") (name "/17_1440127218") (class "Default")
      (node (ref "JP171") (pin "1") (pinfunction "1_1") (pintype "passive"))
      (node (ref "JP995") (pin "P$1") (pinfunction "1_P$1") (pintype "passive"))
    )
    (net (code "96") (name "/17_1440127248") (class "Default")
      (node (ref "JP1055") (pin "P$1") (pinfunction "1_P$1") (pintype "passive"))
      (node (ref "JP180") (pin "1") (pinfunction "1_1") (pintype "passive"))
    )
    (net (code "97") (name "/18_1440127218") (class "Default")
      (node (ref "JP181") (pin "1") (pinfunction "1_1") (pintype "passive"))
      (node (ref "JP997") (pin "P$1") (pinfunction "1_P$1") (pintype "passive"))
    )
    (net (code "98") (name "/18_1440127248") (class "Default")
      (node (ref "JP1057") (pin "P$1") (pinfunction "1_P$1") (pintype "passive"))
      (node (ref "JP190") (pin "1") (pinfunction "1_1") (pintype "passive"))
    )
    (net (code "99") (name "/19_1440127218") (class "Default")
      (node (ref "JP191") (pin "1") (pinfunction "1_1") (pintype "passive"))
      (node (ref "JP999") (pin "P$1") (pinfunction "1_P$1") (pintype "passive"))
    )
    (net (code "100") (name "/19_1440127248") (class "Default")
      (node (ref "JP1059") (pin "P$1") (pinfunction "1_P$1") (pintype "passive"))
      (node (ref "JP200") (pin "1") (pinfunction "1_1") (pintype "passive"))
    )
    (net (code "101") (name "/20_1440127218") (class "Default")
      (node (ref "JP1001") (pin "P$1") (pinfunction "1_P$1") (pintype "passive"))
      (node (ref "JP201") (pin "1") (pinfunction "1_1") (pintype "passive"))
    )
    (net (code "102") (name "/20_1440127248") (class "Default")
      (node (ref "JP1061") (pin "P$1") (pinfunction "1_P$1") (pintype "passive"))
      (node (ref "JP210") (pin "1") (pinfunction "1_1") (pintype "passive"))
    )
    (net (code "103") (name "/21_1440127218") (class "Default")
      (node (ref "JP1003") (pin "P$1") (pinfunction "1_P$1") (pintype "passive"))
      (node (ref "JP211") (pin "1") (pinfunction "1_1") (pintype "passive"))
    )
    (net (code "104") (name "/21_1440127248") (class "Default")
      (node (ref "JP1063") (pin "P$1") (pinfunction "1_P$1") (pintype "passive"))
      (node (ref "JP220") (pin "1") (pinfunction "1_1") (pintype "passive"))
    )
    (net (code "105") (name "/22_1440127218") (class "Default")
      (node (ref "JP1005") (pin "P$1") (pinfunction "1_P$1") (pintype "passive"))
      (node (ref "JP221") (pin "1") (pinfunction "1_1") (pintype "passive"))
    )
    (net (code "106") (name "/22_1440127248") (class "Default")
      (node (ref "JP1065") (pin "P$1") (pinfunction "1_P$1") (pintype "passive"))
      (node (ref "JP230") (pin "1") (pinfunction "1_1") (pintype "passive"))
    )
    (net (code "107") (name "/23_1440127218") (class "Default")
      (node (ref "JP1007") (pin "P$1") (pinfunction "1_P$1") (pintype "passive"))
      (node (ref "JP231") (pin "1") (pinfunction "1_1") (pintype "passive"))
    )
    (net (code "108") (name "/23_1440127248") (class "Default")
      (node (ref "JP1067") (pin "P$1") (pinfunction "1_P$1") (pintype "passive"))
      (node (ref "JP240") (pin "1") (pinfunction "1_1") (pintype "passive"))
    )
    (net (code "109") (name "/24_1440127218") (class "Default")
      (node (ref "JP1009") (pin "P$1") (pinfunction "1_P$1") (pintype "passive"))
      (node (ref "JP241") (pin "1") (pinfunction "1_1") (pintype "passive"))
    )
    (net (code "110") (name "/24_1440127248") (class "Default")
      (node (ref "JP1069") (pin "P$1") (pinfunction "1_P$1") (pintype "passive"))
      (node (ref "JP250") (pin "1") (pinfunction "1_1") (pintype "passive"))
    )
    (net (code "111") (name "/25_1440127218") (class "Default")
      (node (ref "JP1011") (pin "P$1") (pinfunction "1_P$1") (pintype "passive"))
      (node (ref "JP251") (pin "1") (pinfunction "1_1") (pintype "passive"))
    )
    (net (code "112") (name "/25_1440127248") (class "Default")
      (node (ref "JP1071") (pin "P$1") (pinfunction "1_P$1") (pintype "passive"))
      (node (ref "JP260") (pin "1") (pinfunction "1_1") (pintype "passive"))
    )
    (net (code "113") (name "/26_1440127218") (class "Default")
      (node (ref "JP1013") (pin "P$1") (pinfunction "1_P$1") (pintype "passive"))
      (node (ref "JP261") (pin "1") (pinfunction "1_1") (pintype "passive"))
    )
    (net (code "114") (name "/26_1440127248") (class "Default")
      (node (ref "JP1073") (pin "P$1") (pinfunction "1_P$1") (pintype "passive"))
      (node (ref "JP270") (pin "1") (pinfunction "1_1") (pintype "passive"))
    )
    (net (code "115") (name "/27_1440127218") (class "Default")
      (node (ref "JP1015") (pin "P$1") (pinfunction "1_P$1") (pintype "passive"))
      (node (ref "JP271") (pin "1") (pinfunction "1_1") (pintype "passive"))
    )
    (net (code "116") (name "/27_1440127248") (class "Default")
      (node (ref "JP1075") (pin "P$1") (pinfunction "1_P$1") (pintype "passive"))
      (node (ref "JP280") (pin "1") (pinfunction "1_1") (pintype "passive"))
    )
    (net (code "117") (name "/28_1440127218") (class "Default")
      (node (ref "JP1017") (pin "P$1") (pinfunction "1_P$1") (pintype "passive"))
      (node (ref "JP281") (pin "1") (pinfunction "1_1") (pintype "passive"))
    )
    (net (code "118") (name "/28_1440127248") (class "Default")
      (node (ref "JP1077") (pin "P$1") (pinfunction "1_P$1") (pintype "passive"))
      (node (ref "JP290") (pin "1") (pinfunction "1_1") (pintype "passive"))
    )
    (net (code "119") (name "/29_1440127218") (class "Default")
      (node (ref "JP1019") (pin "P$1") (pinfunction "1_P$1") (pintype "passive"))
      (node (ref "JP291") (pin "1") (pinfunction "1_1") (pintype "passive"))
    )
    (net (code "120") (name "/29_1440127248") (class "Default")
      (node (ref "JP1079") (pin "P$1") (pinfunction "1_P$1") (pintype "passive"))
      (node (ref "JP300") (pin "1") (pinfunction "1_1") (pintype "passive"))
    )
    (net (code "121") (name "/30_1440127218") (class "Default")
      (node (ref "JP1020") (pin "P$1") (pinfunction "1_P$1") (pintype "passive"))
      (node (ref "JP292") (pin "1") (pinfunction "1_1") (pintype "passive"))
    )
    (net (code "122") (name "/30_1440127248") (class "Default")
      (node (ref "JP1080") (pin "P$1") (pinfunction "1_P$1") (pintype "passive"))
      (node (ref "JP299") (pin "1") (pinfunction "1_1") (pintype "passive"))
    )
    (net (code "123") (name "/31_1440127218") (class "Default")
      (node (ref "JP2") (pin "1") (pinfunction "1_1") (pintype "passive"))
      (node (ref "JP962") (pin "P$1") (pinfunction "1_P$1") (pintype "passive"))
    )
    (net (code "124") (name "/31_1440127248") (class "Default")
      (node (ref "JP1022") (pin "P$1") (pinfunction "1_P$1") (pintype "passive"))
      (node (ref "JP9") (pin "1") (pinfunction "1_1") (pintype "passive"))
    )
    (net (code "125") (name "/32_1440127218") (class "Default")
      (node (ref "JP12") (pin "1") (pinfunction "1_1") (pintype "passive"))
      (node (ref "JP964") (pin "P$1") (pinfunction "1_P$1") (pintype "passive"))
    )
    (net (code "126") (name "/32_1440127248") (class "Default")
      (node (ref "JP1024") (pin "P$1") (pinfunction "1_P$1") (pintype "passive"))
      (node (ref "JP19") (pin "1") (pinfunction "1_1") (pintype "passive"))
    )
    (net (code "127") (name "/33_1440127218") (class "Default")
      (node (ref "JP22") (pin "1") (pinfunction "1_1") (pintype "passive"))
      (node (ref "JP966") (pin "P$1") (pinfunction "1_P$1") (pintype "passive"))
    )
    (net (code "128") (name "/33_1440127248") (class "Default")
      (node (ref "JP1026") (pin "P$1") (pinfunction "1_P$1") (pintype "passive"))
      (node (ref "JP29") (pin "1") (pinfunction "1_1") (pintype "passive"))
    )
    (net (code "129") (name "/34_1440127218") (class "Default")
      (node (ref "JP32") (pin "1") (pinfunction "1_1") (pintype "passive"))
      (node (ref "JP968") (pin "P$1") (pinfunction "1_P$1") (pintype "passive"))
    )
    (net (code "130") (name "/34_1440127248") (class "Default")
      (node (ref "JP1028") (pin "P$1") (pinfunction "1_P$1") (pintype "passive"))
      (node (ref "JP39") (pin "1") (pinfunction "1_1") (pintype "passive"))
    )
    (net (code "131") (name "/35_1440127218") (class "Default")
      (node (ref "JP42") (pin "1") (pinfunction "1_1") (pintype "passive"))
      (node (ref "JP970") (pin "P$1") (pinfunction "1_P$1") (pintype "passive"))
    )
    (net (code "132") (name "/35_1440127248") (class "Default")
      (node (ref "JP1030") (pin "P$1") (pinfunction "1_P$1") (pintype "passive"))
      (node (ref "JP49") (pin "1") (pinfunction "1_1") (pintype "passive"))
    )
    (net (code "133") (name "/36_1440127218") (class "Default")
      (node (ref "JP52") (pin "1") (pinfunction "1_1") (pintype "passive"))
      (node (ref "JP972") (pin "P$1") (pinfunction "1_P$1") (pintype "passive"))
    )
    (net (code "134") (name "/36_1440127248") (class "Default")
      (node (ref "JP1032") (pin "P$1") (pinfunction "1_P$1") (pintype "passive"))
      (node (ref "JP59") (pin "1") (pinfunction "1_1") (pintype "passive"))
    )
    (net (code "135") (name "/37_1440127218") (class "Default")
      (node (ref "JP62") (pin "1") (pinfunction "1_1") (pintype "passive"))
      (node (ref "JP974") (pin "P$1") (pinfunction "1_P$1") (pintype "passive"))
    )
    (net (code "136") (name "/37_1440127248") (class "Default")
      (node (ref "JP1034") (pin "P$1") (pinfunction "1_P$1") (pintype "passive"))
      (node (ref "JP69") (pin "1") (pinfunction "1_1") (pintype "passive"))
    )
    (net (code "137") (name "/38_1440127218") (class "Default")
      (node (ref "JP72") (pin "1") (pinfunction "1_1") (pintype "passive"))
      (node (ref "JP976") (pin "P$1") (pinfunction "1_P$1") (pintype "passive"))
    )
    (net (code "138") (name "/38_1440127248") (class "Default")
      (node (ref "JP1036") (pin "P$1") (pinfunction "1_P$1") (pintype "passive"))
      (node (ref "JP79") (pin "1") (pinfunction "1_1") (pintype "passive"))
    )
    (net (code "139") (name "/39_1440127218") (class "Default")
      (node (ref "JP82") (pin "1") (pinfunction "1_1") (pintype "passive"))
      (node (ref "JP978") (pin "P$1") (pinfunction "1_P$1") (pintype "passive"))
    )
    (net (code "140") (name "/39_1440127248") (class "Default")
      (node (ref "JP1038") (pin "P$1") (pinfunction "1_P$1") (pintype "passive"))
      (node (ref "JP89") (pin "1") (pinfunction "1_1") (pintype "passive"))
    )
    (net (code "141") (name "/40_1440127218") (class "Default")
      (node (ref "JP92") (pin "1") (pinfunction "1_1") (pintype "passive"))
      (node (ref "JP980") (pin "P$1") (pinfunction "1_P$1") (pintype "passive"))
    )
    (net (code "142") (name "/40_1440127248") (class "Default")
      (node (ref "JP1040") (pin "P$1") (pinfunction "1_P$1") (pintype "passive"))
      (node (ref "JP99") (pin "1") (pinfunction "1_1") (pintype "passive"))
    )
    (net (code "143") (name "/41_1440127218") (class "Default")
      (node (ref "JP102") (pin "1") (pinfunction "1_1") (pintype "passive"))
      (node (ref "JP982") (pin "P$1") (pinfunction "1_P$1") (pintype "passive"))
    )
    (net (code "144") (name "/41_1440127248") (class "Default")
      (node (ref "JP1042") (pin "P$1") (pinfunction "1_P$1") (pintype "passive"))
      (node (ref "JP109") (pin "1") (pinfunction "1_1") (pintype "passive"))
    )
    (net (code "145") (name "/42_1440127218") (class "Default")
      (node (ref "JP112") (pin "1") (pinfunction "1_1") (pintype "passive"))
      (node (ref "JP984") (pin "P$1") (pinfunction "1_P$1") (pintype "passive"))
    )
    (net (code "146") (name "/42_1440127248") (class "Default")
      (node (ref "JP1044") (pin "P$1") (pinfunction "1_P$1") (pintype "passive"))
      (node (ref "JP119") (pin "1") (pinfunction "1_1") (pintype "passive"))
    )
    (net (code "147") (name "/43_1440127218") (class "Default")
      (node (ref "JP122") (pin "1") (pinfunction "1_1") (pintype "passive"))
      (node (ref "JP986") (pin "P$1") (pinfunction "1_P$1") (pintype "passive"))
    )
    (net (code "148") (name "/43_1440127248") (class "Default")
      (node (ref "JP1046") (pin "P$1") (pinfunction "1_P$1") (pintype "passive"))
      (node (ref "JP129") (pin "1") (pinfunction "1_1") (pintype "passive"))
    )
    (net (code "149") (name "/44_1440127218") (class "Default")
      (node (ref "JP132") (pin "1") (pinfunction "1_1") (pintype "passive"))
      (node (ref "JP988") (pin "P$1") (pinfunction "1_P$1") (pintype "passive"))
    )
    (net (code "150") (name "/44_1440127248") (class "Default")
      (node (ref "JP1048") (pin "P$1") (pinfunction "1_P$1") (pintype "passive"))
      (node (ref "JP139") (pin "1") (pinfunction "1_1") (pintype "passive"))
    )
    (net (code "151") (name "/45_1440127218") (class "Default")
      (node (ref "JP142") (pin "1") (pinfunction "1_1") (pintype "passive"))
      (node (ref "JP990") (pin "P$1") (pinfunction "1_P$1") (pintype "passive"))
    )
    (net (code "152") (name "/45_1440127248") (class "Default")
      (node (ref "JP1050") (pin "P$1") (pinfunction "1_P$1") (pintype "passive"))
      (node (ref "JP149") (pin "1") (pinfunction "1_1") (pintype "passive"))
    )
    (net (code "153") (name "/46_1440127218") (class "Default")
      (node (ref "JP152") (pin "1") (pinfunction "1_1") (pintype "passive"))
      (node (ref "JP992") (pin "P$1") (pinfunction "1_P$1") (pintype "passive"))
    )
    (net (code "154") (name "/46_1440127248") (class "Default")
      (node (ref "JP1052") (pin "P$1") (pinfunction "1_P$1") (pintype "passive"))
      (node (ref "JP159") (pin "1") (pinfunction "1_1") (pintype "passive"))
    )
    (net (code "155") (name "/47_1440127218") (class "Default")
      (node (ref "JP162") (pin "1") (pinfunction "1_1") (pintype "passive"))
      (node (ref "JP994") (pin "P$1") (pinfunction "1_P$1") (pintype "passive"))
    )
    (net (code "156") (name "/47_1440127248") (class "Default")
      (node (ref "JP1054") (pin "P$1") (pinfunction "1_P$1") (pintype "passive"))
      (node (ref "JP169") (pin "1") (pinfunction "1_1") (pintype "passive"))
    )
    (net (code "157") (name "/48_1440127218") (class "Default")
      (node (ref "JP172") (pin "1") (pinfunction "1_1") (pintype "passive"))
      (node (ref "JP996") (pin "P$1") (pinfunction "1_P$1") (pintype "passive"))
    )
    (net (code "158") (name "/48_1440127248") (class "Default")
      (node (ref "JP1056") (pin "P$1") (pinfunction "1_P$1") (pintype "passive"))
      (node (ref "JP179") (pin "1") (pinfunction "1_1") (pintype "passive"))
    )
    (net (code "159") (name "/49_1440127218") (class "Default")
      (node (ref "JP182") (pin "1") (pinfunction "1_1") (pintype "passive"))
      (node (ref "JP998") (pin "P$1") (pinfunction "1_P$1") (pintype "passive"))
    )
    (net (code "160") (name "/49_1440127248") (class "Default")
      (node (ref "JP1058") (pin "P$1") (pinfunction "1_P$1") (pintype "passive"))
      (node (ref "JP189") (pin "1") (pinfunction "1_1") (pintype "passive"))
    )
    (net (code "161") (name "/50_1440127218") (class "Default")
      (node (ref "JP1000") (pin "P$1") (pinfunction "1_P$1") (pintype "passive"))
      (node (ref "JP192") (pin "1") (pinfunction "1_1") (pintype "passive"))
    )
    (net (code "162") (name "/50_1440127248") (class "Default")
      (node (ref "JP1060") (pin "P$1") (pinfunction "1_P$1") (pintype "passive"))
      (node (ref "JP199") (pin "1") (pinfunction "1_1") (pintype "passive"))
    )
    (net (code "163") (name "/51_1440127218") (class "Default")
      (node (ref "JP1002") (pin "P$1") (pinfunction "1_P$1") (pintype "passive"))
      (node (ref "JP202") (pin "1") (pinfunction "1_1") (pintype "passive"))
    )
    (net (code "164") (name "/51_1440127248") (class "Default")
      (node (ref "JP1062") (pin "P$1") (pinfunction "1_P$1") (pintype "passive"))
      (node (ref "JP209") (pin "1") (pinfunction "1_1") (pintype "passive"))
    )
    (net (code "165") (name "/52_1440127218") (class "Default")
      (node (ref "JP1004") (pin "P$1") (pinfunction "1_P$1") (pintype "passive"))
      (node (ref "JP212") (pin "1") (pinfunction "1_1") (pintype "passive"))
    )
    (net (code "166") (name "/52_1440127248") (class "Default")
      (node (ref "JP1064") (pin "P$1") (pinfunction "1_P$1") (pintype "passive"))
      (node (ref "JP219") (pin "1") (pinfunction "1_1") (pintype "passive"))
    )
    (net (code "167") (name "/53_1440127218") (class "Default")
      (node (ref "JP1006") (pin "P$1") (pinfunction "1_P$1") (pintype "passive"))
      (node (ref "JP222") (pin "1") (pinfunction "1_1") (pintype "passive"))
    )
    (net (code "168") (name "/53_1440127248") (class "Default")
      (node (ref "JP1066") (pin "P$1") (pinfunction "1_P$1") (pintype "passive"))
      (node (ref "JP229") (pin "1") (pinfunction "1_1") (pintype "passive"))
    )
    (net (code "169") (name "/54_1440127218") (class "Default")
      (node (ref "JP1008") (pin "P$1") (pinfunction "1_P$1") (pintype "passive"))
      (node (ref "JP232") (pin "1") (pinfunction "1_1") (pintype "passive"))
    )
    (net (code "170") (name "/54_1440127248") (class "Default")
      (node (ref "JP1068") (pin "P$1") (pinfunction "1_P$1") (pintype "passive"))
      (node (ref "JP239") (pin "1") (pinfunction "1_1") (pintype "passive"))
    )
    (net (code "171") (name "/55_1440127218") (class "Default")
      (node (ref "JP1010") (pin "P$1") (pinfunction "1_P$1") (pintype "passive"))
      (node (ref "JP242") (pin "1") (pinfunction "1_1") (pintype "passive"))
    )
    (net (code "172") (name "/55_1440127248") (class "Default")
      (node (ref "JP1070") (pin "P$1") (pinfunction "1_P$1") (pintype "passive"))
      (node (ref "JP249") (pin "1") (pinfunction "1_1") (pintype "passive"))
    )
    (net (code "173") (name "/56_1440127218") (class "Default")
      (node (ref "JP1012") (pin "P$1") (pinfunction "1_P$1") (pintype "passive"))
      (node (ref "JP252") (pin "1") (pinfunction "1_1") (pintype "passive"))
    )
    (net (code "174") (name "/56_1440127248") (class "Default")
      (node (ref "JP1072") (pin "P$1") (pinfunction "1_P$1") (pintype "passive"))
      (node (ref "JP259") (pin "1") (pinfunction "1_1") (pintype "passive"))
    )
    (net (code "175") (name "/57_1440127218") (class "Default")
      (node (ref "JP1014") (pin "P$1") (pinfunction "1_P$1") (pintype "passive"))
      (node (ref "JP262") (pin "1") (pinfunction "1_1") (pintype "passive"))
    )
    (net (code "176") (name "/57_1440127248") (class "Default")
      (node (ref "JP1074") (pin "P$1") (pinfunction "1_P$1") (pintype "passive"))
      (node (ref "JP269") (pin "1") (pinfunction "1_1") (pintype "passive"))
    )
    (net (code "177") (name "/58_1440127218") (class "Default")
      (node (ref "JP1016") (pin "P$1") (pinfunction "1_P$1") (pintype "passive"))
      (node (ref "JP272") (pin "1") (pinfunction "1_1") (pintype "passive"))
    )
    (net (code "178") (name "/58_1440127248") (class "Default")
      (node (ref "JP1076") (pin "P$1") (pinfunction "1_P$1") (pintype "passive"))
      (node (ref "JP279") (pin "1") (pinfunction "1_1") (pintype "passive"))
    )
    (net (code "179") (name "/59_1440127218") (class "Default")
      (node (ref "JP1018") (pin "P$1") (pinfunction "1_P$1") (pintype "passive"))
      (node (ref "JP282") (pin "1") (pinfunction "1_1") (pintype "passive"))
    )
    (net (code "180") (name "/59_1440127248") (class "Default")
      (node (ref "JP1078") (pin "P$1") (pinfunction "1_P$1") (pintype "passive"))
      (node (ref "JP289") (pin "1") (pinfunction "1_1") (pintype "passive"))
    )
    (net (code "181") (name "/60_1440127218") (class "Default")
      (node (ref "JP3") (pin "1") (pinfunction "1_1") (pintype "passive"))
      (node (ref "JP901") (pin "P$1") (pinfunction "1_P$1") (pintype "passive"))
    )
    (net (code "182") (name "/60_1440127248") (class "Default")
      (node (ref "JP1081") (pin "P$1") (pinfunction "1_P$1") (pintype "passive"))
      (node (ref "JP8") (pin "1") (pinfunction "1_1") (pintype "passive"))
    )
    (net (code "183") (name "/61_1440127218") (class "Default")
      (node (ref "JP13") (pin "1") (pinfunction "1_1") (pintype "passive"))
      (node (ref "JP903") (pin "P$1") (pinfunction "1_P$1") (pintype "passive"))
    )
    (net (code "184") (name "/61_1440127248") (class "Default")
      (node (ref "JP1083") (pin "P$1") (pinfunction "1_P$1") (pintype "passive"))
      (node (ref "JP18") (pin "1") (pinfunction "1_1") (pintype "passive"))
    )
    (net (code "185") (name "/62_1440127218") (class "Default")
      (node (ref "JP23") (pin "1") (pinfunction "1_1") (pintype "passive"))
      (node (ref "JP905") (pin "P$1") (pinfunction "1_P$1") (pintype "passive"))
    )
    (net (code "186") (name "/62_1440127248") (class "Default")
      (node (ref "JP1085") (pin "P$1") (pinfunction "1_P$1") (pintype "passive"))
      (node (ref "JP28") (pin "1") (pinfunction "1_1") (pintype "passive"))
    )
    (net (code "187") (name "/63_1440127218") (class "Default")
      (node (ref "JP33") (pin "1") (pinfunction "1_1") (pintype "passive"))
      (node (ref "JP907") (pin "P$1") (pinfunction "1_P$1") (pintype "passive"))
    )
    (net (code "188") (name "/63_1440127248") (class "Default")
      (node (ref "JP1087") (pin "P$1") (pinfunction "1_P$1") (pintype "passive"))
      (node (ref "JP38") (pin "1") (pinfunction "1_1") (pintype "passive"))
    )
    (net (code "189") (name "/64_1440127218") (class "Default")
      (node (ref "JP43") (pin "1") (pinfunction "1_1") (pintype "passive"))
      (node (ref "JP909") (pin "P$1") (pinfunction "1_P$1") (pintype "passive"))
    )
    (net (code "190") (name "/64_1440127248") (class "Default")
      (node (ref "JP1089") (pin "P$1") (pinfunction "1_P$1") (pintype "passive"))
      (node (ref "JP48") (pin "1") (pinfunction "1_1") (pintype "passive"))
    )
    (net (code "191") (name "/65_1440127218") (class "Default")
      (node (ref "JP53") (pin "1") (pinfunction "1_1") (pintype "passive"))
      (node (ref "JP911") (pin "P$1") (pinfunction "1_P$1") (pintype "passive"))
    )
    (net (code "192") (name "/65_1440127248") (class "Default")
      (node (ref "JP1091") (pin "P$1") (pinfunction "1_P$1") (pintype "passive"))
      (node (ref "JP58") (pin "1") (pinfunction "1_1") (pintype "passive"))
    )
    (net (code "193") (name "/66_1440127218") (class "Default")
      (node (ref "JP63") (pin "1") (pinfunction "1_1") (pintype "passive"))
      (node (ref "JP913") (pin "P$1") (pinfunction "1_P$1") (pintype "passive"))
    )
    (net (code "194") (name "/66_1440127248") (class "Default")
      (node (ref "JP1093") (pin "P$1") (pinfunction "1_P$1") (pintype "passive"))
      (node (ref "JP68") (pin "1") (pinfunction "1_1") (pintype "passive"))
    )
    (net (code "195") (name "/67_1440127218") (class "Default")
      (node (ref "JP73") (pin "1") (pinfunction "1_1") (pintype "passive"))
      (node (ref "JP915") (pin "P$1") (pinfunction "1_P$1") (pintype "passive"))
    )
    (net (code "196") (name "/67_1440127248") (class "Default")
      (node (ref "JP1095") (pin "P$1") (pinfunction "1_P$1") (pintype "passive"))
      (node (ref "JP78") (pin "1") (pinfunction "1_1") (pintype "passive"))
    )
    (net (code "197") (name "/68_1440127218") (class "Default")
      (node (ref "JP83") (pin "1") (pinfunction "1_1") (pintype "passive"))
      (node (ref "JP917") (pin "P$1") (pinfunction "1_P$1") (pintype "passive"))
    )
    (net (code "198") (name "/68_1440127248") (class "Default")
      (node (ref "JP1097") (pin "P$1") (pinfunction "1_P$1") (pintype "passive"))
      (node (ref "JP88") (pin "1") (pinfunction "1_1") (pintype "passive"))
    )
    (net (code "199") (name "/69_1440127218") (class "Default")
      (node (ref "JP919") (pin "P$1") (pinfunction "1_P$1") (pintype "passive"))
      (node (ref "JP93") (pin "1") (pinfunction "1_1") (pintype "passive"))
    )
    (net (code "200") (name "/69_1440127248") (class "Default")
      (node (ref "JP1099") (pin "P$1") (pinfunction "1_P$1") (pintype "passive"))
      (node (ref "JP98") (pin "1") (pinfunction "1_1") (pintype "passive"))
    )
    (net (code "201") (name "/70_1440127218") (class "Default")
      (node (ref "JP103") (pin "1") (pinfunction "1_1") (pintype "passive"))
      (node (ref "JP921") (pin "P$1") (pinfunction "1_P$1") (pintype "passive"))
    )
    (net (code "202") (name "/70_1440127248") (class "Default")
      (node (ref "JP108") (pin "1") (pinfunction "1_1") (pintype "passive"))
      (node (ref "JP1101") (pin "P$1") (pinfunction "1_P$1") (pintype "passive"))
    )
    (net (code "203") (name "/71_1440127218") (class "Default")
      (node (ref "JP113") (pin "1") (pinfunction "1_1") (pintype "passive"))
      (node (ref "JP923") (pin "P$1") (pinfunction "1_P$1") (pintype "passive"))
    )
    (net (code "204") (name "/71_1440127248") (class "Default")
      (node (ref "JP1103") (pin "P$1") (pinfunction "1_P$1") (pintype "passive"))
      (node (ref "JP118") (pin "1") (pinfunction "1_1") (pintype "passive"))
    )
    (net (code "205") (name "/72_1440127218") (class "Default")
      (node (ref "JP123") (pin "1") (pinfunction "1_1") (pintype "passive"))
      (node (ref "JP925") (pin "P$1") (pinfunction "1_P$1") (pintype "passive"))
    )
    (net (code "206") (name "/72_1440127248") (class "Default")
      (node (ref "JP1105") (pin "P$1") (pinfunction "1_P$1") (pintype "passive"))
      (node (ref "JP128") (pin "1") (pinfunction "1_1") (pintype "passive"))
    )
    (net (code "207") (name "/73_1440127218") (class "Default")
      (node (ref "JP133") (pin "1") (pinfunction "1_1") (pintype "passive"))
      (node (ref "JP927") (pin "P$1") (pinfunction "1_P$1") (pintype "passive"))
    )
    (net (code "208") (name "/73_1440127248") (class "Default")
      (node (ref "JP1107") (pin "P$1") (pinfunction "1_P$1") (pintype "passive"))
      (node (ref "JP138") (pin "1") (pinfunction "1_1") (pintype "passive"))
    )
    (net (code "209") (name "/74_1440127218") (class "Default")
      (node (ref "JP143") (pin "1") (pinfunction "1_1") (pintype "passive"))
      (node (ref "JP929") (pin "P$1") (pinfunction "1_P$1") (pintype "passive"))
    )
    (net (code "210") (name "/74_1440127248") (class "Default")
      (node (ref "JP1109") (pin "P$1") (pinfunction "1_P$1") (pintype "passive"))
      (node (ref "JP148") (pin "1") (pinfunction "1_1") (pintype "passive"))
    )
    (net (code "211") (name "/75_1440127218") (class "Default")
      (node (ref "JP153") (pin "1") (pinfunction "1_1") (pintype "passive"))
      (node (ref "JP931") (pin "P$1") (pinfunction "1_P$1") (pintype "passive"))
    )
    (net (code "212") (name "/75_1440127248") (class "Default")
      (node (ref "JP1111") (pin "P$1") (pinfunction "1_P$1") (pintype "passive"))
      (node (ref "JP158") (pin "1") (pinfunction "1_1") (pintype "passive"))
    )
    (net (code "213") (name "/76_1440127218") (class "Default")
      (node (ref "JP163") (pin "1") (pinfunction "1_1") (pintype "passive"))
      (node (ref "JP933") (pin "P$1") (pinfunction "1_P$1") (pintype "passive"))
    )
    (net (code "214") (name "/76_1440127248") (class "Default")
      (node (ref "JP1113") (pin "P$1") (pinfunction "1_P$1") (pintype "passive"))
      (node (ref "JP168") (pin "1") (pinfunction "1_1") (pintype "passive"))
    )
    (net (code "215") (name "/77_1440127218") (class "Default")
      (node (ref "JP173") (pin "1") (pinfunction "1_1") (pintype "passive"))
      (node (ref "JP935") (pin "P$1") (pinfunction "1_P$1") (pintype "passive"))
    )
    (net (code "216") (name "/77_1440127248") (class "Default")
      (node (ref "JP1115") (pin "P$1") (pinfunction "1_P$1") (pintype "passive"))
      (node (ref "JP178") (pin "1") (pinfunction "1_1") (pintype "passive"))
    )
    (net (code "217") (name "/78_1440127218") (class "Default")
      (node (ref "JP183") (pin "1") (pinfunction "1_1") (pintype "passive"))
      (node (ref "JP937") (pin "P$1") (pinfunction "1_P$1") (pintype "passive"))
    )
    (net (code "218") (name "/78_1440127248") (class "Default")
      (node (ref "JP1117") (pin "P$1") (pinfunction "1_P$1") (pintype "passive"))
      (node (ref "JP188") (pin "1") (pinfunction "1_1") (pintype "passive"))
    )
    (net (code "219") (name "/79_1440127218") (class "Default")
      (node (ref "JP193") (pin "1") (pinfunction "1_1") (pintype "passive"))
      (node (ref "JP939") (pin "P$1") (pinfunction "1_P$1") (pintype "passive"))
    )
    (net (code "220") (name "/79_1440127248") (class "Default")
      (node (ref "JP1119") (pin "P$1") (pinfunction "1_P$1") (pintype "passive"))
      (node (ref "JP198") (pin "1") (pinfunction "1_1") (pintype "passive"))
    )
    (net (code "221") (name "/80_1440127218") (class "Default")
      (node (ref "JP203") (pin "1") (pinfunction "1_1") (pintype "passive"))
      (node (ref "JP941") (pin "P$1") (pinfunction "1_P$1") (pintype "passive"))
    )
    (net (code "222") (name "/80_1440127248") (class "Default")
      (node (ref "JP1121") (pin "P$1") (pinfunction "1_P$1") (pintype "passive"))
      (node (ref "JP208") (pin "1") (pinfunction "1_1") (pintype "passive"))
    )
    (net (code "223") (name "/81_1440127218") (class "Default")
      (node (ref "JP213") (pin "1") (pinfunction "1_1") (pintype "passive"))
      (node (ref "JP943") (pin "P$1") (pinfunction "1_P$1") (pintype "passive"))
    )
    (net (code "224") (name "/81_1440127248") (class "Default")
      (node (ref "JP1123") (pin "P$1") (pinfunction "1_P$1") (pintype "passive"))
      (node (ref "JP218") (pin "1") (pinfunction "1_1") (pintype "passive"))
    )
    (net (code "225") (name "/82_1440127218") (class "Default")
      (node (ref "JP223") (pin "1") (pinfunction "1_1") (pintype "passive"))
      (node (ref "JP945") (pin "P$1") (pinfunction "1_P$1") (pintype "passive"))
    )
    (net (code "226") (name "/82_1440127248") (class "Default")
      (node (ref "JP1125") (pin "P$1") (pinfunction "1_P$1") (pintype "passive"))
      (node (ref "JP228") (pin "1") (pinfunction "1_1") (pintype "passive"))
    )
    (net (code "227") (name "/83_1440127218") (class "Default")
      (node (ref "JP233") (pin "1") (pinfunction "1_1") (pintype "passive"))
      (node (ref "JP947") (pin "P$1") (pinfunction "1_P$1") (pintype "passive"))
    )
    (net (code "228") (name "/83_1440127248") (class "Default")
      (node (ref "JP1127") (pin "P$1") (pinfunction "1_P$1") (pintype "passive"))
      (node (ref "JP238") (pin "1") (pinfunction "1_1") (pintype "passive"))
    )
    (net (code "229") (name "/84_1440127218") (class "Default")
      (node (ref "JP243") (pin "1") (pinfunction "1_1") (pintype "passive"))
      (node (ref "JP949") (pin "P$1") (pinfunction "1_P$1") (pintype "passive"))
    )
    (net (code "230") (name "/84_1440127248") (class "Default")
      (node (ref "JP1129") (pin "P$1") (pinfunction "1_P$1") (pintype "passive"))
      (node (ref "JP248") (pin "1") (pinfunction "1_1") (pintype "passive"))
    )
    (net (code "231") (name "/85_1440127218") (class "Default")
      (node (ref "JP253") (pin "1") (pinfunction "1_1") (pintype "passive"))
      (node (ref "JP951") (pin "P$1") (pinfunction "1_P$1") (pintype "passive"))
    )
    (net (code "232") (name "/85_1440127248") (class "Default")
      (node (ref "JP1131") (pin "P$1") (pinfunction "1_P$1") (pintype "passive"))
      (node (ref "JP258") (pin "1") (pinfunction "1_1") (pintype "passive"))
    )
    (net (code "233") (name "/86_1440127218") (class "Default")
      (node (ref "JP263") (pin "1") (pinfunction "1_1") (pintype "passive"))
      (node (ref "JP953") (pin "P$1") (pinfunction "1_P$1") (pintype "passive"))
    )
    (net (code "234") (name "/86_1440127248") (class "Default")
      (node (ref "JP1133") (pin "P$1") (pinfunction "1_P$1") (pintype "passive"))
      (node (ref "JP268") (pin "1") (pinfunction "1_1") (pintype "passive"))
    )
    (net (code "235") (name "/87_1440127218") (class "Default")
      (node (ref "JP273") (pin "1") (pinfunction "1_1") (pintype "passive"))
      (node (ref "JP955") (pin "P$1") (pinfunction "1_P$1") (pintype "passive"))
    )
    (net (code "236") (name "/87_1440127248") (class "Default")
      (node (ref "JP1135") (pin "P$1") (pinfunction "1_P$1") (pintype "passive"))
      (node (ref "JP278") (pin "1") (pinfunction "1_1") (pintype "passive"))
    )
    (net (code "237") (name "/88_1440127218") (class "Default")
      (node (ref "JP283") (pin "1") (pinfunction "1_1") (pintype "passive"))
      (node (ref "JP957") (pin "P$1") (pinfunction "1_P$1") (pintype "passive"))
    )
    (net (code "238") (name "/88_1440127248") (class "Default")
      (node (ref "JP1137") (pin "P$1") (pinfunction "1_P$1") (pintype "passive"))
      (node (ref "JP288") (pin "1") (pinfunction "1_1") (pintype "passive"))
    )
    (net (code "239") (name "/89_1440127218") (class "Default")
      (node (ref "JP293") (pin "1") (pinfunction "1_1") (pintype "passive"))
      (node (ref "JP959") (pin "P$1") (pinfunction "1_P$1") (pintype "passive"))
    )
    (net (code "240") (name "/89_1440127248") (class "Default")
      (node (ref "JP1139") (pin "P$1") (pinfunction "1_P$1") (pintype "passive"))
      (node (ref "JP298") (pin "1") (pinfunction "1_1") (pintype "passive"))
    )
    (net (code "241") (name "/90_1440127218") (class "Default")
      (node (ref "JP294") (pin "1") (pinfunction "1_1") (pintype "passive"))
      (node (ref "JP960") (pin "P$1") (pinfunction "1_P$1") (pintype "passive"))
    )
    (net (code "242") (name "/90_1440127248") (class "Default")
      (node (ref "JP1140") (pin "P$1") (pinfunction "1_P$1") (pintype "passive"))
      (node (ref "JP297") (pin "1") (pinfunction "1_1") (pintype "passive"))
    )
    (net (code "243") (name "/91_1440127218") (class "Default")
      (node (ref "JP4") (pin "1") (pinfunction "1_1") (pintype "passive"))
      (node (ref "JP902") (pin "P$1") (pinfunction "1_P$1") (pintype "passive"))
    )
    (net (code "244") (name "/91_1440127248") (class "Default")
      (node (ref "JP1082") (pin "P$1") (pinfunction "1_P$1") (pintype "passive"))
      (node (ref "JP7") (pin "1") (pinfunction "1_1") (pintype "passive"))
    )
    (net (code "245") (name "/92_1440127218") (class "Default")
      (node (ref "JP14") (pin "1") (pinfunction "1_1") (pintype "passive"))
      (node (ref "JP904") (pin "P$1") (pinfunction "1_P$1") (pintype "passive"))
    )
    (net (code "246") (name "/92_1440127248") (class "Default")
      (node (ref "JP1084") (pin "P$1") (pinfunction "1_P$1") (pintype "passive"))
      (node (ref "JP17") (pin "1") (pinfunction "1_1") (pintype "passive"))
    )
    (net (code "247") (name "/93_1440127218") (class "Default")
      (node (ref "JP24") (pin "1") (pinfunction "1_1") (pintype "passive"))
      (node (ref "JP906") (pin "P$1") (pinfunction "1_P$1") (pintype "passive"))
    )
    (net (code "248") (name "/93_1440127248") (class "Default")
      (node (ref "JP1086") (pin "P$1") (pinfunction "1_P$1") (pintype "passive"))
      (node (ref "JP27") (pin "1") (pinfunction "1_1") (pintype "passive"))
    )
    (net (code "249") (name "/94_1440127218") (class "Default")
      (node (ref "JP34") (pin "1") (pinfunction "1_1") (pintype "passive"))
      (node (ref "JP908") (pin "P$1") (pinfunction "1_P$1") (pintype "passive"))
    )
    (net (code "250") (name "/94_1440127248") (class "Default")
      (node (ref "JP1088") (pin "P$1") (pinfunction "1_P$1") (pintype "passive"))
      (node (ref "JP37") (pin "1") (pinfunction "1_1") (pintype "passive"))
    )
    (net (code "251") (name "/95_1440127218") (class "Default")
      (node (ref "JP44") (pin "1") (pinfunction "1_1") (pintype "passive"))
      (node (ref "JP910") (pin "P$1") (pinfunction "1_P$1") (pintype "passive"))
    )
    (net (code "252") (name "/95_1440127248") (class "Default")
      (node (ref "JP1090") (pin "P$1") (pinfunction "1_P$1") (pintype "passive"))
      (node (ref "JP47") (pin "1") (pinfunction "1_1") (pintype "passive"))
    )
    (net (code "253") (name "/96_1440127218") (class "Default")
      (node (ref "JP54") (pin "1") (pinfunction "1_1") (pintype "passive"))
      (node (ref "JP912") (pin "P$1") (pinfunction "1_P$1") (pintype "passive"))
    )
    (net (code "254") (name "/96_1440127248") (class "Default")
      (node (ref "JP1092") (pin "P$1") (pinfunction "1_P$1") (pintype "passive"))
      (node (ref "JP57") (pin "1") (pinfunction "1_1") (pintype "passive"))
    )
    (net (code "255") (name "/97_1440127218") (class "Default")
      (node (ref "JP64") (pin "1") (pinfunction "1_1") (pintype "passive"))
      (node (ref "JP914") (pin "P$1") (pinfunction "1_P$1") (pintype "passive"))
    )
    (net (code "256") (name "/97_1440127248") (class "Default")
      (node (ref "JP1094") (pin "P$1") (pinfunction "1_P$1") (pintype "passive"))
      (node (ref "JP67") (pin "1") (pinfunction "1_1") (pintype "passive"))
    )
    (net (code "257") (name "/98_1440127218") (class "Default")
      (node (ref "JP74") (pin "1") (pinfunction "1_1") (pintype "passive"))
      (node (ref "JP916") (pin "P$1") (pinfunction "1_P$1") (pintype "passive"))
    )
    (net (code "258") (name "/98_1440127248") (class "Default")
      (node (ref "JP1096") (pin "P$1") (pinfunction "1_P$1") (pintype "passive"))
      (node (ref "JP77") (pin "1") (pinfunction "1_1") (pintype "passive"))
    )
    (net (code "259") (name "/99_1440127218") (class "Default")
      (node (ref "JP84") (pin "1") (pinfunction "1_1") (pintype "passive"))
      (node (ref "JP918") (pin "P$1") (pinfunction "1_P$1") (pintype "passive"))
    )
    (net (code "260") (name "/99_1440127248") (class "Default")
      (node (ref "JP1098") (pin "P$1") (pinfunction "1_P$1") (pintype "passive"))
      (node (ref "JP87") (pin "1") (pinfunction "1_1") (pintype "passive"))
    )
    (net (code "261") (name "/100_1440127218") (class "Default")
      (node (ref "JP920") (pin "P$1") (pinfunction "1_P$1") (pintype "passive"))
      (node (ref "JP94") (pin "1") (pinfunction "1_1") (pintype "passive"))
    )
    (net (code "262") (name "/100_1440127248") (class "Default")
      (node (ref "JP1100") (pin "P$1") (pinfunction "1_P$1") (pintype "passive"))
      (node (ref "JP97") (pin "1") (pinfunction "1_1") (pintype "passive"))
    )
    (net (code "263") (name "/101_1440127218") (class "Default")
      (node (ref "JP104") (pin "1") (pinfunction "1_1") (pintype "passive"))
      (node (ref "JP922") (pin "P$1") (pinfunction "1_P$1") (pintype "passive"))
    )
    (net (code "264") (name "/101_1440127248") (class "Default")
      (node (ref "JP107") (pin "1") (pinfunction "1_1") (pintype "passive"))
      (node (ref "JP1102") (pin "P$1") (pinfunction "1_P$1") (pintype "passive"))
    )
    (net (code "265") (name "/102_1440127218") (class "Default")
      (node (ref "JP114") (pin "1") (pinfunction "1_1") (pintype "passive"))
      (node (ref "JP924") (pin "P$1") (pinfunction "1_P$1") (pintype "passive"))
    )
    (net (code "266") (name "/102_1440127248") (class "Default")
      (node (ref "JP1104") (pin "P$1") (pinfunction "1_P$1") (pintype "passive"))
      (node (ref "JP117") (pin "1") (pinfunction "1_1") (pintype "passive"))
    )
    (net (code "267") (name "/103_1440127218") (class "Default")
      (node (ref "JP124") (pin "1") (pinfunction "1_1") (pintype "passive"))
      (node (ref "JP926") (pin "P$1") (pinfunction "1_P$1") (pintype "passive"))
    )
    (net (code "268") (name "/103_1440127248") (class "Default")
      (node (ref "JP1106") (pin "P$1") (pinfunction "1_P$1") (pintype "passive"))
      (node (ref "JP127") (pin "1") (pinfunction "1_1") (pintype "passive"))
    )
    (net (code "269") (name "/104_1440127218") (class "Default")
      (node (ref "JP134") (pin "1") (pinfunction "1_1") (pintype "passive"))
      (node (ref "JP928") (pin "P$1") (pinfunction "1_P$1") (pintype "passive"))
    )
    (net (code "270") (name "/104_1440127248") (class "Default")
      (node (ref "JP1108") (pin "P$1") (pinfunction "1_P$1") (pintype "passive"))
      (node (ref "JP137") (pin "1") (pinfunction "1_1") (pintype "passive"))
    )
    (net (code "271") (name "/105_1440127218") (class "Default")
      (node (ref "JP144") (pin "1") (pinfunction "1_1") (pintype "passive"))
      (node (ref "JP930") (pin "P$1") (pinfunction "1_P$1") (pintype "passive"))
    )
    (net (code "272") (name "/105_1440127248") (class "Default")
      (node (ref "JP1110") (pin "P$1") (pinfunction "1_P$1") (pintype "passive"))
      (node (ref "JP147") (pin "1") (pinfunction "1_1") (pintype "passive"))
    )
    (net (code "273") (name "/106_1440127218") (class "Default")
      (node (ref "JP154") (pin "1") (pinfunction "1_1") (pintype "passive"))
      (node (ref "JP932") (pin "P$1") (pinfunction "1_P$1") (pintype "passive"))
    )
    (net (code "274") (name "/106_1440127248") (class "Default")
      (node (ref "JP1112") (pin "P$1") (pinfunction "1_P$1") (pintype "passive"))
      (node (ref "JP157") (pin "1") (pinfunction "1_1") (pintype "passive"))
    )
    (net (code "275") (name "/107_1440127218") (class "Default")
      (node (ref "JP164") (pin "1") (pinfunction "1_1") (pintype "passive"))
      (node (ref "JP934") (pin "P$1") (pinfunction "1_P$1") (pintype "passive"))
    )
    (net (code "276") (name "/107_1440127248") (class "Default")
      (node (ref "JP1114") (pin "P$1") (pinfunction "1_P$1") (pintype "passive"))
      (node (ref "JP167") (pin "1") (pinfunction "1_1") (pintype "passive"))
    )
    (net (code "277") (name "/108_1440127218") (class "Default")
      (node (ref "JP174") (pin "1") (pinfunction "1_1") (pintype "passive"))
      (node (ref "JP936") (pin "P$1") (pinfunction "1_P$1") (pintype "passive"))
    )
    (net (code "278") (name "/108_1440127248") (class "Default")
      (node (ref "JP1116") (pin "P$1") (pinfunction "1_P$1") (pintype "passive"))
      (node (ref "JP177") (pin "1") (pinfunction "1_1") (pintype "passive"))
    )
    (net (code "279") (name "/109_1440127218") (class "Default")
      (node (ref "JP184") (pin "1") (pinfunction "1_1") (pintype "passive"))
      (node (ref "JP938") (pin "P$1") (pinfunction "1_P$1") (pintype "passive"))
    )
    (net (code "280") (name "/109_1440127248") (class "Default")
      (node (ref "JP1118") (pin "P$1") (pinfunction "1_P$1") (pintype "passive"))
      (node (ref "JP187") (pin "1") (pinfunction "1_1") (pintype "passive"))
    )
    (net (code "281") (name "/110_1440127218") (class "Default")
      (node (ref "JP194") (pin "1") (pinfunction "1_1") (pintype "passive"))
      (node (ref "JP940") (pin "P$1") (pinfunction "1_P$1") (pintype "passive"))
    )
    (net (code "282") (name "/110_1440127248") (class "Default")
      (node (ref "JP1120") (pin "P$1") (pinfunction "1_P$1") (pintype "passive"))
      (node (ref "JP197") (pin "1") (pinfunction "1_1") (pintype "passive"))
    )
    (net (code "283") (name "/111_1440127218") (class "Default")
      (node (ref "JP204") (pin "1") (pinfunction "1_1") (pintype "passive"))
      (node (ref "JP942") (pin "P$1") (pinfunction "1_P$1") (pintype "passive"))
    )
    (net (code "284") (name "/111_1440127248") (class "Default")
      (node (ref "JP1122") (pin "P$1") (pinfunction "1_P$1") (pintype "passive"))
      (node (ref "JP207") (pin "1") (pinfunction "1_1") (pintype "passive"))
    )
    (net (code "285") (name "/112_1440127218") (class "Default")
      (node (ref "JP214") (pin "1") (pinfunction "1_1") (pintype "passive"))
      (node (ref "JP944") (pin "P$1") (pinfunction "1_P$1") (pintype "passive"))
    )
    (net (code "286") (name "/112_1440127248") (class "Default")
      (node (ref "JP1124") (pin "P$1") (pinfunction "1_P$1") (pintype "passive"))
      (node (ref "JP217") (pin "1") (pinfunction "1_1") (pintype "passive"))
    )
    (net (code "287") (name "/113_1440127218") (class "Default")
      (node (ref "JP224") (pin "1") (pinfunction "1_1") (pintype "passive"))
      (node (ref "JP946") (pin "P$1") (pinfunction "1_P$1") (pintype "passive"))
    )
    (net (code "288") (name "/113_1440127248") (class "Default")
      (node (ref "JP1126") (pin "P$1") (pinfunction "1_P$1") (pintype "passive"))
      (node (ref "JP227") (pin "1") (pinfunction "1_1") (pintype "passive"))
    )
    (net (code "289") (name "/114_1440127218") (class "Default")
      (node (ref "JP234") (pin "1") (pinfunction "1_1") (pintype "passive"))
      (node (ref "JP948") (pin "P$1") (pinfunction "1_P$1") (pintype "passive"))
    )
    (net (code "290") (name "/114_1440127248") (class "Default")
      (node (ref "JP1128") (pin "P$1") (pinfunction "1_P$1") (pintype "passive"))
      (node (ref "JP237") (pin "1") (pinfunction "1_1") (pintype "passive"))
    )
    (net (code "291") (name "/115_1440127218") (class "Default")
      (node (ref "JP244") (pin "1") (pinfunction "1_1") (pintype "passive"))
      (node (ref "JP950") (pin "P$1") (pinfunction "1_P$1") (pintype "passive"))
    )
    (net (code "292") (name "/115_1440127248") (class "Default")
      (node (ref "JP1130") (pin "P$1") (pinfunction "1_P$1") (pintype "passive"))
      (node (ref "JP247") (pin "1") (pinfunction "1_1") (pintype "passive"))
    )
    (net (code "293") (name "/116_1440127218") (class "Default")
      (node (ref "JP254") (pin "1") (pinfunction "1_1") (pintype "passive"))
      (node (ref "JP952") (pin "P$1") (pinfunction "1_P$1") (pintype "passive"))
    )
    (net (code "294") (name "/116_1440127248") (class "Default")
      (node (ref "JP1132") (pin "P$1") (pinfunction "1_P$1") (pintype "passive"))
      (node (ref "JP257") (pin "1") (pinfunction "1_1") (pintype "passive"))
    )
    (net (code "295") (name "/117_1440127218") (class "Default")
      (node (ref "JP264") (pin "1") (pinfunction "1_1") (pintype "passive"))
      (node (ref "JP954") (pin "P$1") (pinfunction "1_P$1") (pintype "passive"))
    )
    (net (code "296") (name "/117_1440127248") (class "Default")
      (node (ref "JP1134") (pin "P$1") (pinfunction "1_P$1") (pintype "passive"))
      (node (ref "JP267") (pin "1") (pinfunction "1_1") (pintype "passive"))
    )
    (net (code "297") (name "/118_1440127218") (class "Default")
      (node (ref "JP274") (pin "1") (pinfunction "1_1") (pintype "passive"))
      (node (ref "JP956") (pin "P$1") (pinfunction "1_P$1") (pintype "passive"))
    )
    (net (code "298") (name "/118_1440127248") (class "Default")
      (node (ref "JP1136") (pin "P$1") (pinfunction "1_P$1") (pintype "passive"))
      (node (ref "JP277") (pin "1") (pinfunction "1_1") (pintype "passive"))
    )
    (net (code "299") (name "/119_1440127218") (class "Default")
      (node (ref "JP284") (pin "1") (pinfunction "1_1") (pintype "passive"))
      (node (ref "JP958") (pin "P$1") (pinfunction "1_P$1") (pintype "passive"))
    )
    (net (code "300") (name "/119_1440127248") (class "Default")
      (node (ref "JP1138") (pin "P$1") (pinfunction "1_P$1") (pintype "passive"))
      (node (ref "JP287") (pin "1") (pinfunction "1_1") (pintype "passive"))
    )
  )
)
